# Mustang_Duino.net
KiCad netlist of a schematic drawn in EAGLE
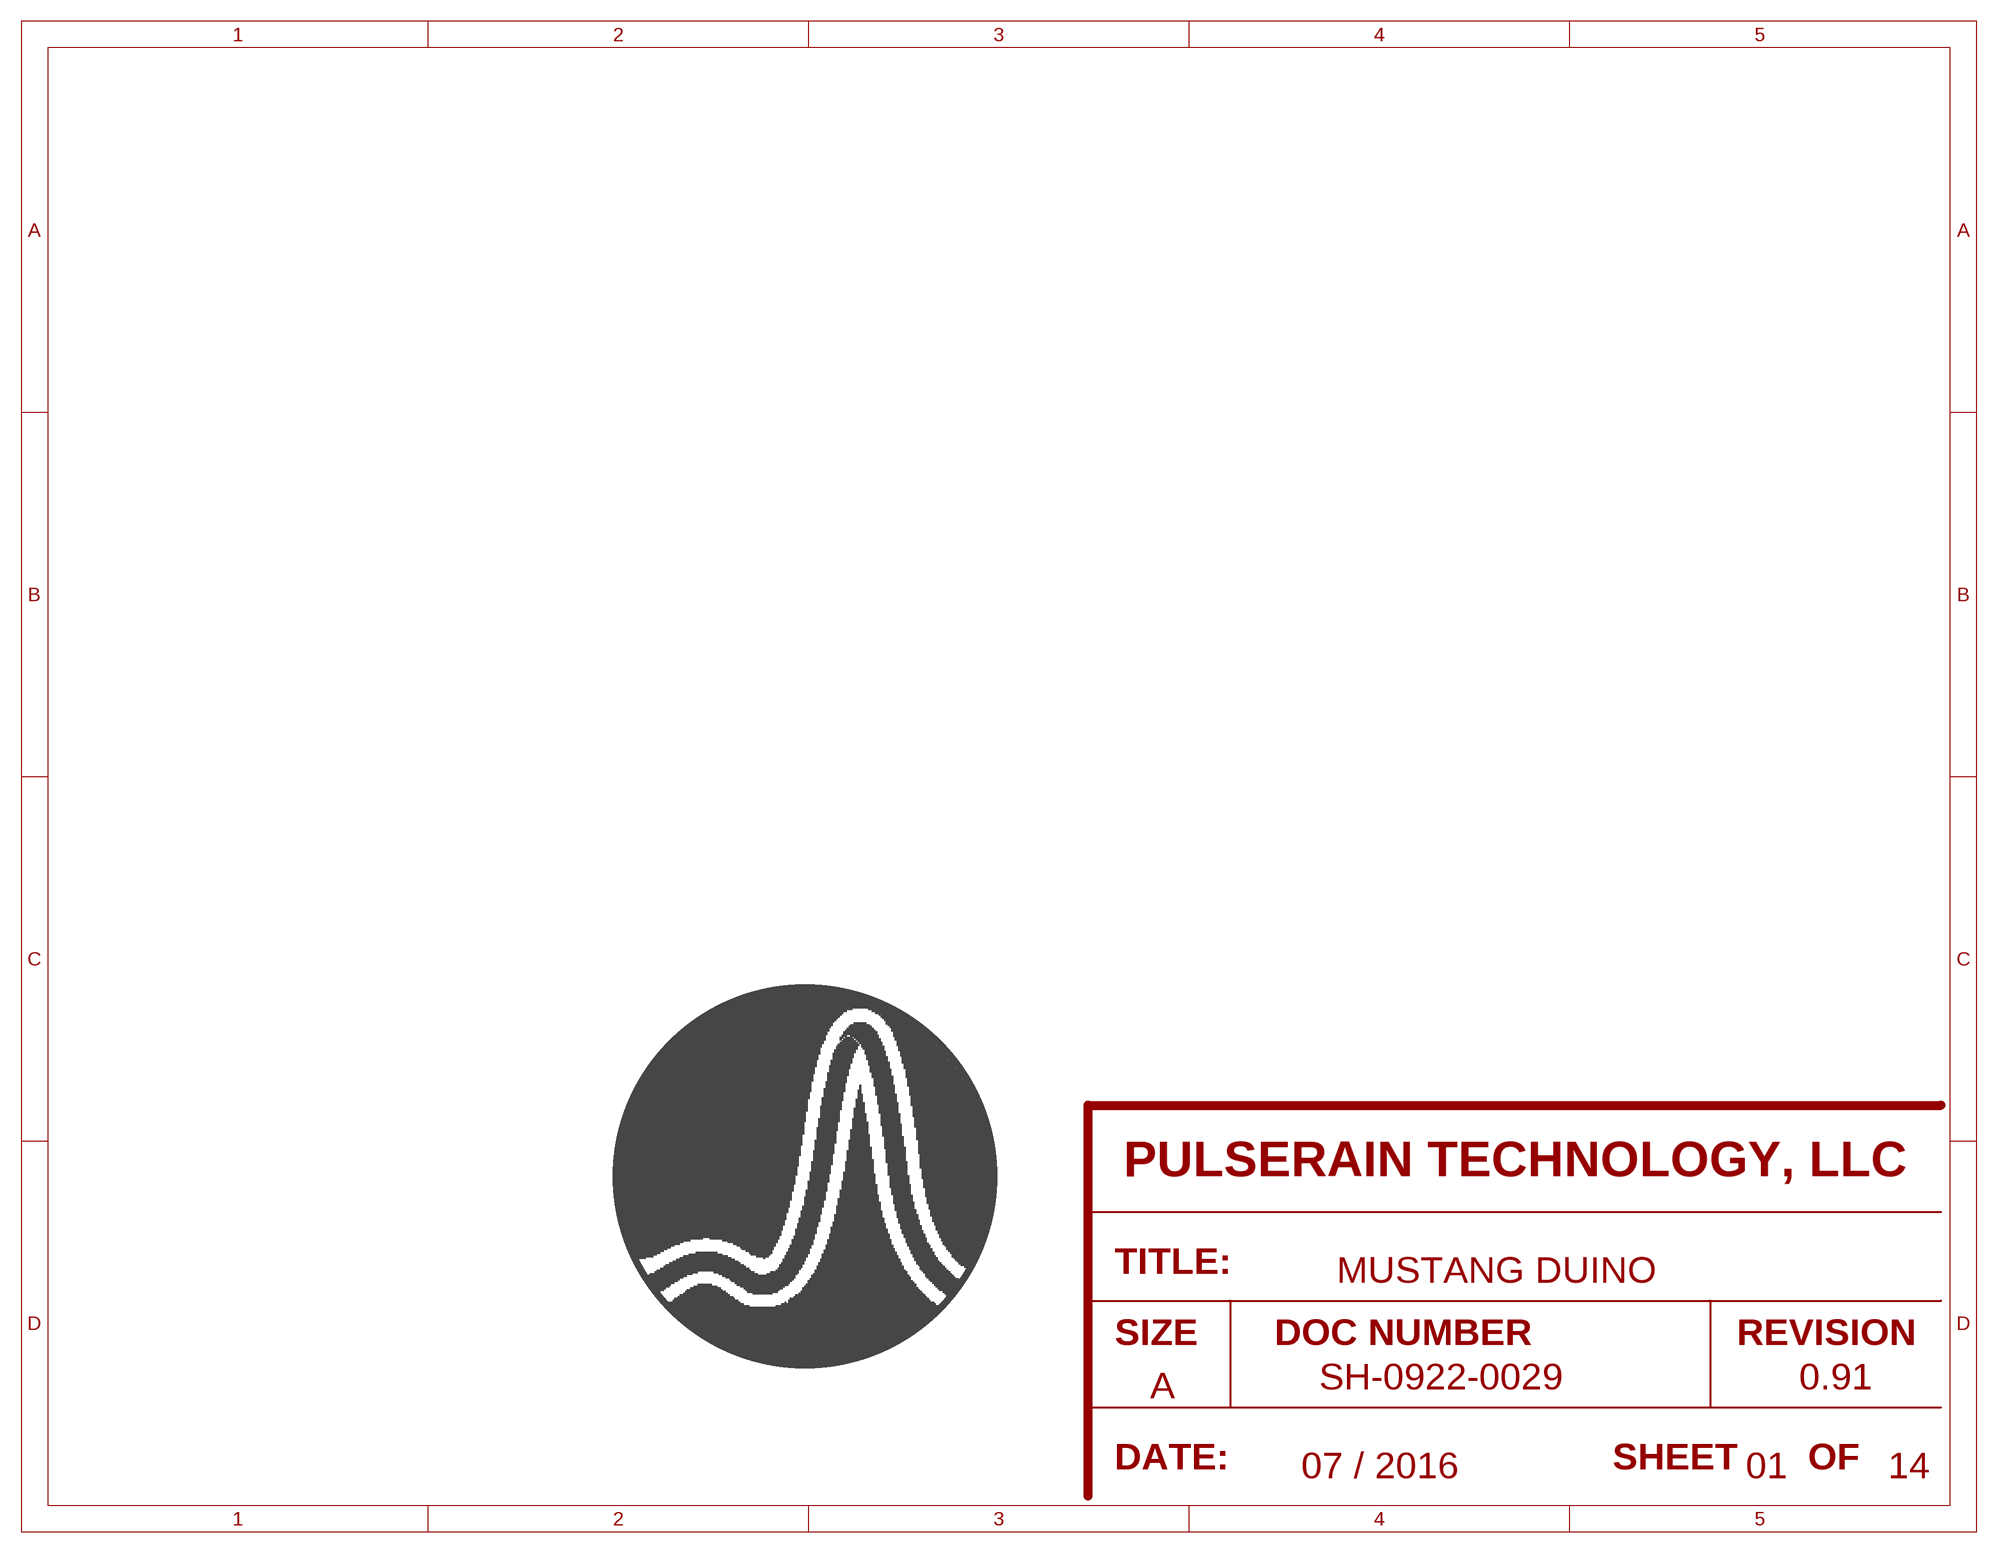
[diagram p0: schematic, sheet 1]
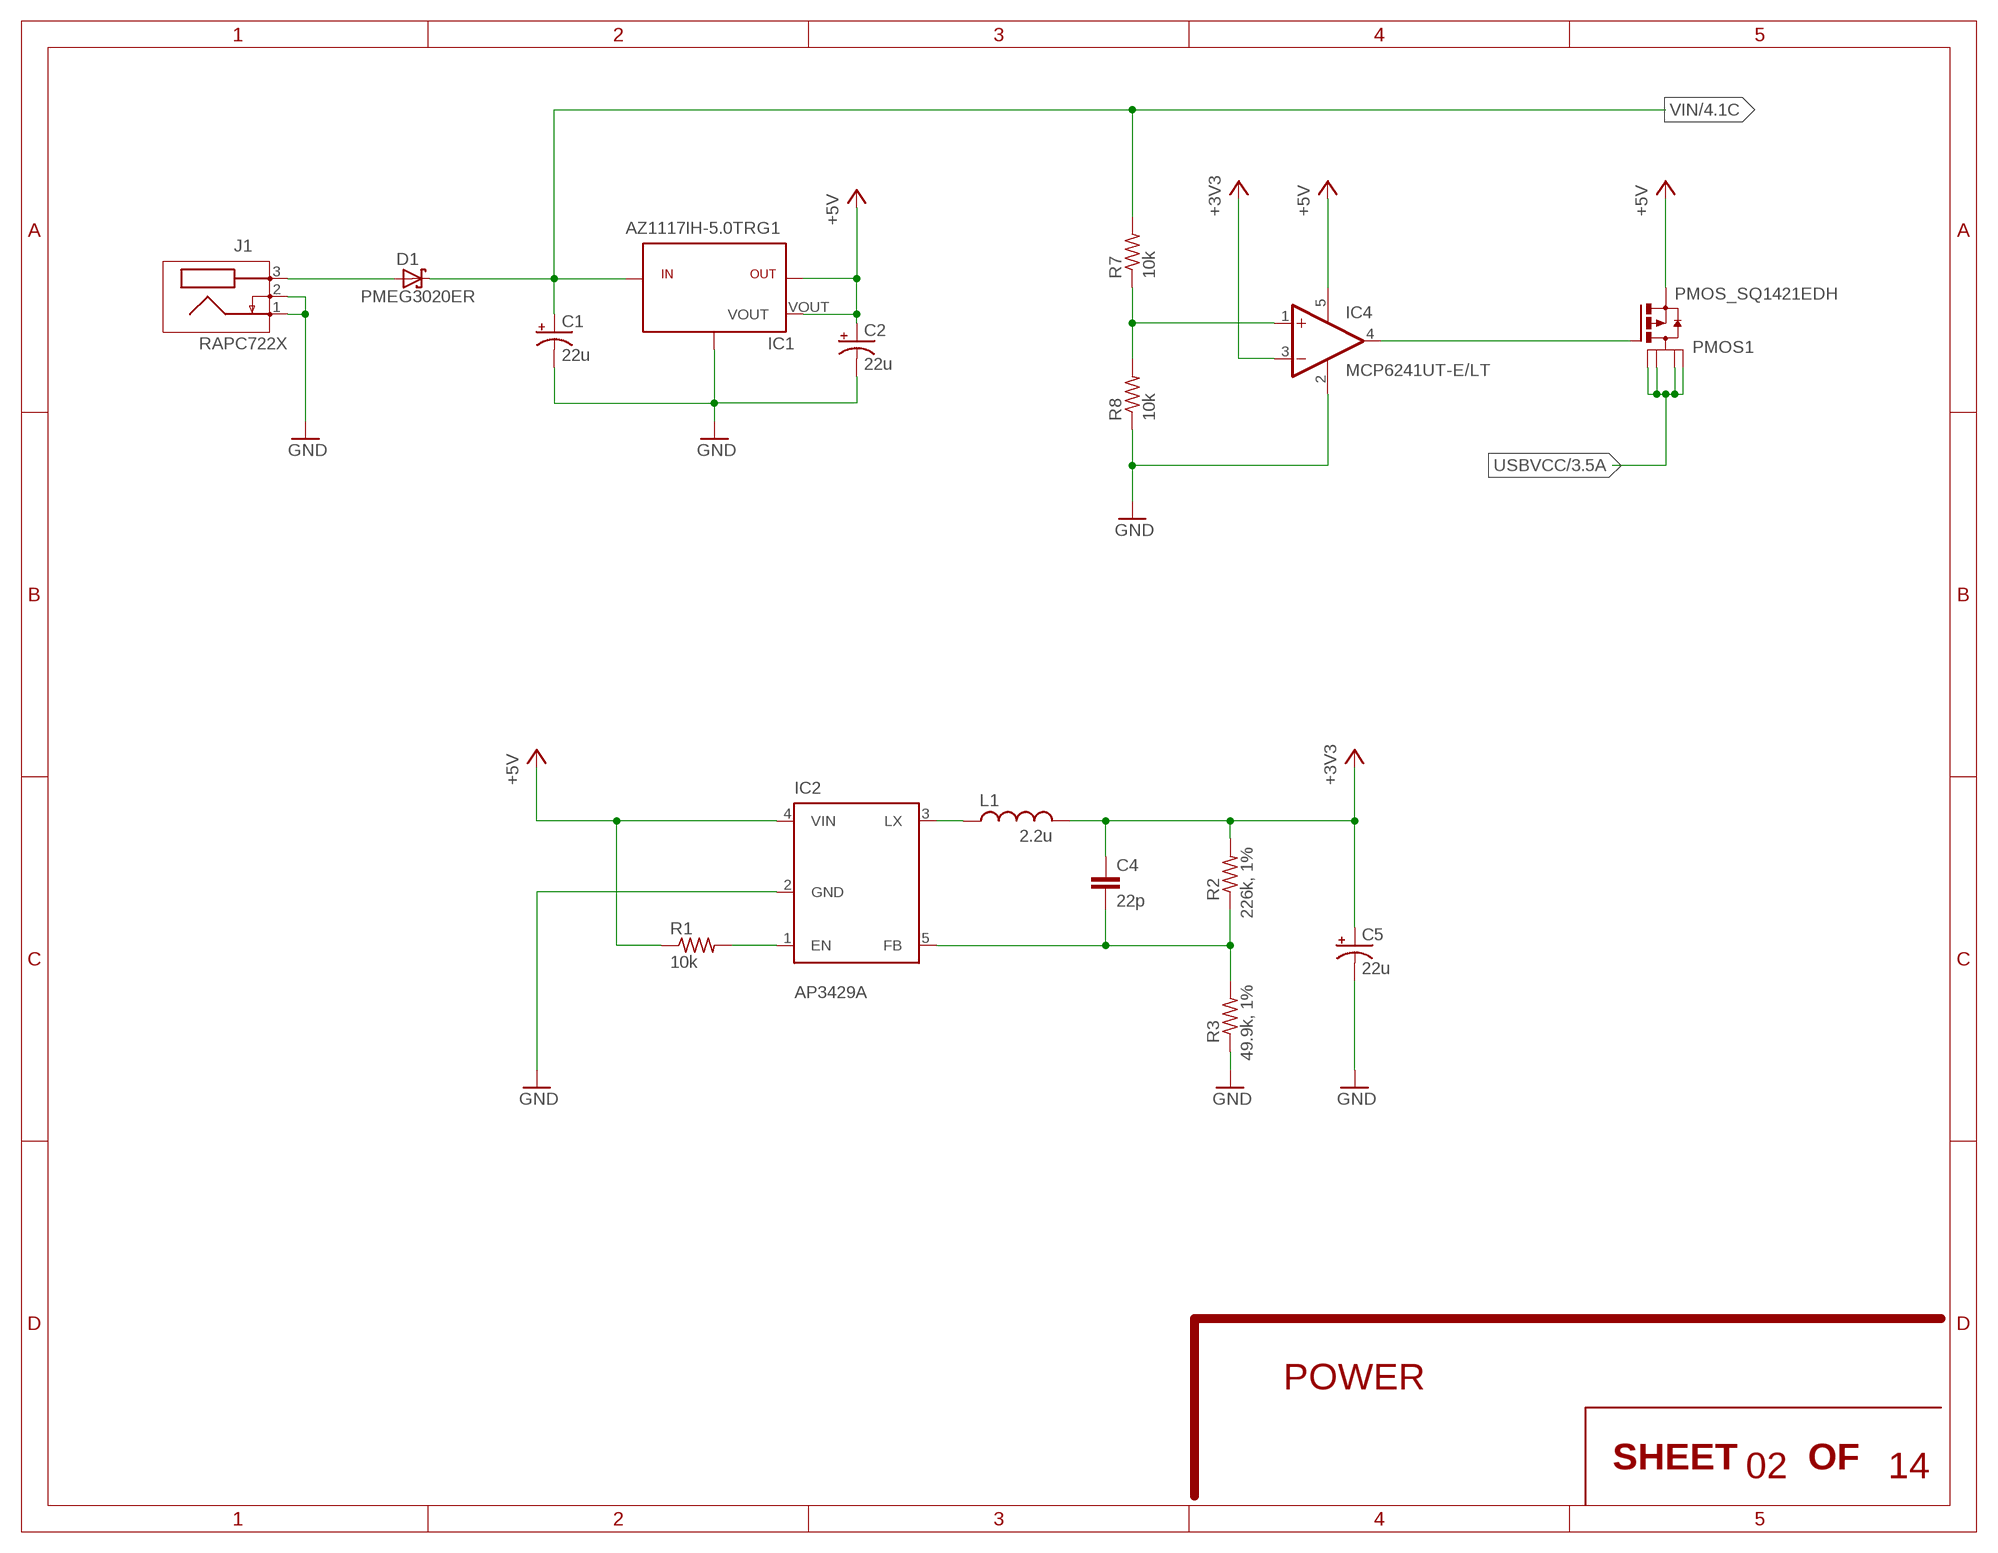
[diagram p1: schematic, sheet 2]
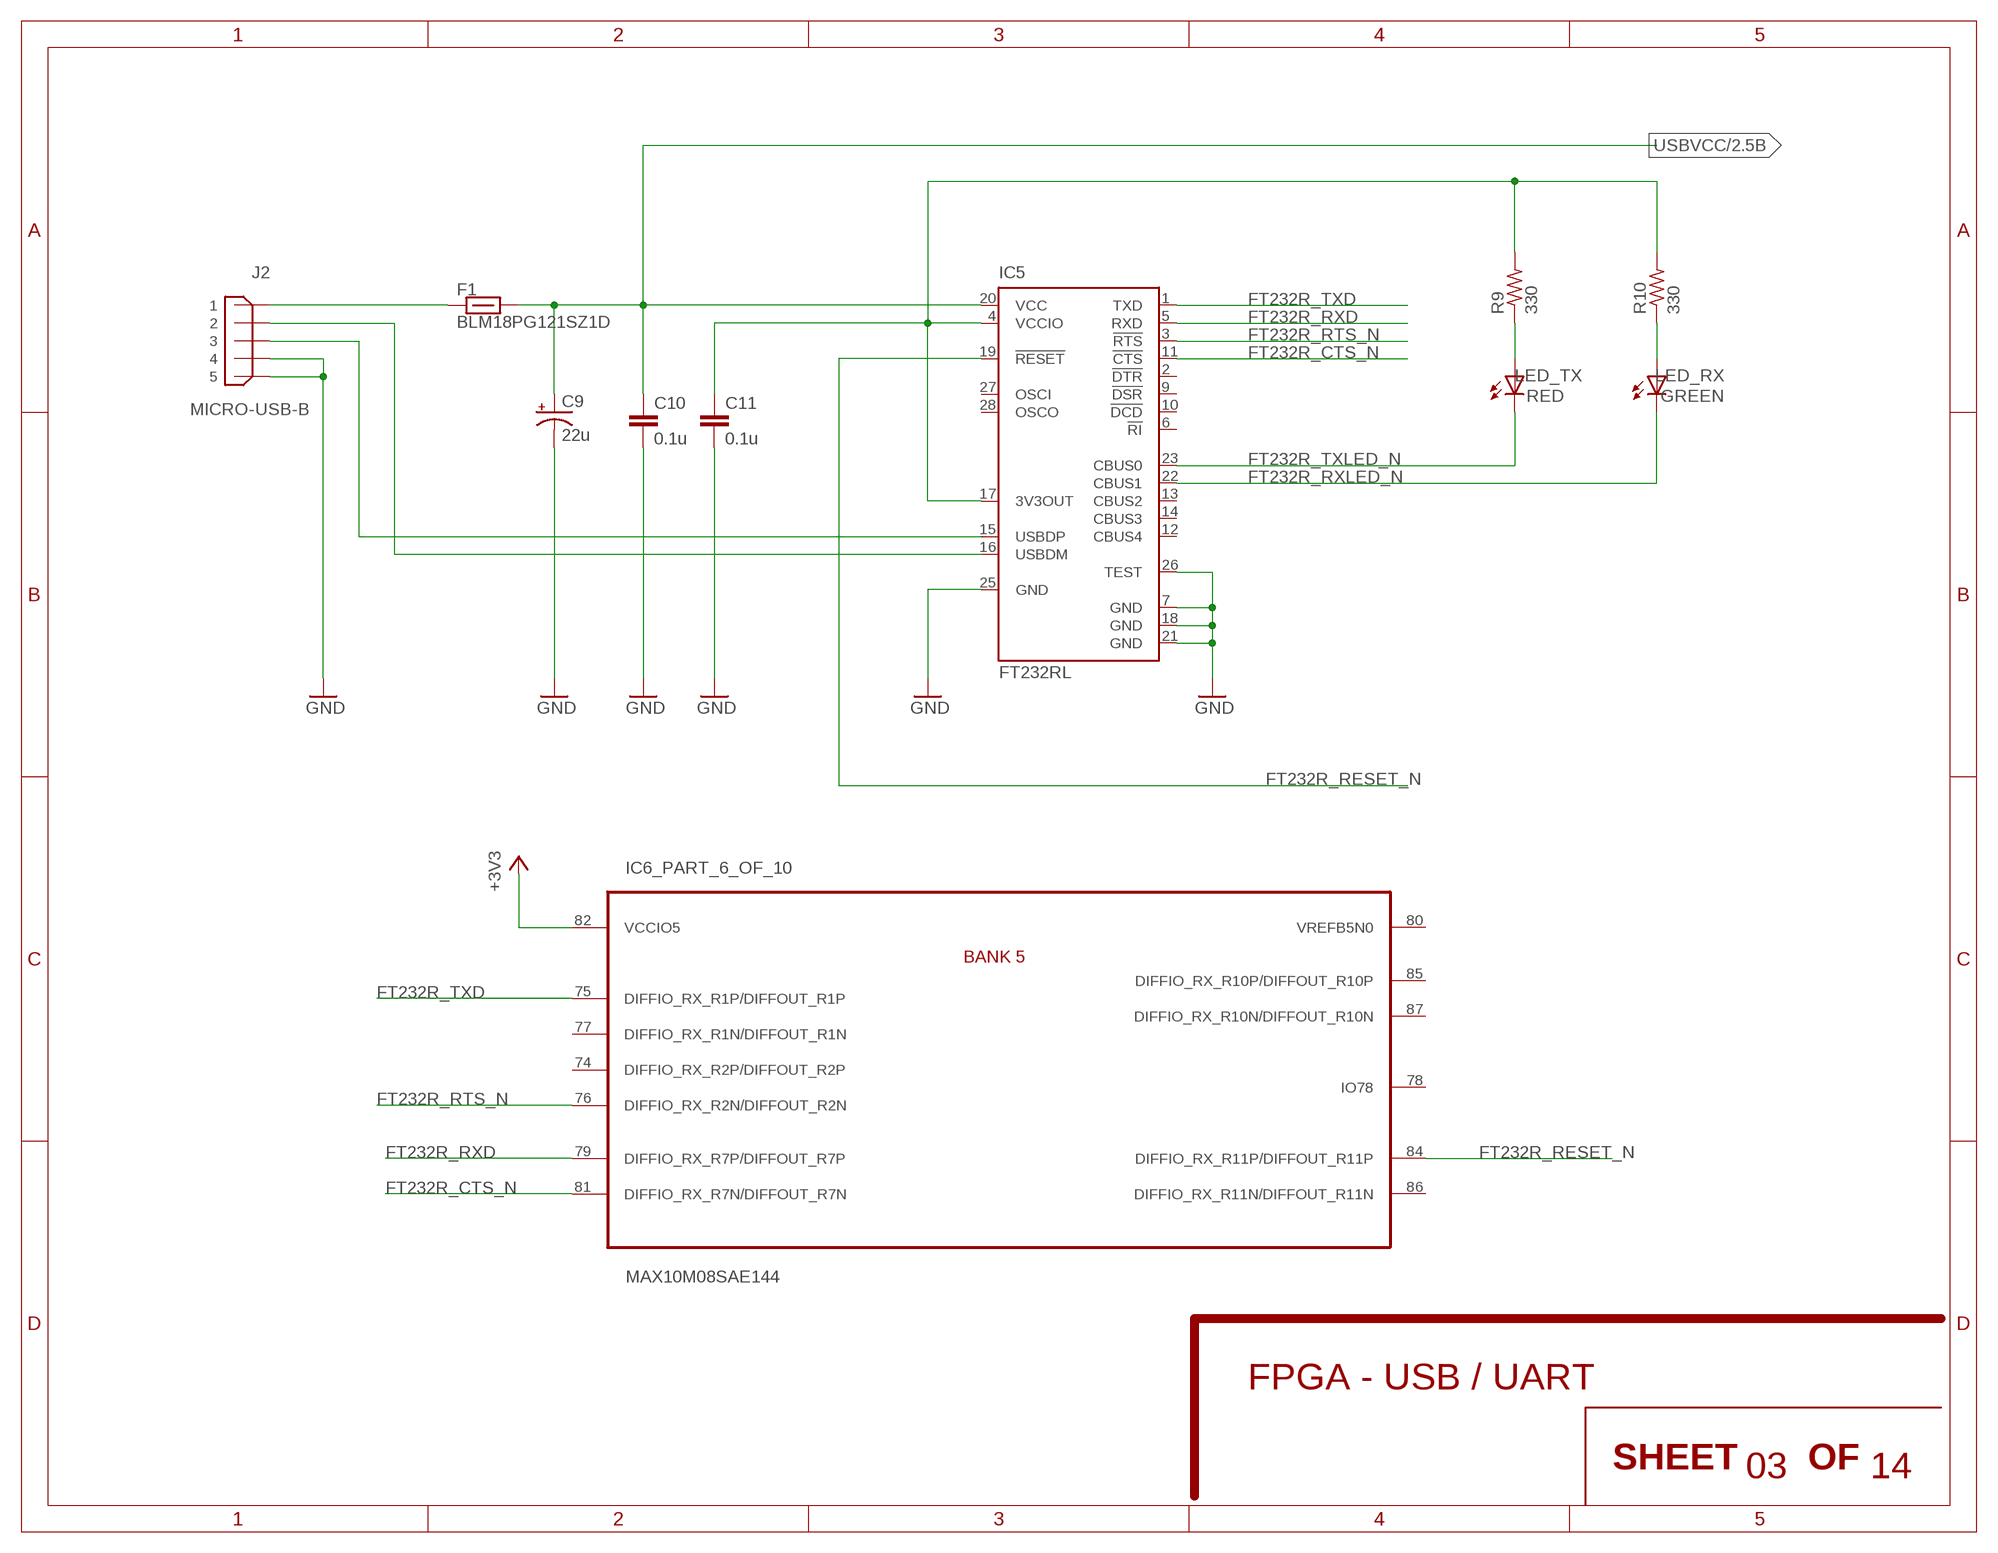
[diagram p2: schematic, sheet 3]
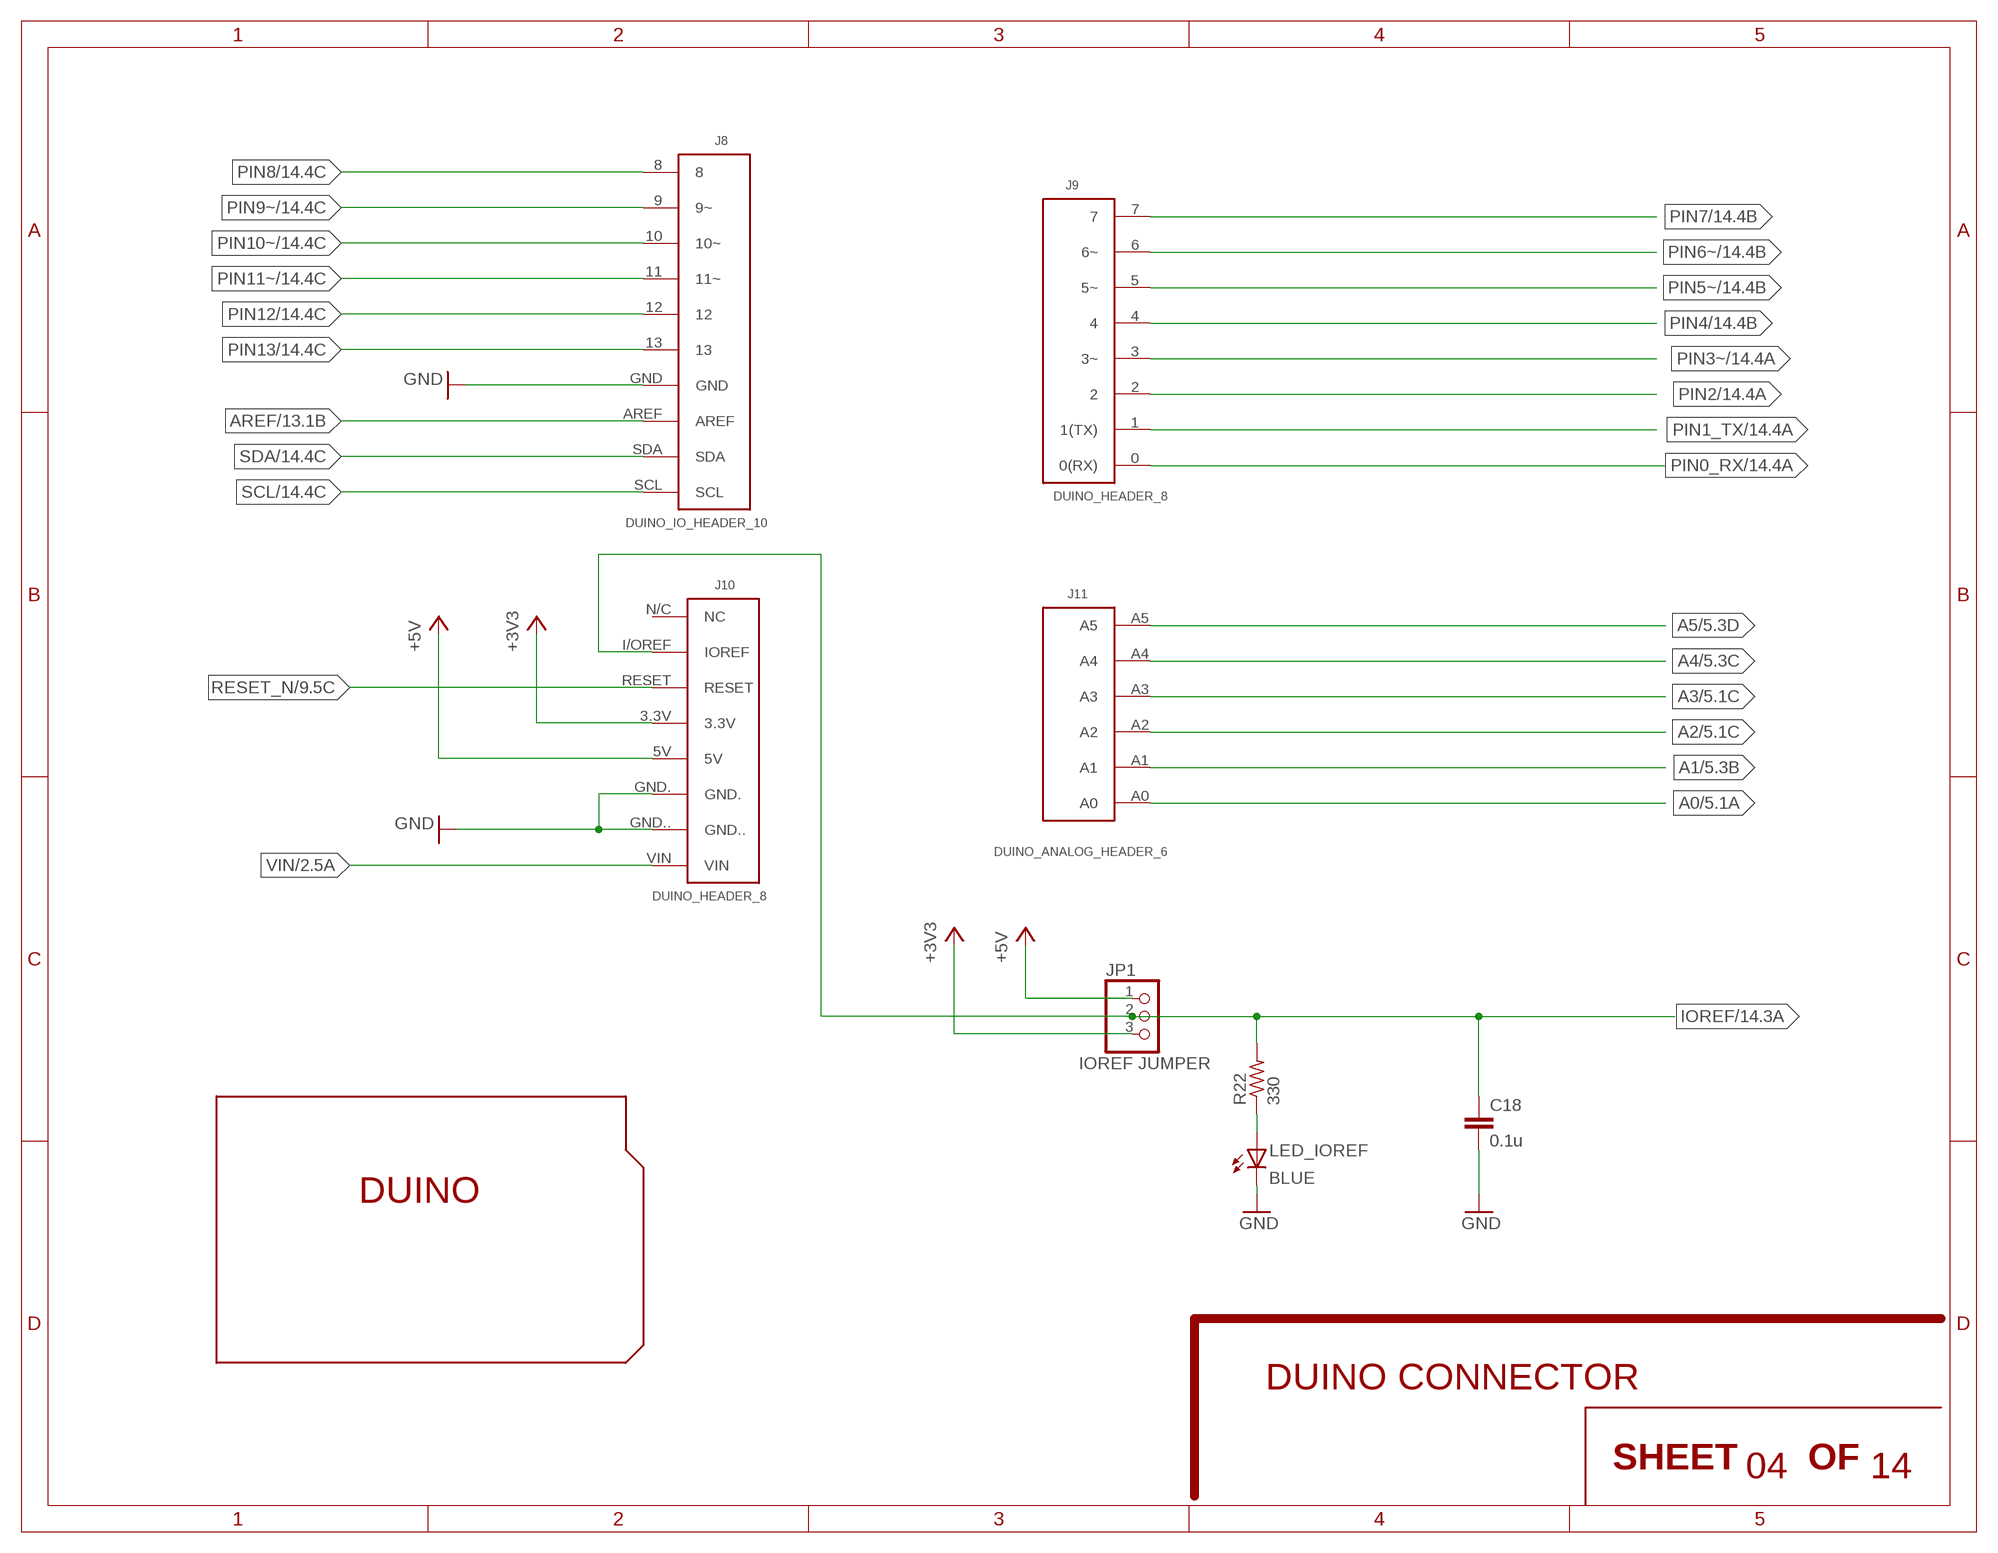
[diagram p3: schematic, sheet 4]
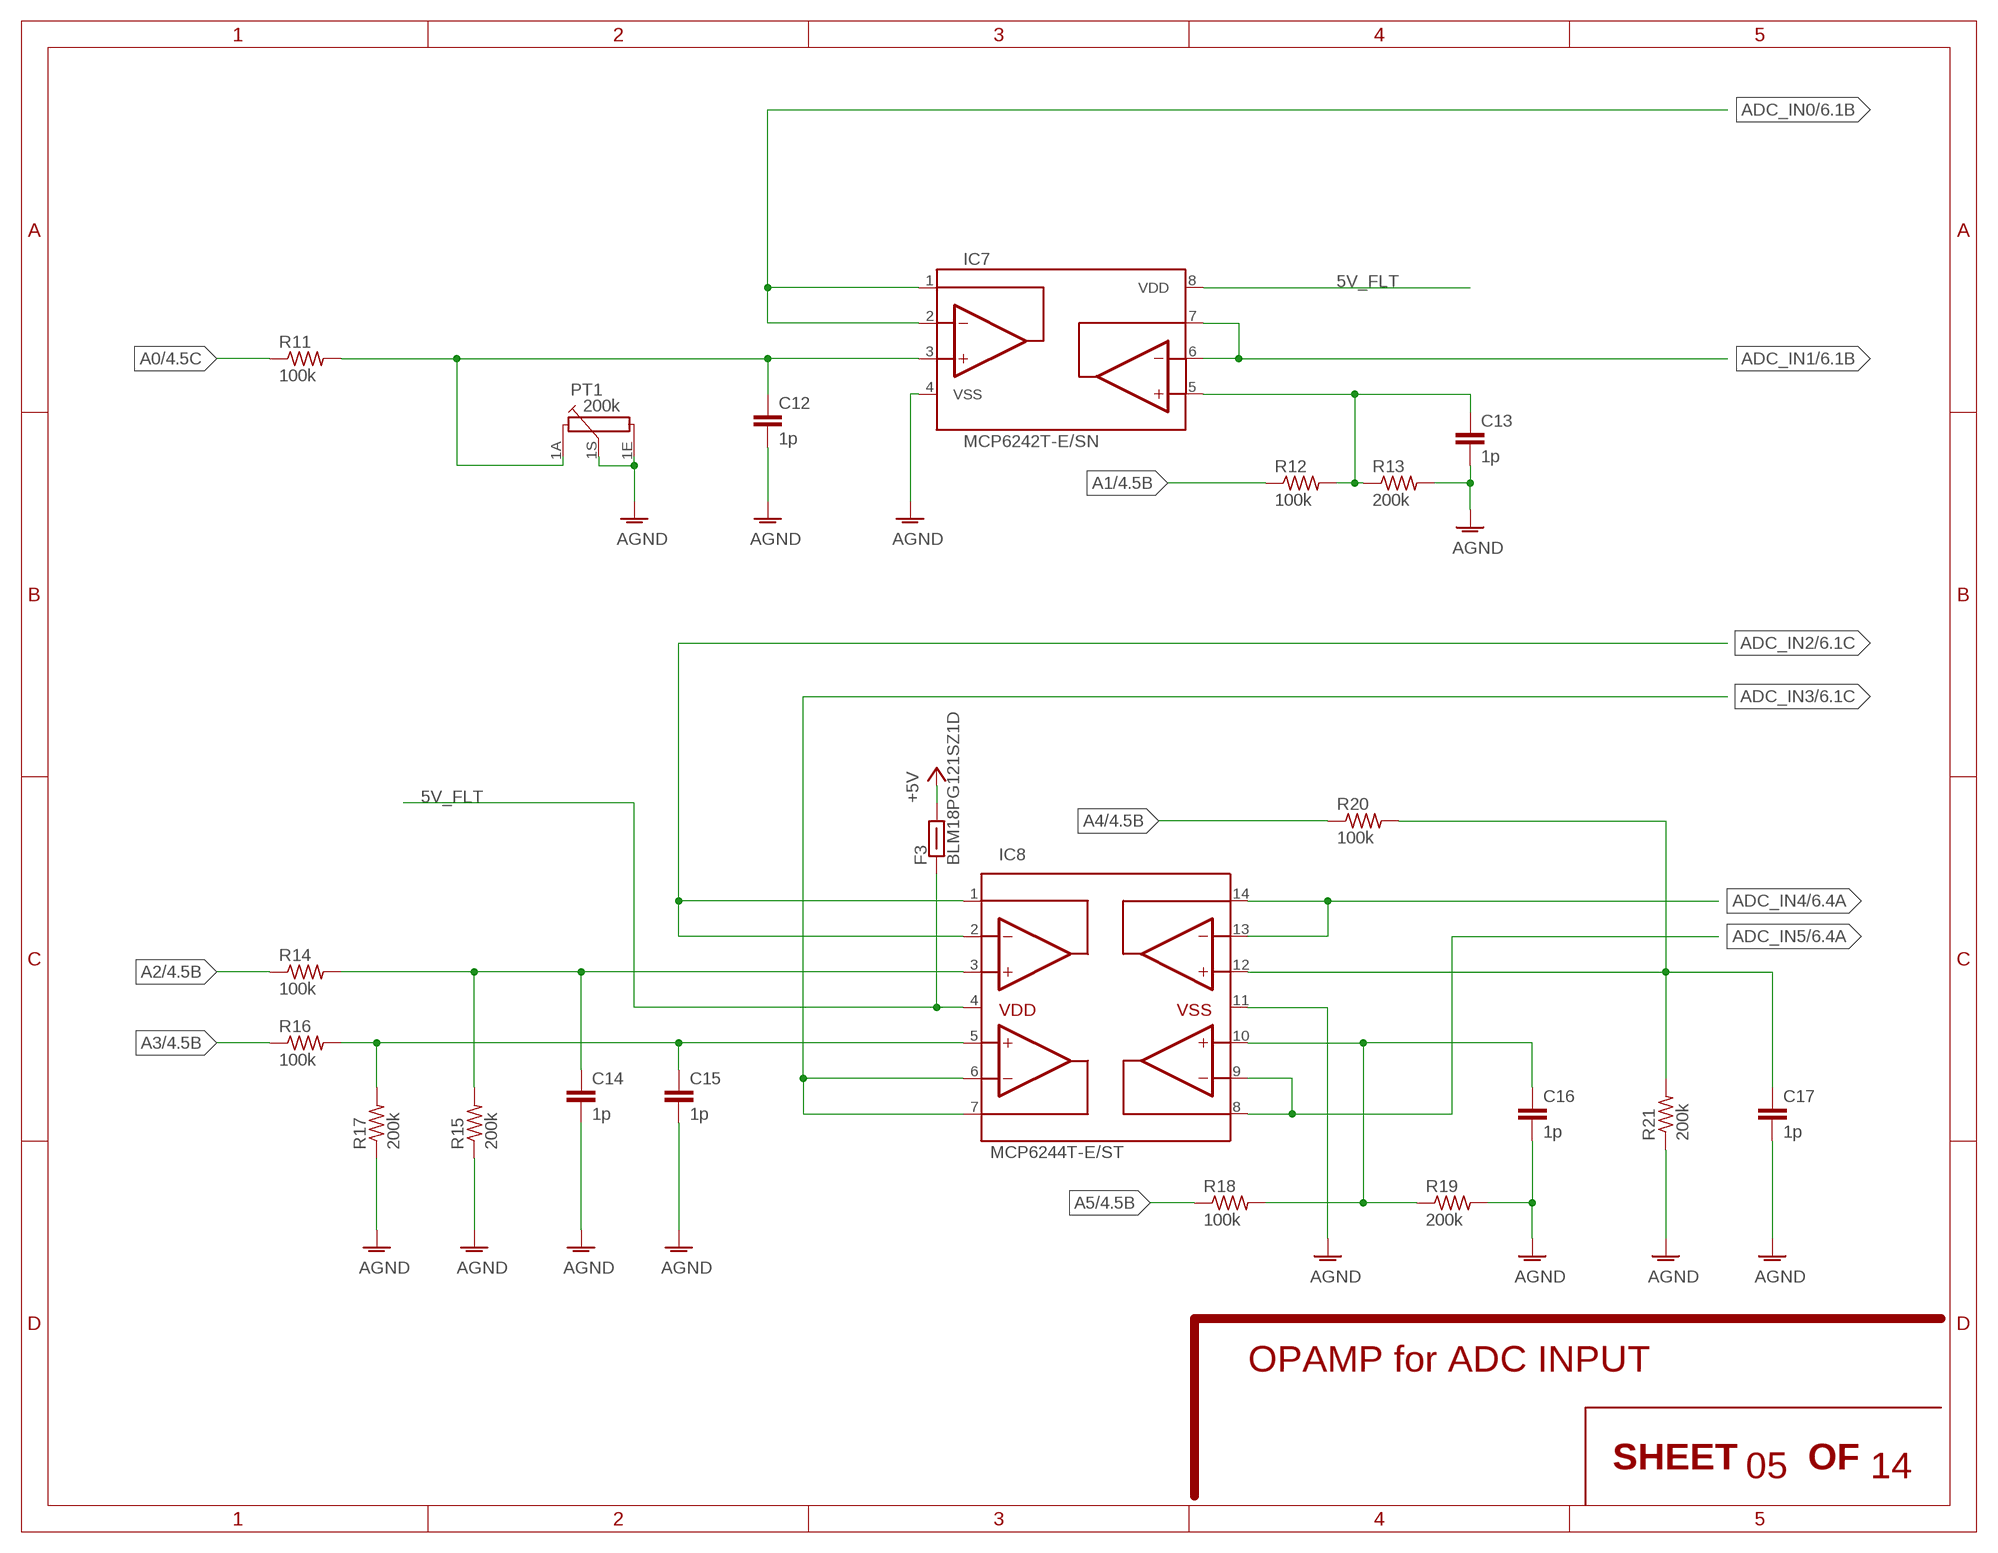
[diagram p4: schematic, sheet 5]
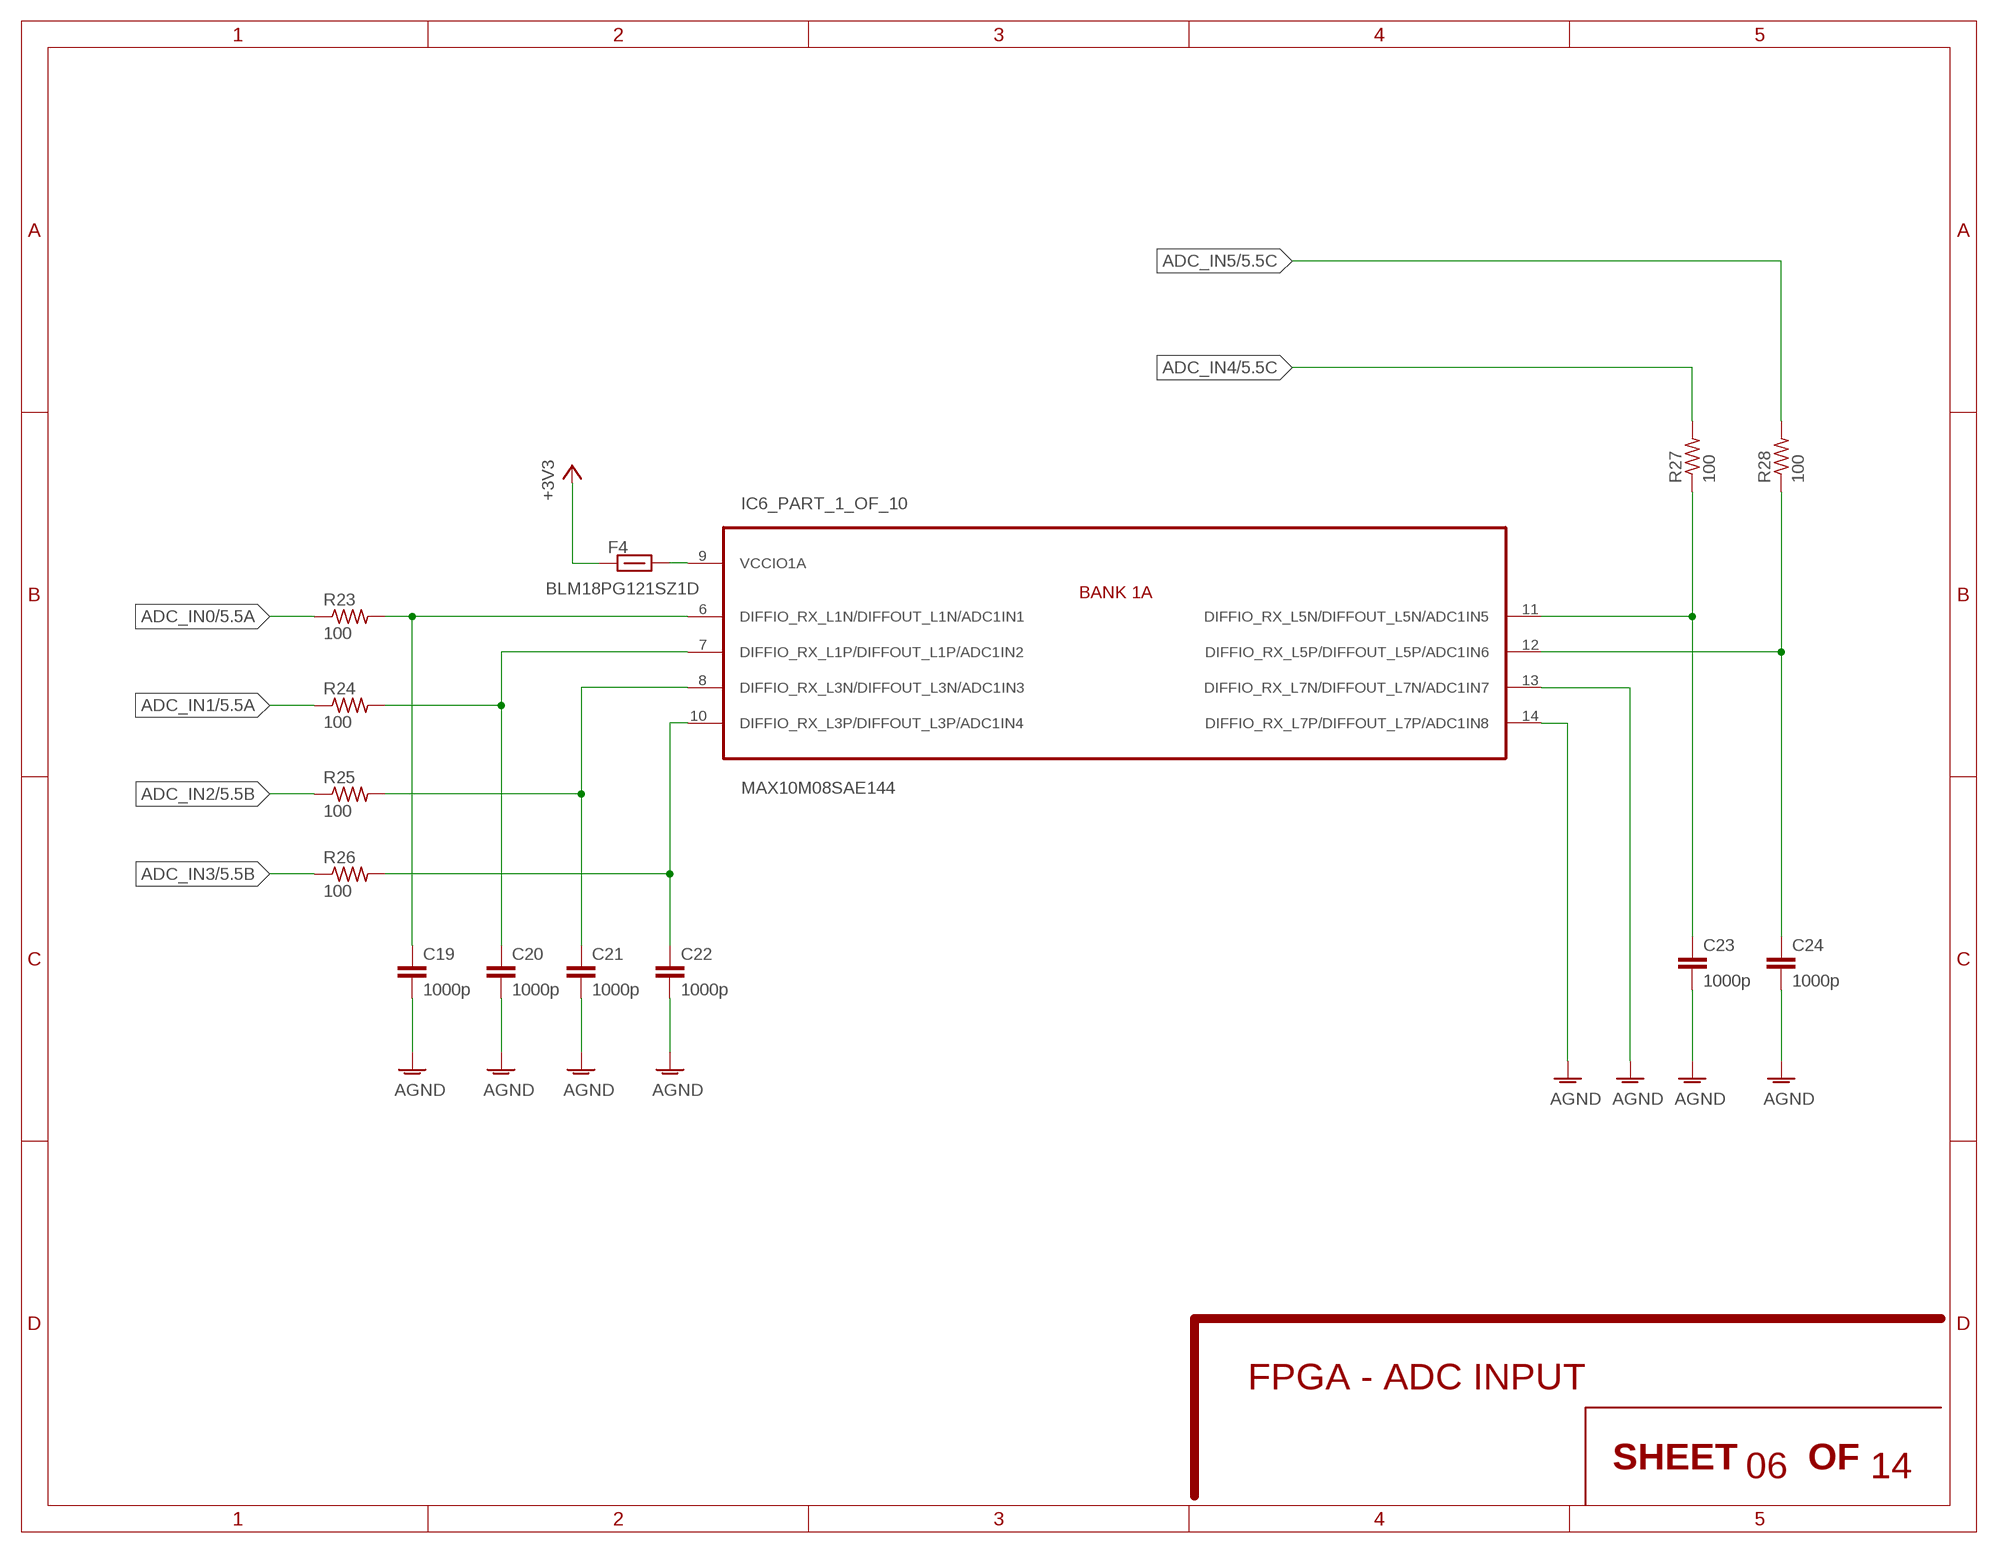
[diagram p5: schematic, sheet 6]
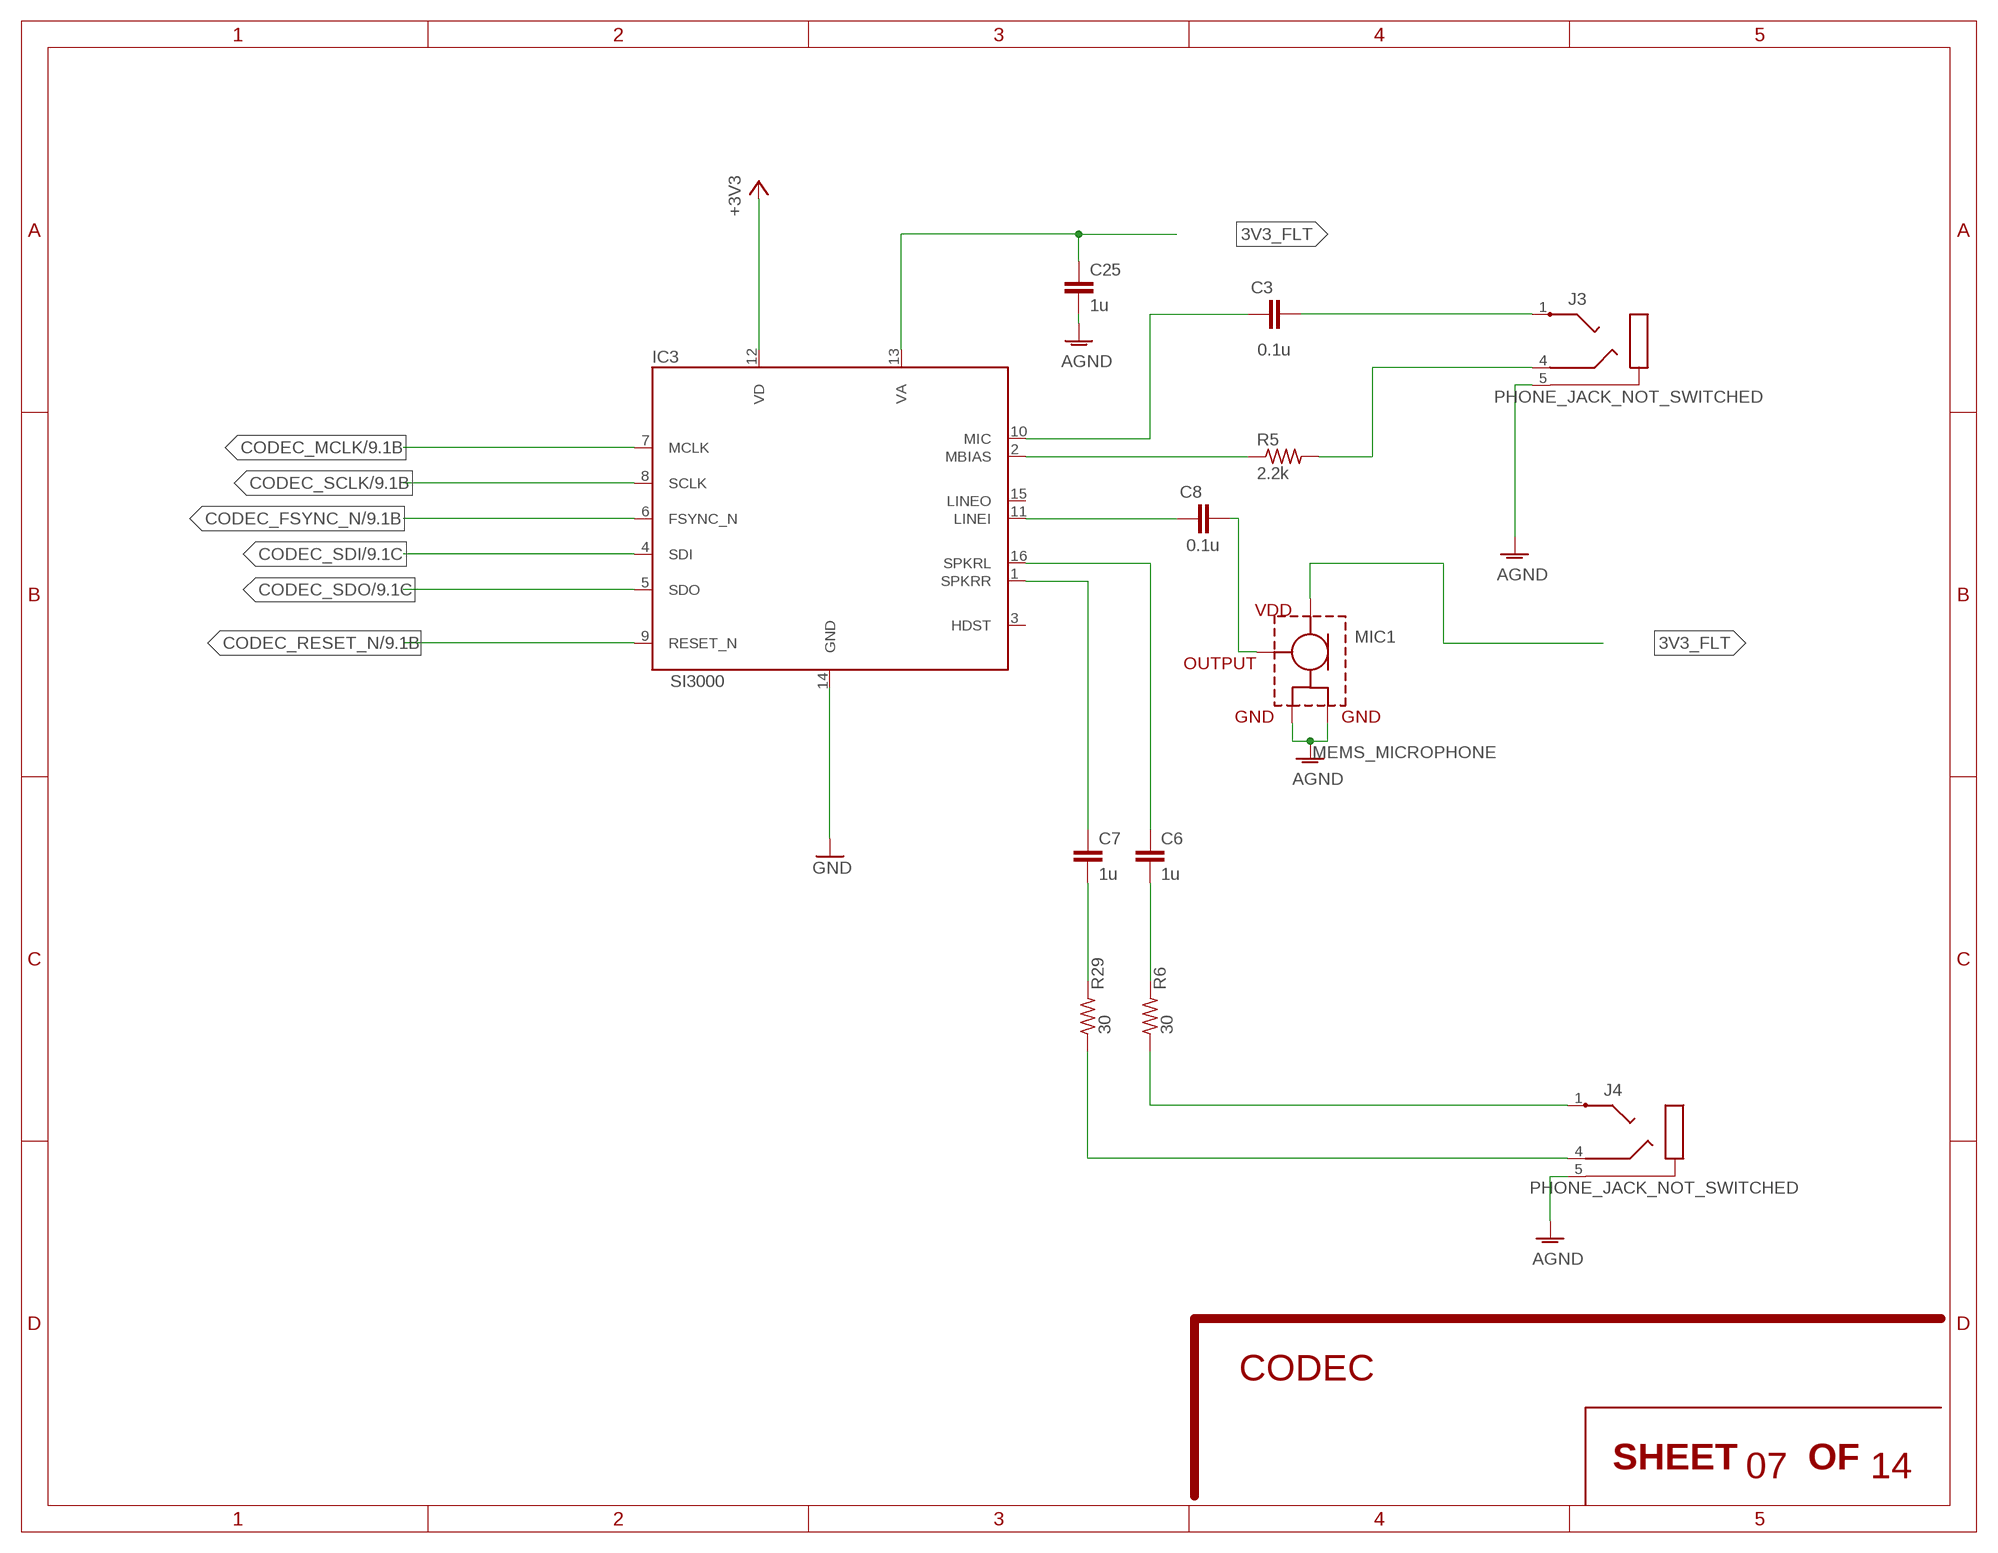
[diagram p6: schematic, sheet 7]
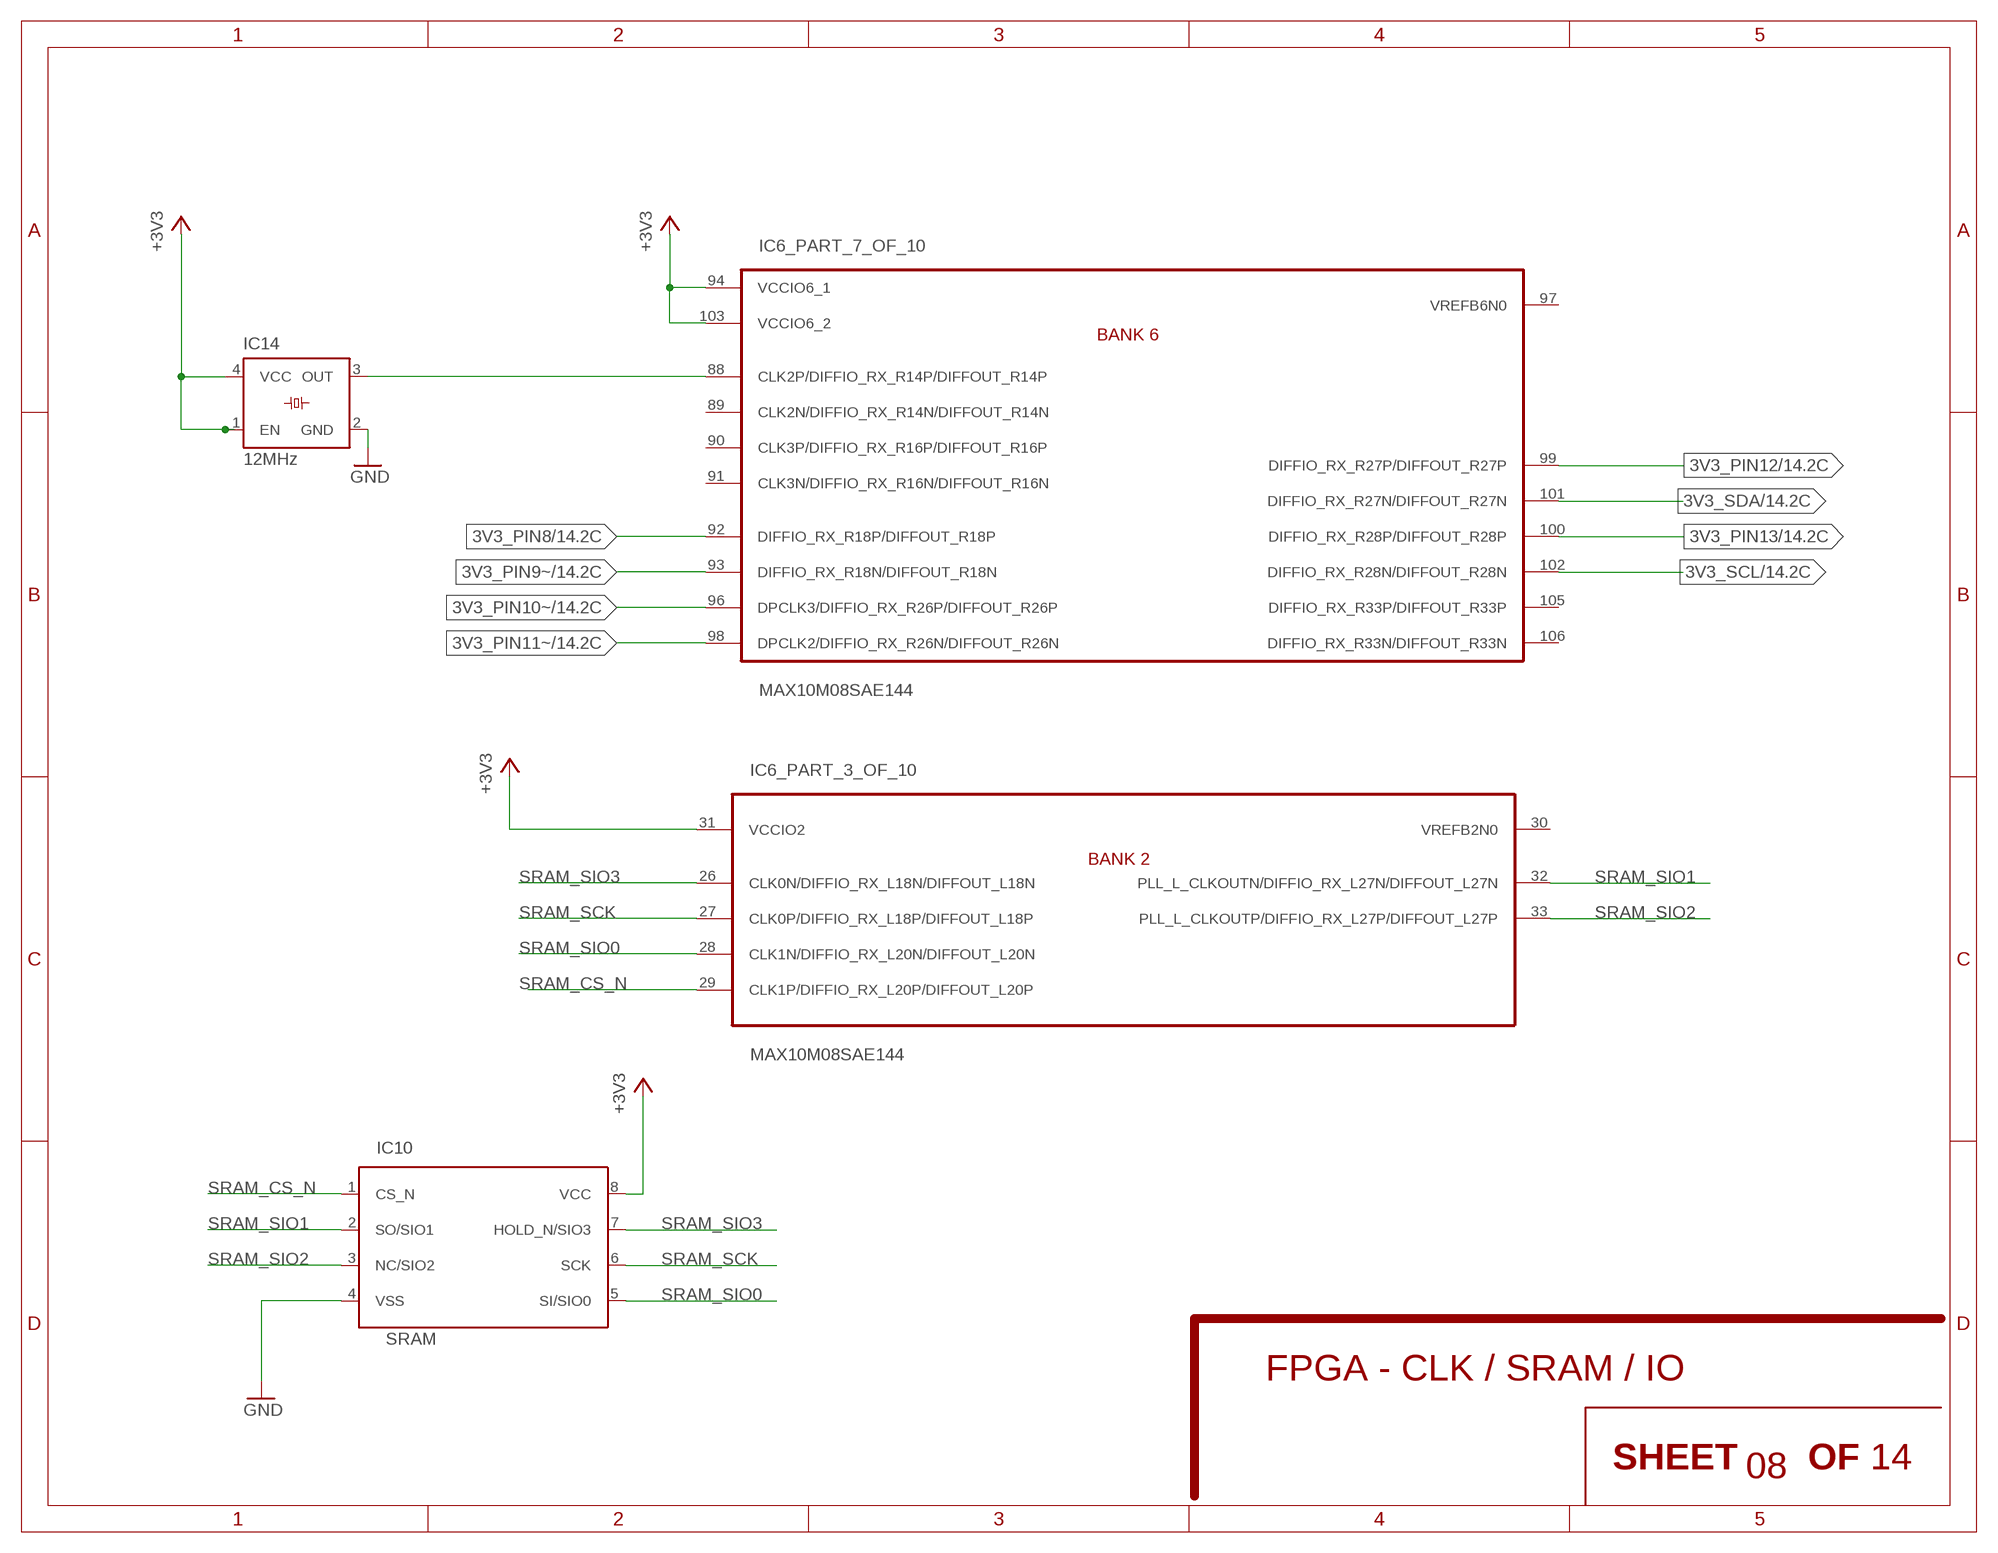
[diagram p7: schematic, sheet 8]
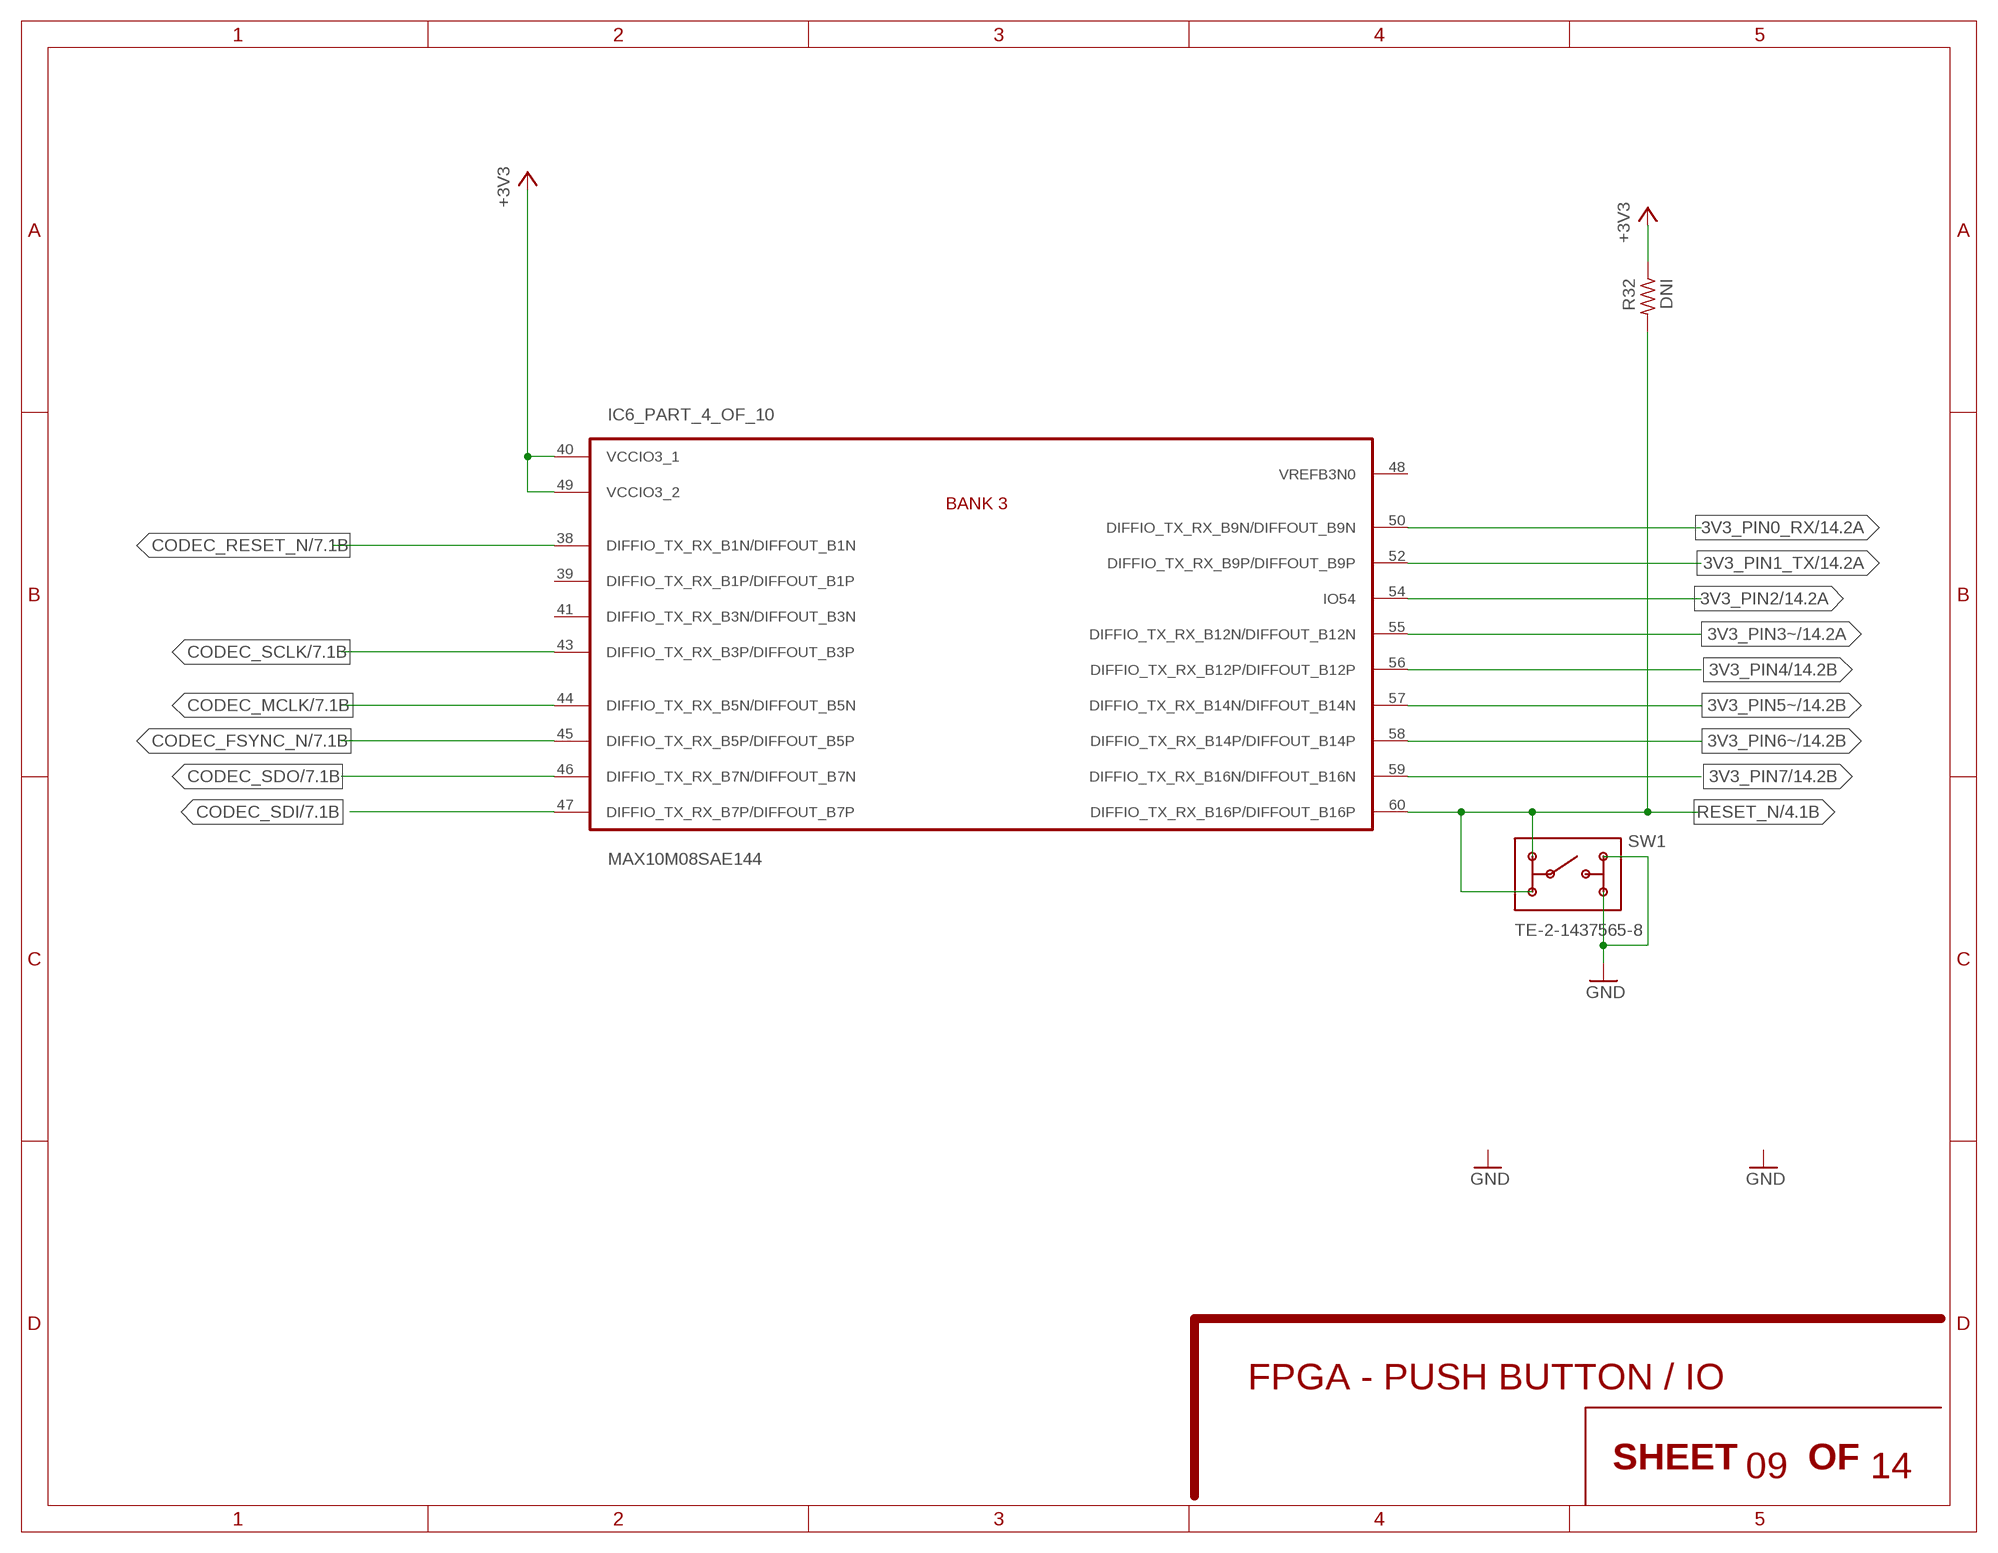
[diagram p8: schematic, sheet 9]
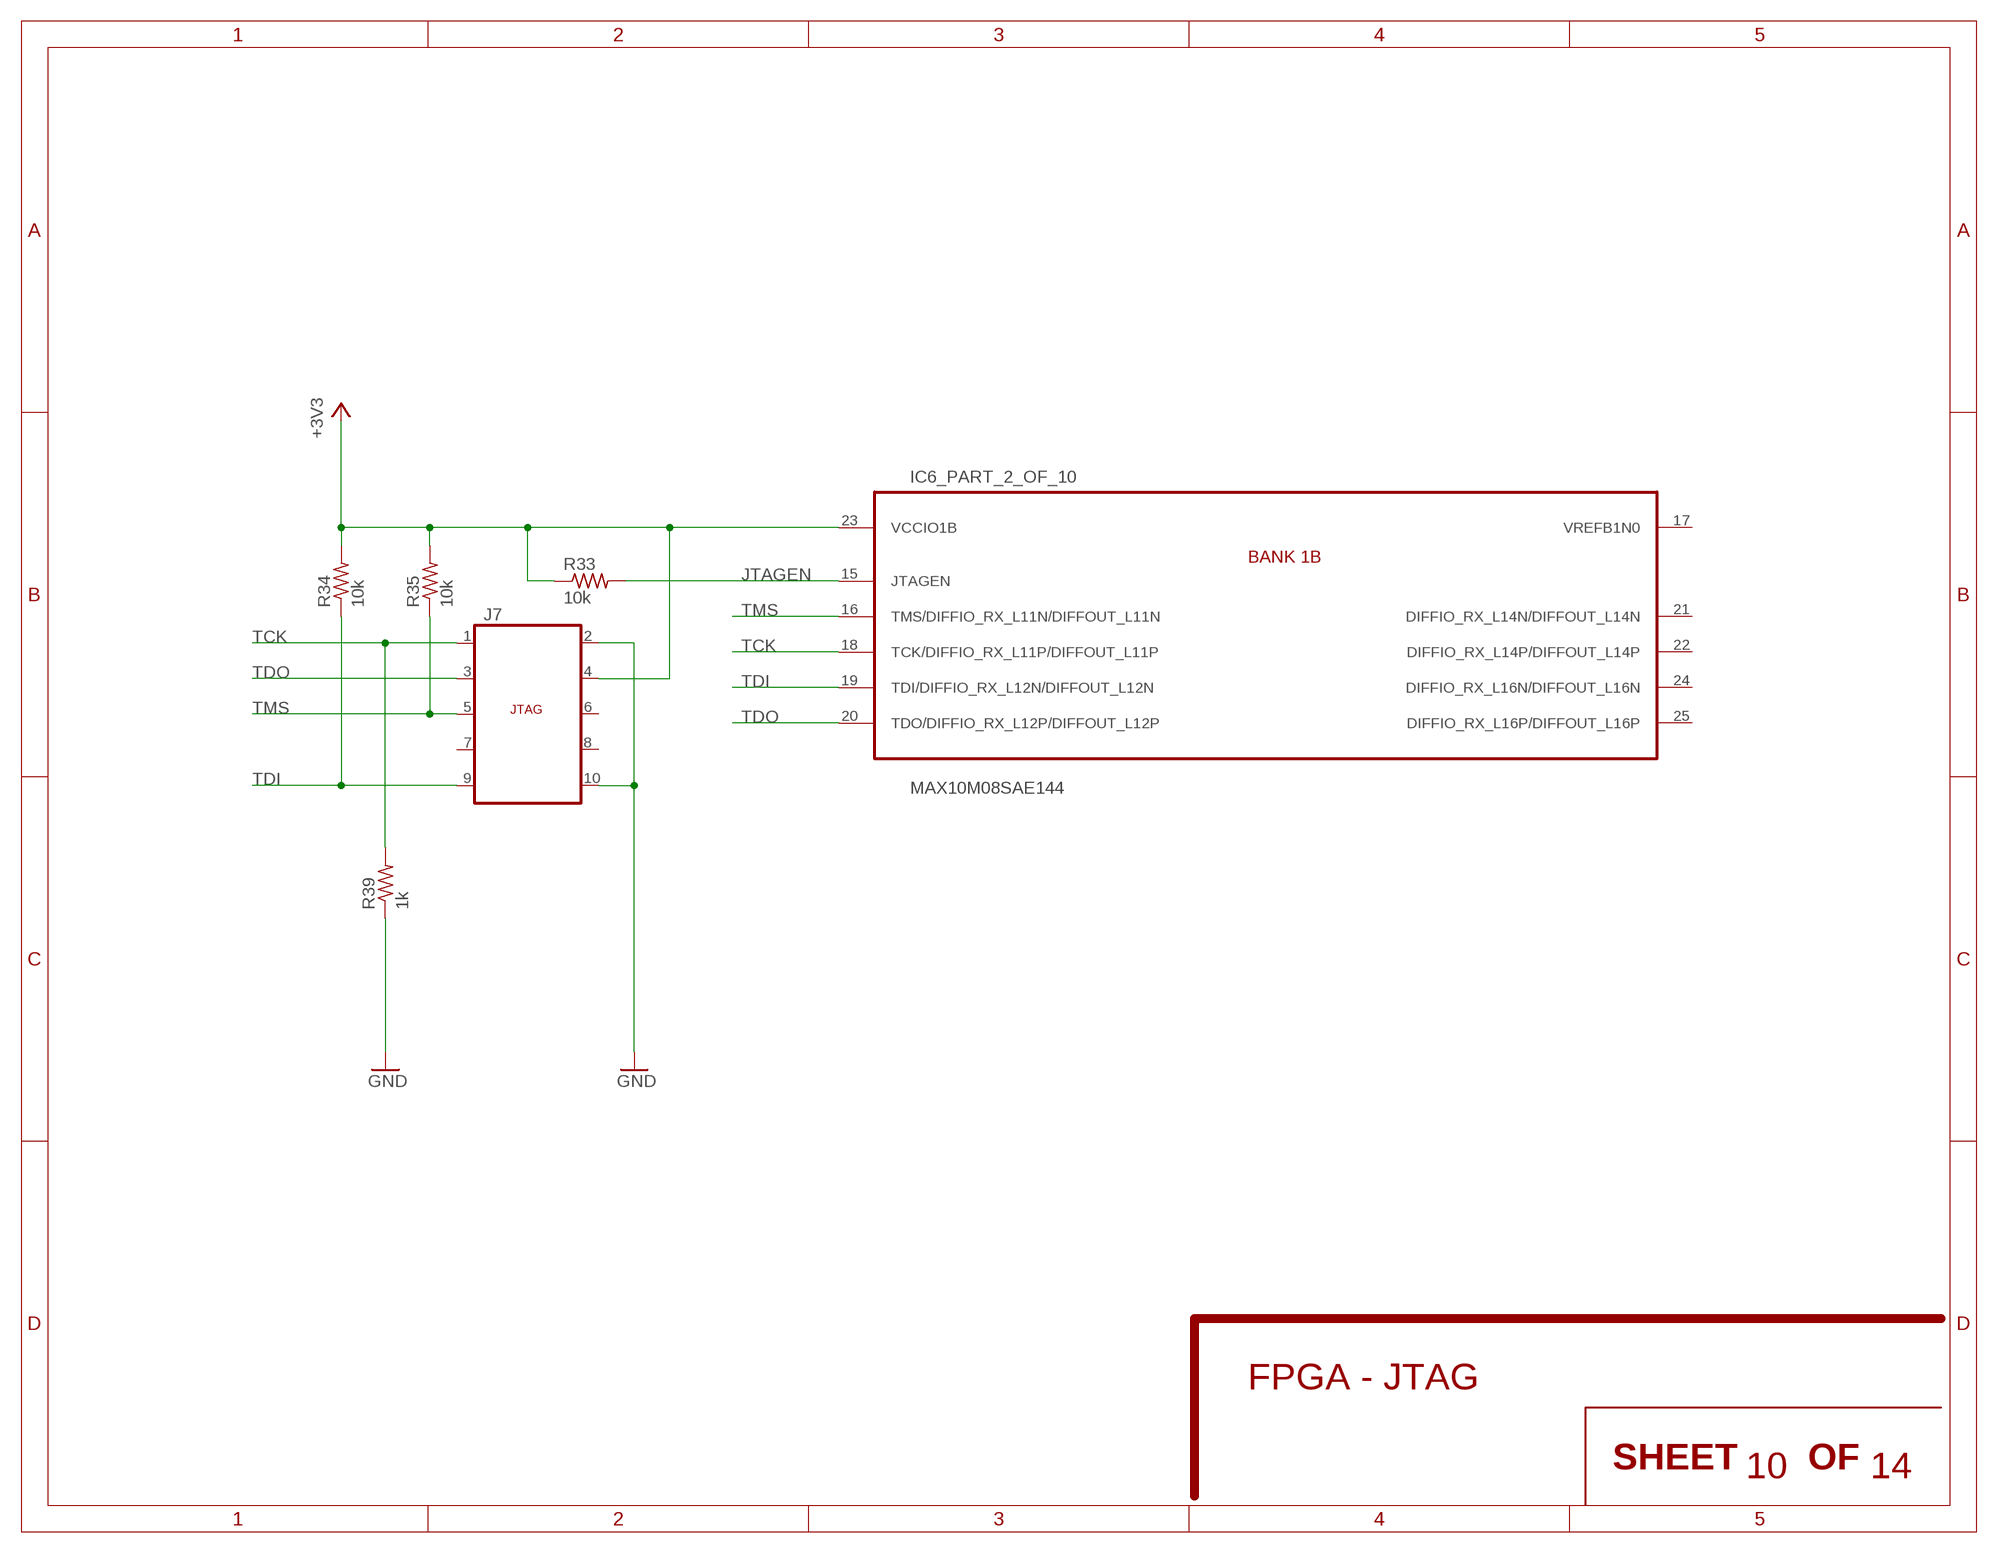
[diagram p9: schematic, sheet 10]
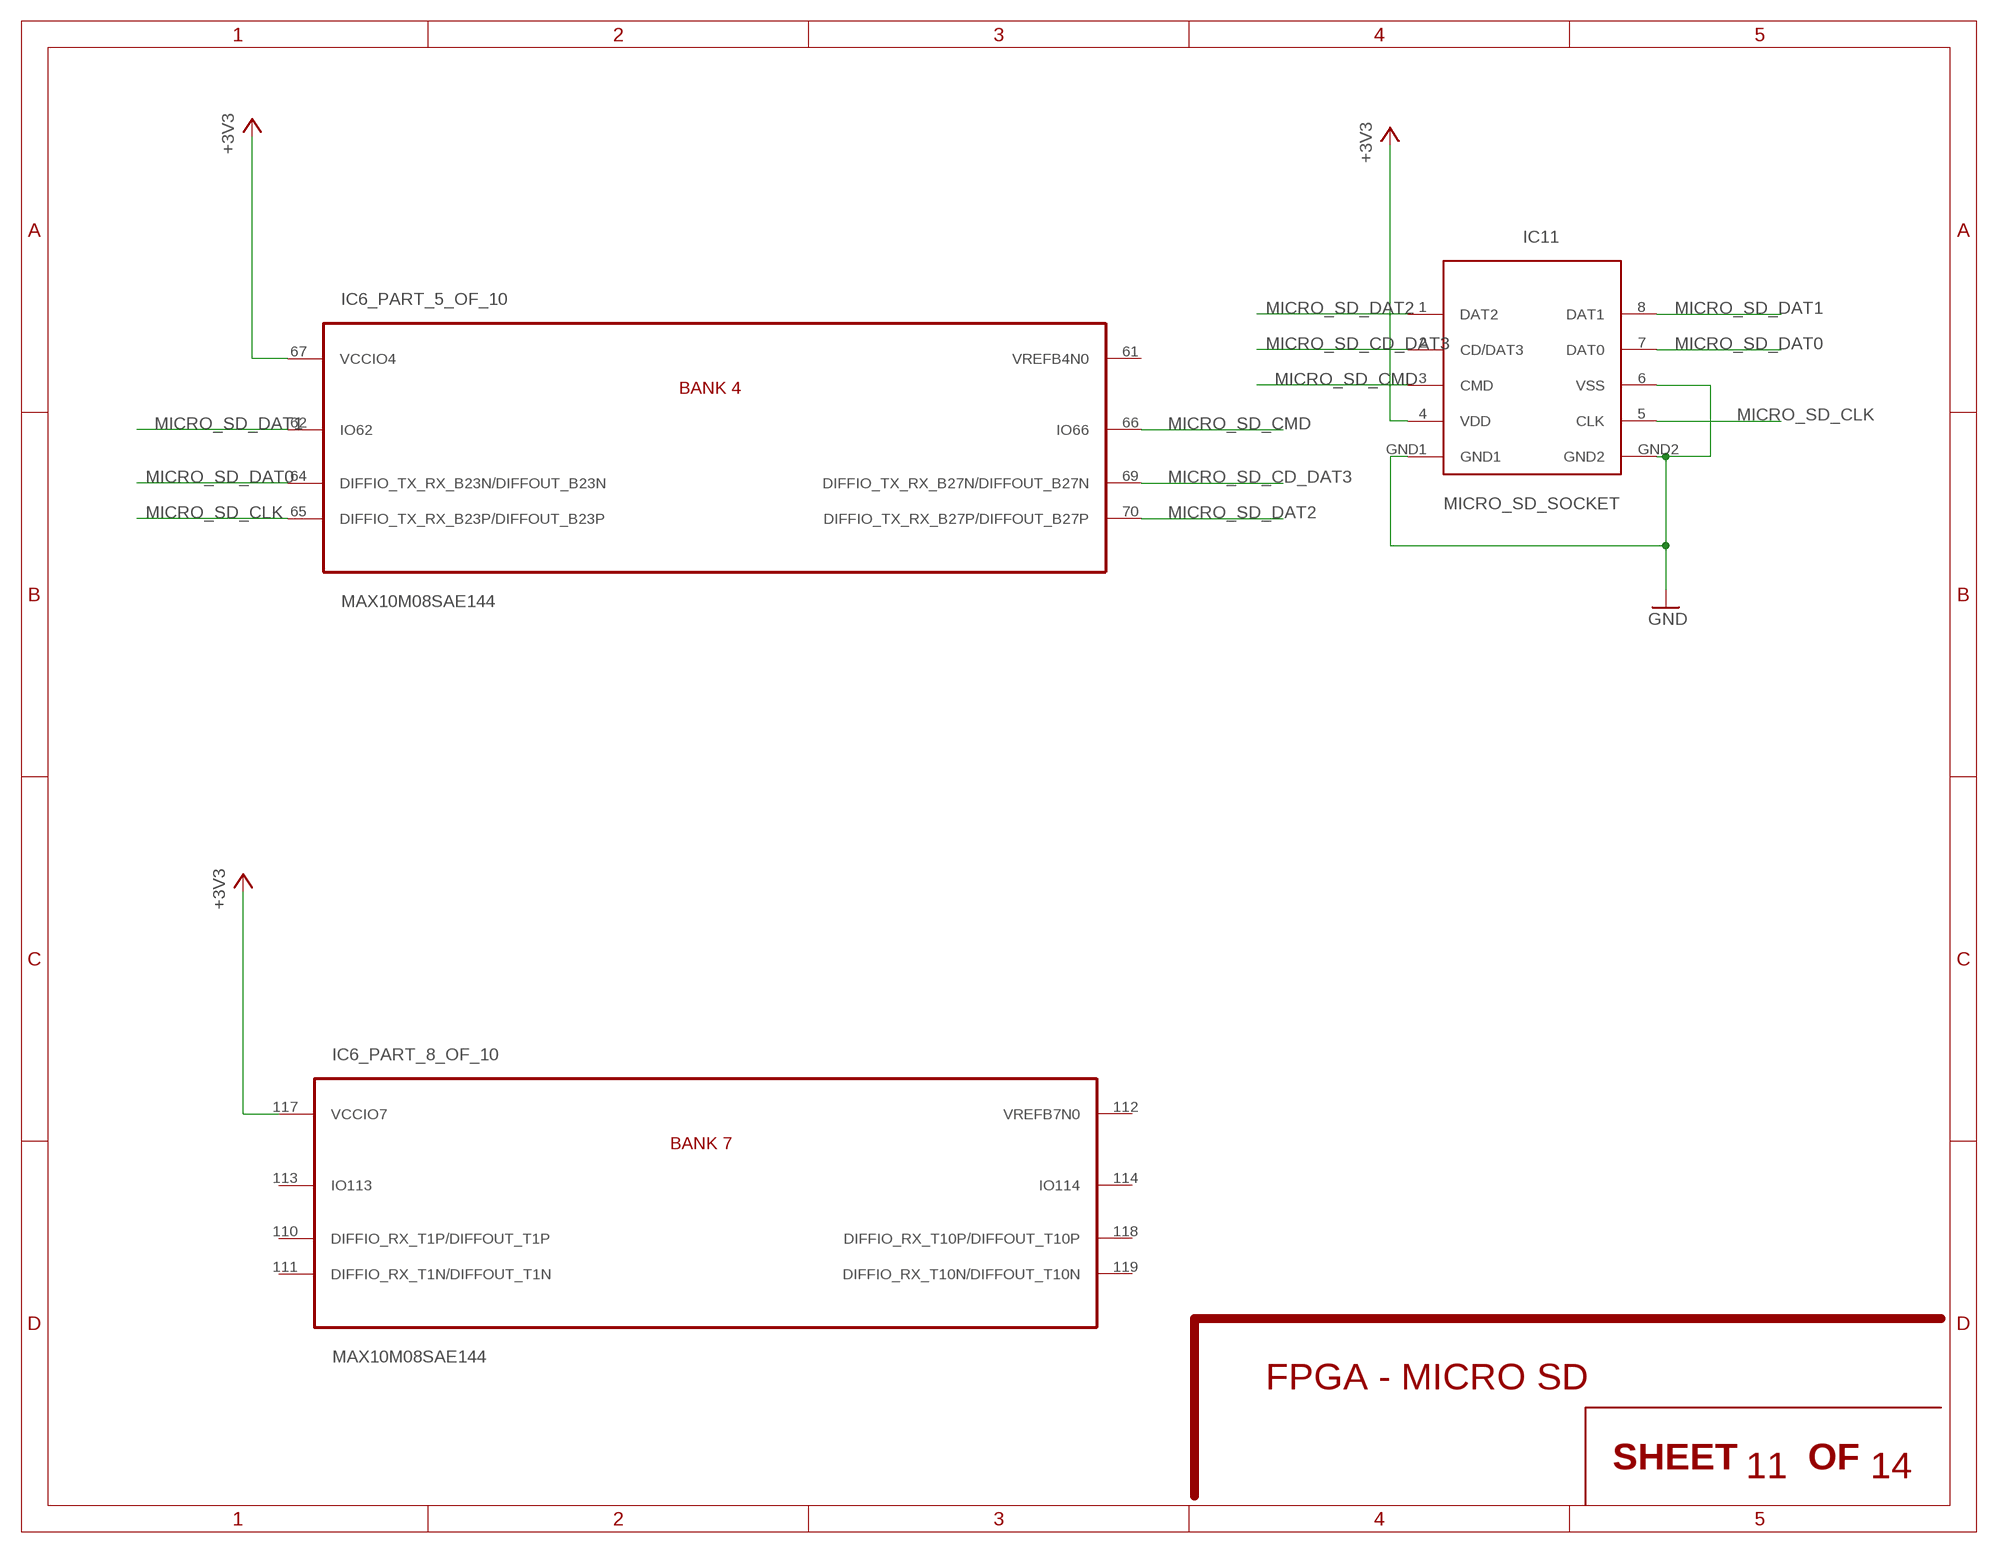
[diagram p10: schematic, sheet 11]
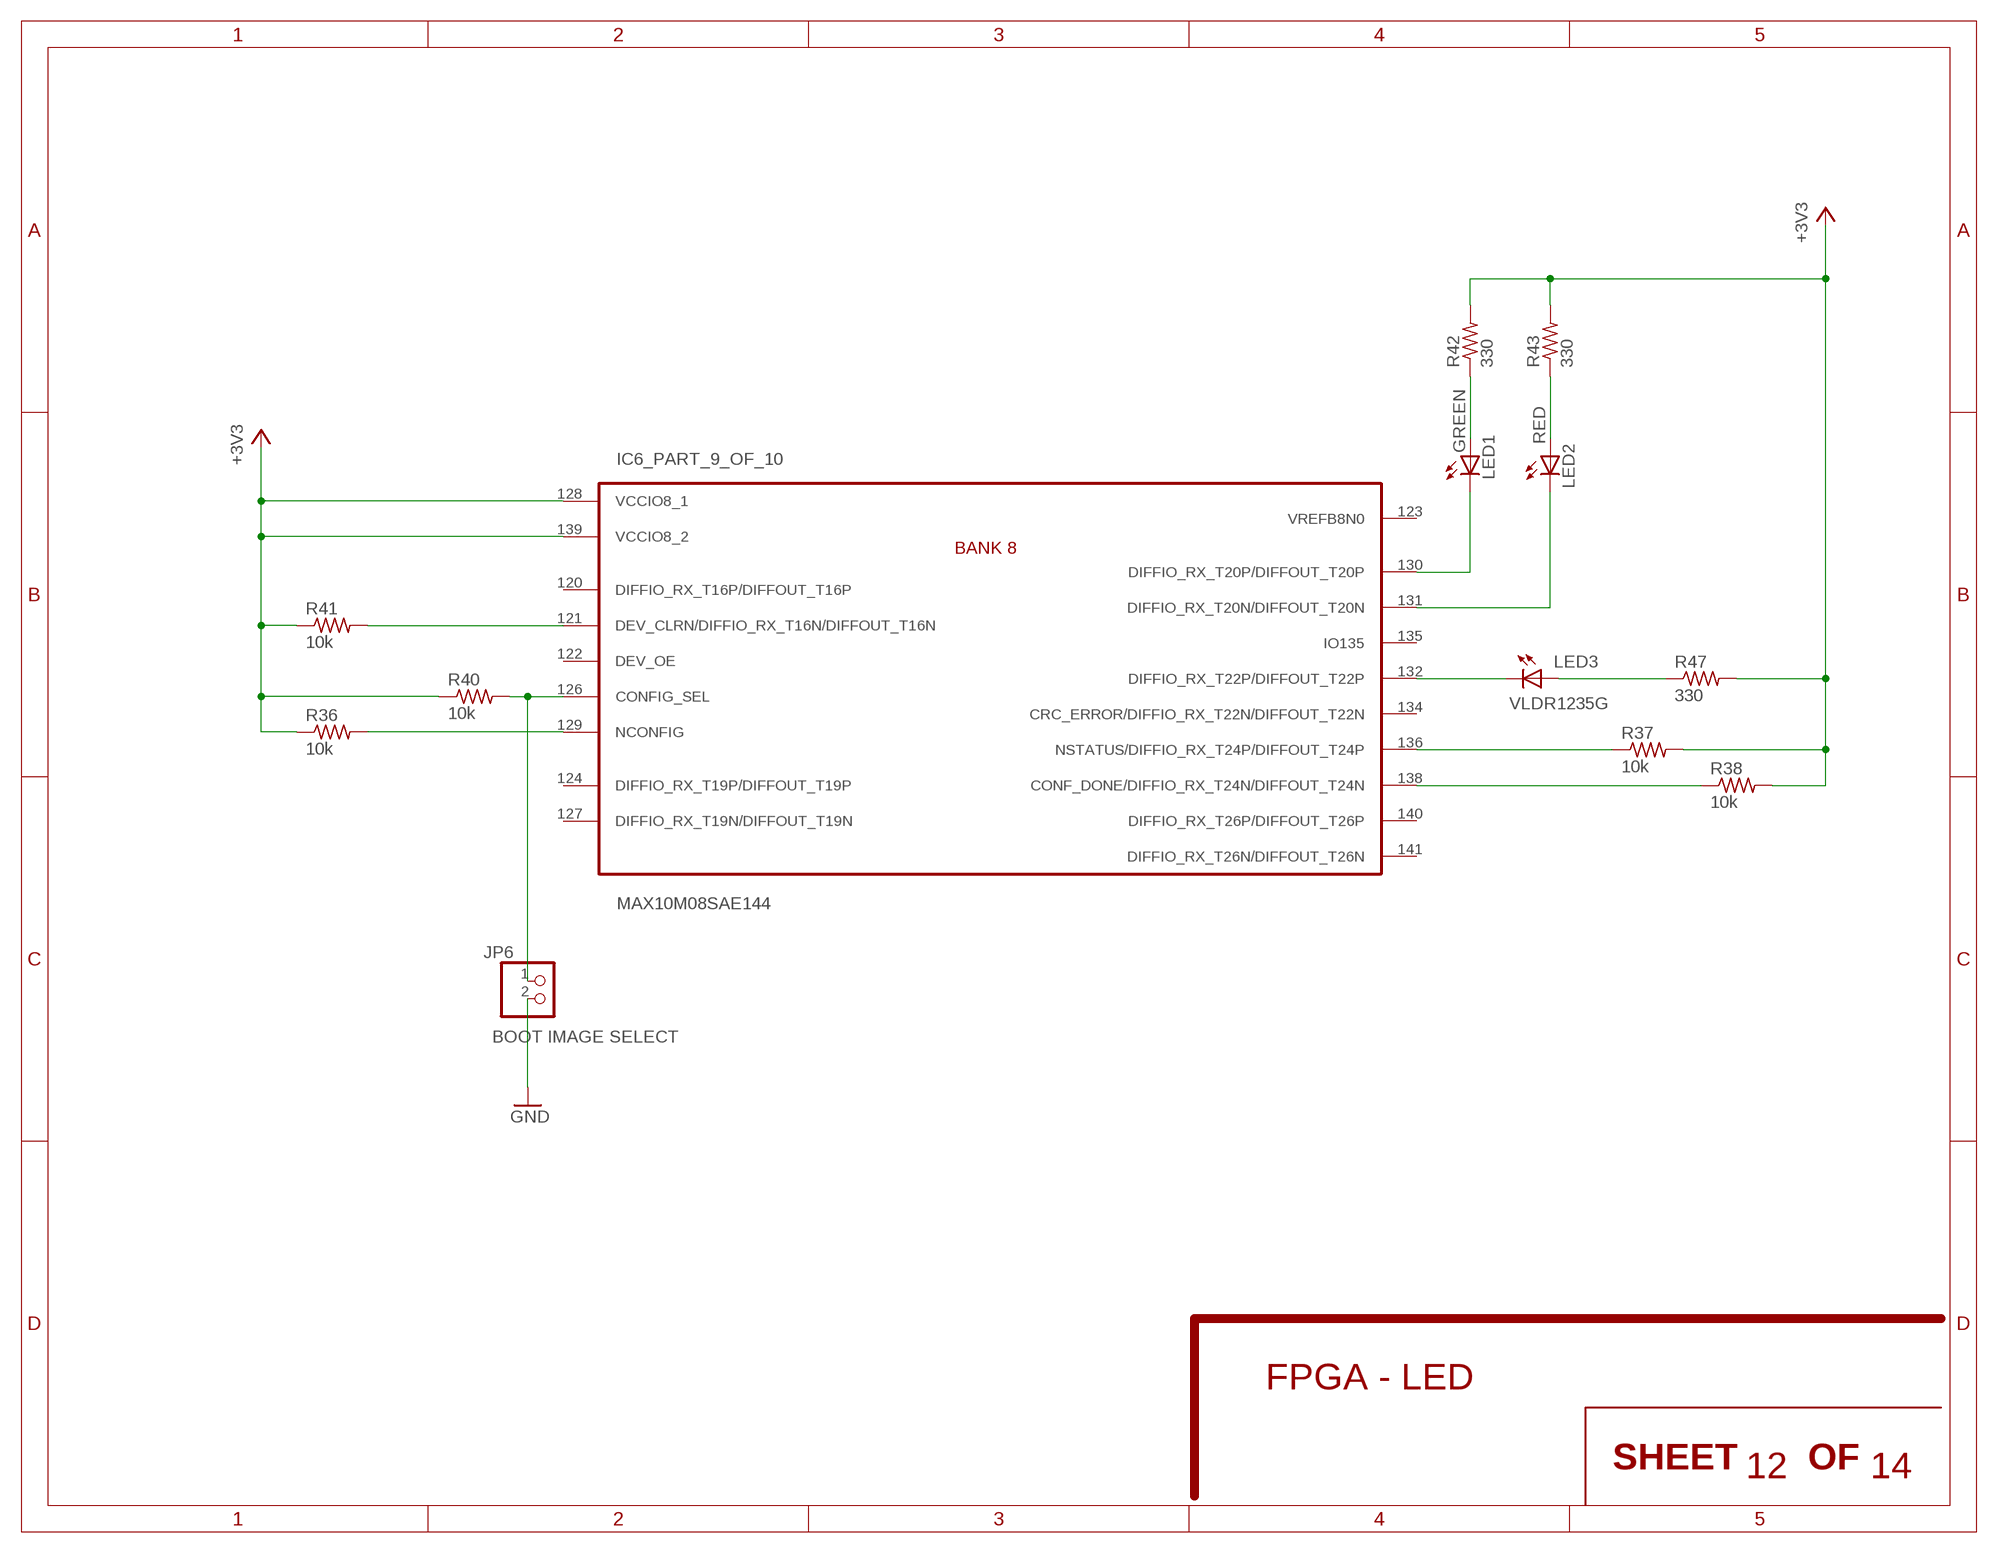
[diagram p11: schematic, sheet 12]
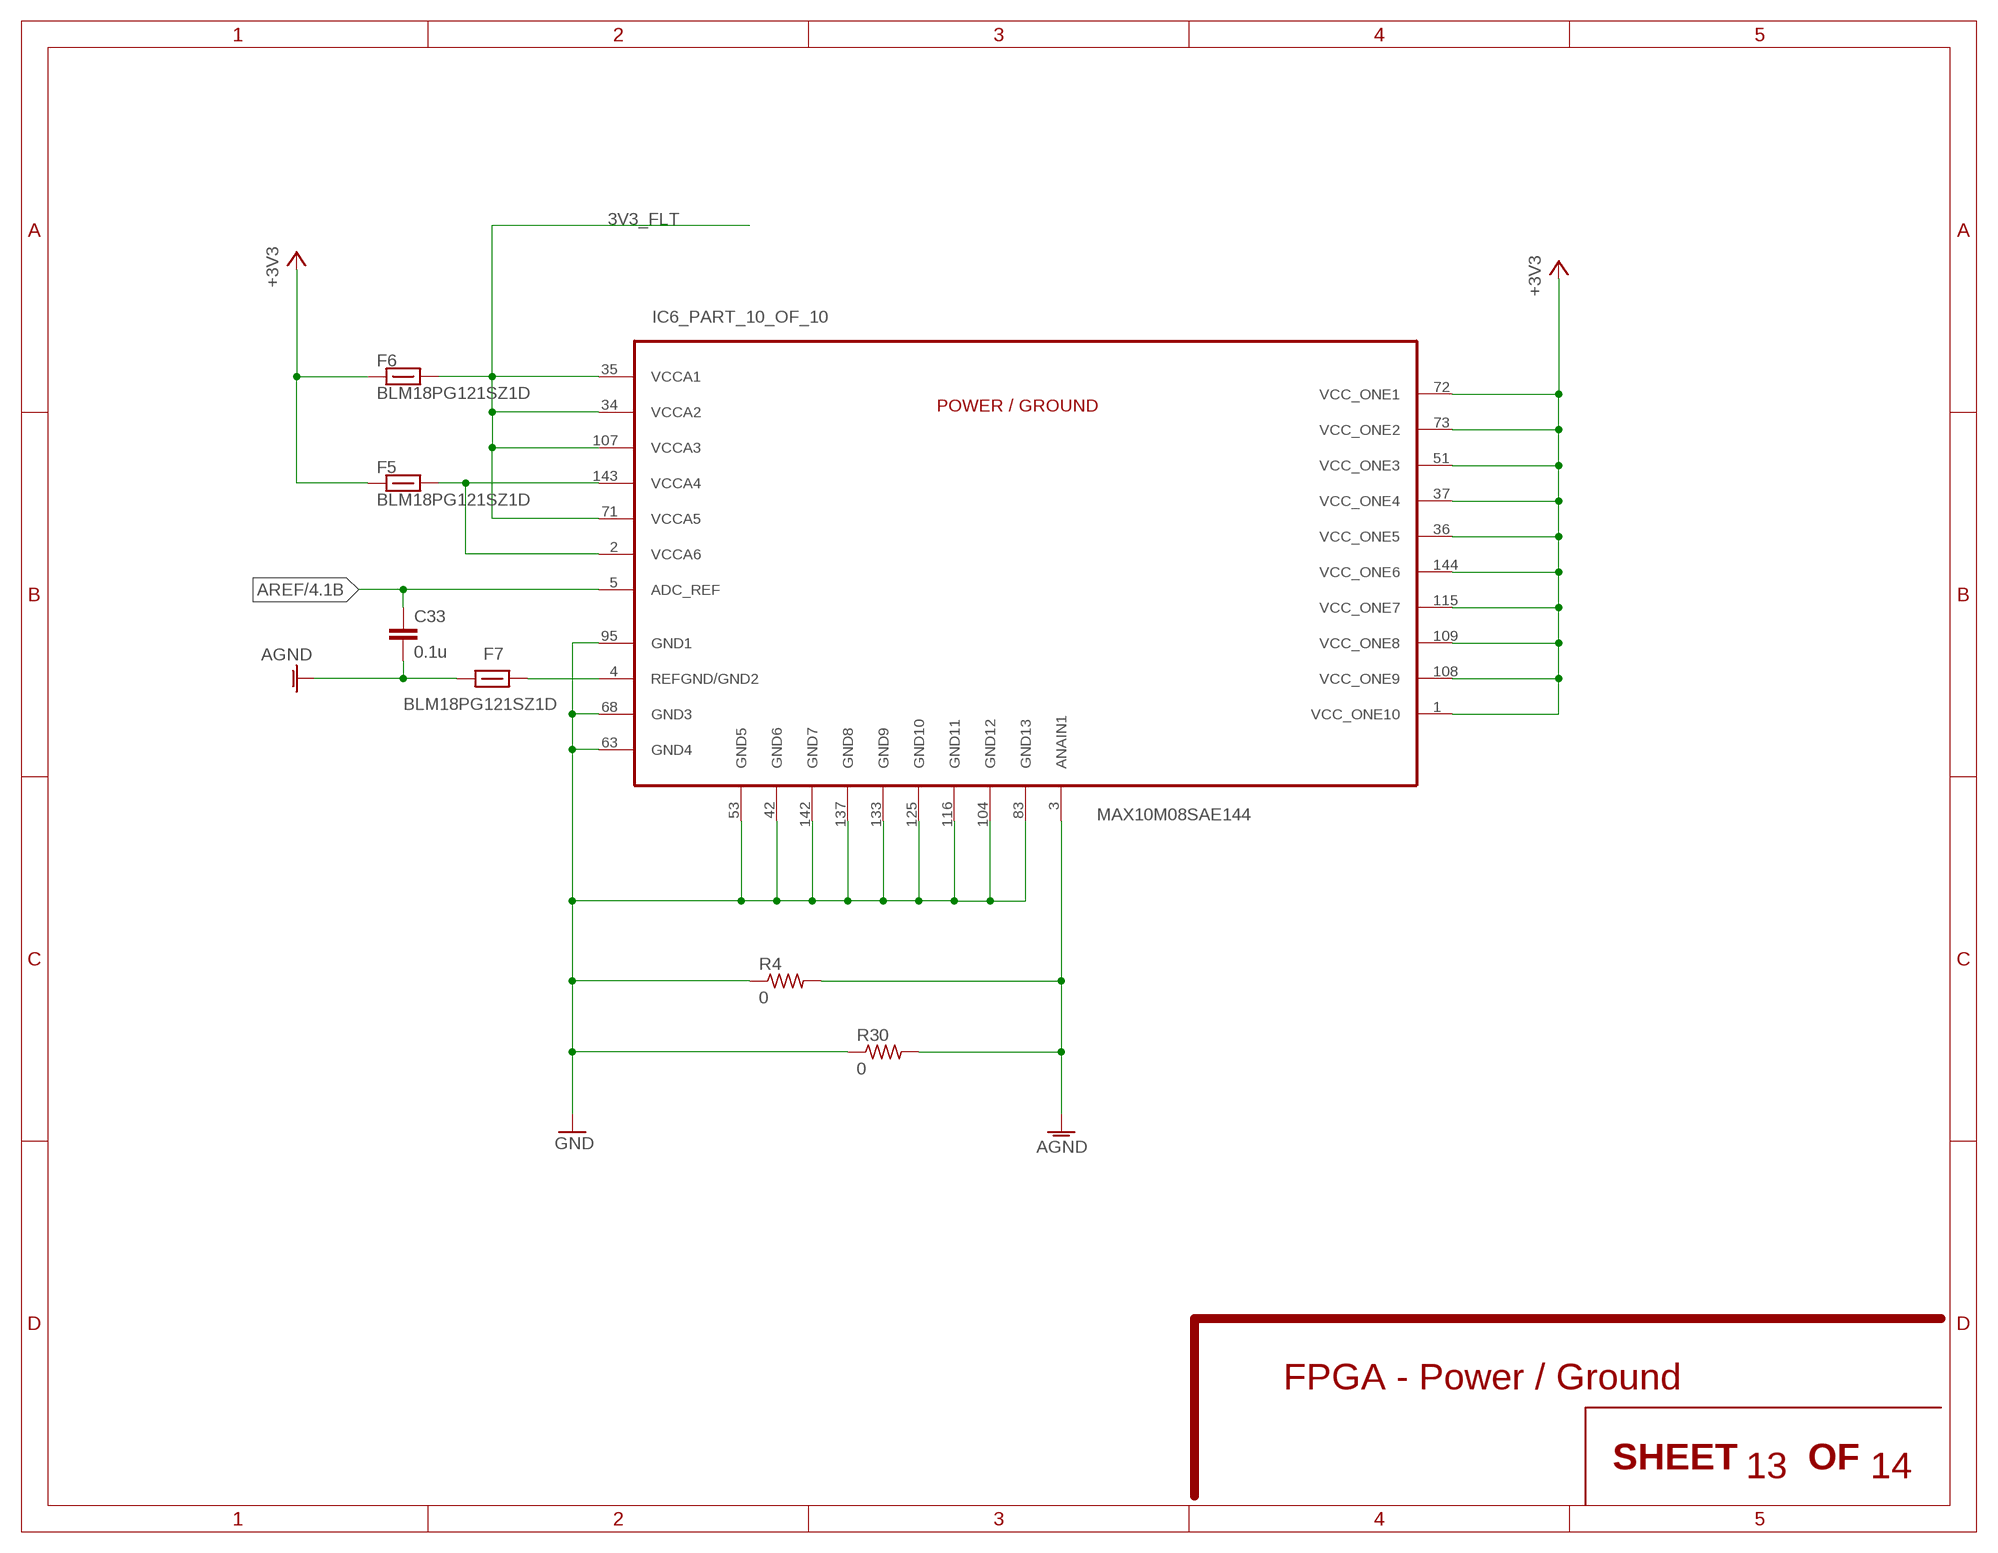
[diagram p12: schematic, sheet 13]
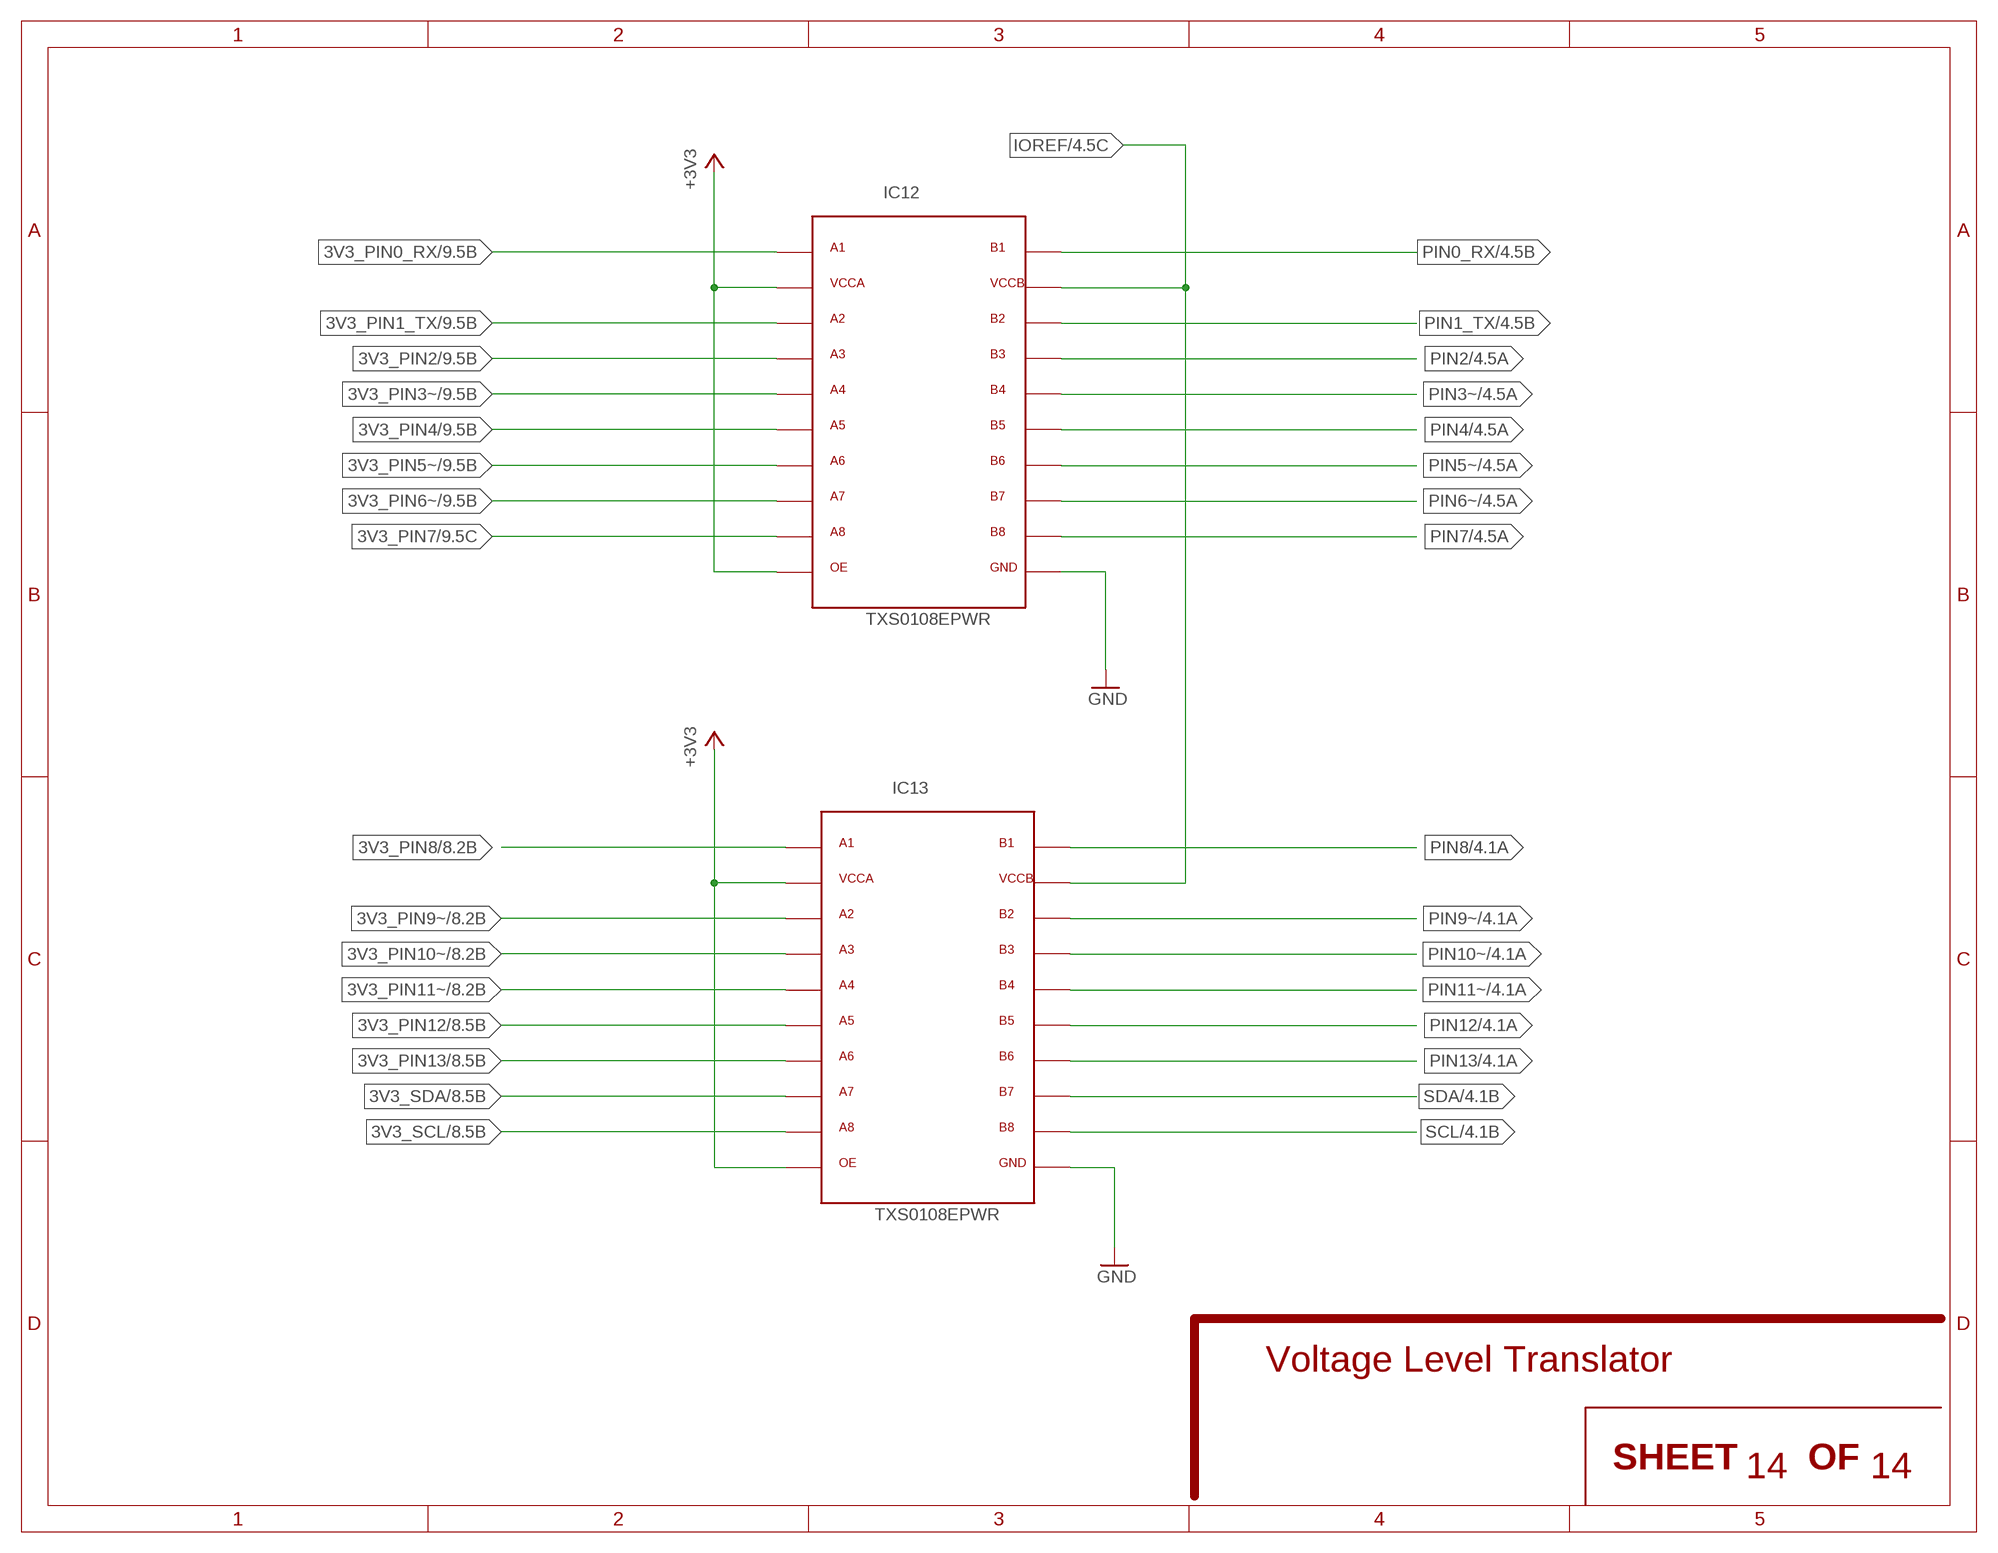
[diagram p13: schematic, sheet 14]

(export (version "E")
  (design (tool "Eeschema 10.0.6"))
  (components
    (comp (ref "IC12")
      (value "TXS0108EPWR")
      (footprint "eagle-import:TSSOP8")
      (fields (field (name "MF") "Texas Instruments"))
      (libsource (lib "eagle-import") (part "TXS0108E"))
    )
    (comp (ref "IC13")
      (value "TXS0108EPWR")
      (footprint "eagle-import:TSSOP8")
      (fields (field (name "MF") "Texas Instruments"))
      (libsource (lib "eagle-import") (part "TXS0108E"))
    )
    (comp (ref "C19")
      (value "1000p")
      (footprint "eagle-import:VISHAY-R-0603")
      (fields (field (name "MF") "Vishay") (field (name "MPN") "VJ0603Y102JXJPW1BC"))
      (libsource (lib "eagle-import") (part "C-US_1000P"))
    )
    (comp (ref "C20")
      (value "1000p")
      (footprint "eagle-import:VISHAY-R-0603")
      (fields (field (name "MF") "Vishay") (field (name "MPN") "VJ0603Y102JXJPW1BC"))
      (libsource (lib "eagle-import") (part "C-US_1000P"))
    )
    (comp (ref "C21")
      (value "1000p")
      (footprint "eagle-import:VISHAY-R-0603")
      (fields (field (name "MF") "Vishay") (field (name "MPN") "VJ0603Y102JXJPW1BC"))
      (libsource (lib "eagle-import") (part "C-US_1000P"))
    )
    (comp (ref "C22")
      (value "1000p")
      (footprint "eagle-import:VISHAY-R-0603")
      (fields (field (name "MF") "Vishay") (field (name "MPN") "VJ0603Y102JXJPW1BC"))
      (libsource (lib "eagle-import") (part "C-US_1000P"))
    )
    (comp (ref "C23")
      (value "1000p")
      (footprint "eagle-import:VISHAY-R-0603")
      (fields (field (name "MF") "Vishay") (field (name "MPN") "VJ0603Y102JXJPW1BC"))
      (libsource (lib "eagle-import") (part "C-US_1000P"))
    )
    (comp (ref "C24")
      (value "1000p")
      (footprint "eagle-import:VISHAY-R-0603")
      (fields (field (name "MF") "Vishay") (field (name "MPN") "VJ0603Y102JXJPW1BC"))
      (libsource (lib "eagle-import") (part "C-US_1000P"))
    )
    (comp (ref "F4")
      (value "BLM18PG121SZ1D")
      (footprint "eagle-import:0603-BEAD")
      (fields (field (name "MF") "muRata"))
      (libsource (lib "eagle-import") (part "BLM18PG"))
    )
    (comp (ref "IC6")
      (value "MAX10M08SAE144")
      (footprint "eagle-import:EQFP144")
      (fields (field (name "MF") "Altera") (field (name "MPN") "10M08SAE144C8G"))
      (libsource (lib "eagle-import") (part "MAX10M08SAE144"))
    )
    (comp (ref "R23")
      (value "100")
      (footprint "eagle-import:VISHAY-R-0603")
      (fields (field (name "MF") "Vishay") (field (name "MPN") "CRCW0603100RFKEA"))
      (libsource (lib "eagle-import") (part "R-US_100"))
    )
    (comp (ref "R24")
      (value "100")
      (footprint "eagle-import:VISHAY-R-0603")
      (fields (field (name "MF") "Vishay") (field (name "MPN") "CRCW0603100RFKEA"))
      (libsource (lib "eagle-import") (part "R-US_100"))
    )
    (comp (ref "R25")
      (value "100")
      (footprint "eagle-import:VISHAY-R-0603")
      (fields (field (name "MF") "Vishay") (field (name "MPN") "CRCW0603100RFKEA"))
      (libsource (lib "eagle-import") (part "R-US_100"))
    )
    (comp (ref "R26")
      (value "100")
      (footprint "eagle-import:VISHAY-R-0603")
      (fields (field (name "MF") "Vishay") (field (name "MPN") "CRCW0603100RFKEA"))
      (libsource (lib "eagle-import") (part "R-US_100"))
    )
    (comp (ref "R27")
      (value "100")
      (footprint "eagle-import:VISHAY-R-0603")
      (fields (field (name "MF") "Vishay") (field (name "MPN") "CRCW0603100RFKEA"))
      (libsource (lib "eagle-import") (part "R-US_100"))
    )
    (comp (ref "R28")
      (value "100")
      (footprint "eagle-import:VISHAY-R-0603")
      (fields (field (name "MF") "Vishay") (field (name "MPN") "CRCW0603100RFKEA"))
      (libsource (lib "eagle-import") (part "R-US_100"))
    )
    (comp (ref "IC10")
      (value "SRAM")
      (footprint "eagle-import:TSSOP-ST-8")
      (fields (field (name "MF") "Microchip Technology") (field (name "MPN") "23LC1024-I/ST"))
      (libsource (lib "eagle-import") (part "23LC1024"))
    )
    (comp (ref "IC14")
      (value "12MHz")
      (footprint "eagle-import:KC7050K")
      (fields (field (name "MF") "AVX") (field (name "MPN") "KC7050K12.0000C1GE00"))
      (libsource (lib "eagle-import") (part "KC7050K12.0000C1GE00"))
    )
    (comp (ref "C9")
      (value "22u")
      (footprint "eagle-import:PANASONIC_B")
      (fields (field (name "MF") "Panasonic") (field (name "MPN") "EEE-FK1A220AR"))
      (libsource (lib "eagle-import") (part "CPOL_USB22U"))
    )
    (comp (ref "C10")
      (value "0.1u")
      (footprint "eagle-import:0603-CAP")
      (fields (field (name "MF") "Vishay") (field (name "MPN") "VJ0603Y104JXJPW1BC"))
      (libsource (lib "eagle-import") (part "C-US_0.1U"))
    )
    (comp (ref "C11")
      (value "0.1u")
      (footprint "eagle-import:0603-CAP")
      (fields (field (name "MF") "Vishay") (field (name "MPN") "VJ0603Y104JXJPW1BC"))
      (libsource (lib "eagle-import") (part "C-US_0.1U"))
    )
    (comp (ref "F1")
      (value "BLM18PG121SZ1D")
      (footprint "eagle-import:0603-BEAD")
      (fields (field (name "MF") "muRata"))
      (libsource (lib "eagle-import") (part "BLM18PG"))
    )
    (comp (ref "IC5")
      (value "FT232RL")
      (footprint "eagle-import:SSOP28")
      (fields (field (name "MF") "FTDI"))
      (libsource (lib "eagle-import") (part "FT232RL"))
    )
    (comp (ref "J2")
      (value "MICRO-USB-B")
      (footprint "eagle-import:SD-47346-001")
      (fields (field (name "MF") "Molex") (field (name "MPN") "47346-1001"))
      (libsource (lib "eagle-import") (part "MICRO-USB-B-REC-47346-001"))
    )
    (comp (ref "LED_RX")
      (value "GREEN")
      (footprint "eagle-import:HARVATEK_0603")
      (fields (field (name "MF") "Inolux / Harvatek") (field (name "MPN") "HT-193UYG-5592"))
      (libsource (lib "eagle-import") (part "HT--193UYG-5592-GREEN"))
    )
    (comp (ref "LED_TX")
      (value "RED")
      (footprint "eagle-import:HARVATEK_0603")
      (fields (field (name "MF") "Inolux / Harvatek") (field (name "MPN") "HT-191URO-5502"))
      (libsource (lib "eagle-import") (part "HT--191URO-5502-RED"))
    )
    (comp (ref "R9")
      (value "330")
      (footprint "eagle-import:VISHAY-R-0603")
      (fields (field (name "MF") "Vishay") (field (name "MPN") "CRCW0603330RFKEA"))
      (libsource (lib "eagle-import") (part "R-US_330"))
    )
    (comp (ref "R10")
      (value "330")
      (footprint "eagle-import:VISHAY-R-0603")
      (fields (field (name "MF") "Vishay") (field (name "MPN") "CRCW0603330RFKEA"))
      (libsource (lib "eagle-import") (part "R-US_330"))
    )
    (comp (ref "J7")
      (value "ALTERA_JTAG")
      (footprint "eagle-import:2X05")
      (fields (field (name "MF") "Harwin") (field (name "MPN") "M20-9760546 "))
      (libsource (lib "eagle-import") (part "ALTERA_JTAG"))
    )
    (comp (ref "R33")
      (value "10k")
      (footprint "eagle-import:VISHAY-R-0603")
      (fields (field (name "MF") "Vishay") (field (name "MPN") "CRCW060310K0FKEA"))
      (libsource (lib "eagle-import") (part "R-US_10K"))
    )
    (comp (ref "R34")
      (value "10k")
      (footprint "eagle-import:VISHAY-R-0603")
      (fields (field (name "MF") "Vishay") (field (name "MPN") "CRCW060310K0FKEA"))
      (libsource (lib "eagle-import") (part "R-US_10K"))
    )
    (comp (ref "R35")
      (value "10k")
      (footprint "eagle-import:VISHAY-R-0603")
      (fields (field (name "MF") "Vishay") (field (name "MPN") "CRCW060310K0FKEA"))
      (libsource (lib "eagle-import") (part "R-US_10K"))
    )
    (comp (ref "R39")
      (value "1k")
      (footprint "eagle-import:VISHAY-R-0603")
      (fields (field (name "MF") "Vishay") (field (name "MPN") "CRCW06031K00FKEA"))
      (libsource (lib "eagle-import") (part "R-US_1K"))
    )
    (comp (ref "JP6")
      (value "BOOT IMAGE SELECT")
      (footprint "eagle-import:1X02")
      (fields (field (name "MF") "Harwin") (field (name "MPN") "M20-9990246"))
      (libsource (lib "eagle-import") (part "PINHD-1X2"))
    )
    (comp (ref "LED1")
      (value "GREEN")
      (footprint "eagle-import:HARVATEK_0603")
      (fields (field (name "MF") "Inolux / Harvatek") (field (name "MPN") "HT-193UYG-5592"))
      (libsource (lib "eagle-import") (part "HT--193UYG-5592-GREEN"))
    )
    (comp (ref "LED2")
      (value "RED")
      (footprint "eagle-import:HARVATEK_0603")
      (fields (field (name "MF") "Inolux / Harvatek") (field (name "MPN") "HT-191URO-5502"))
      (libsource (lib "eagle-import") (part "HT--191URO-5502-RED"))
    )
    (comp (ref "LED3")
      (value "VLDR1235G")
      (footprint "eagle-import:VISHAY_VLD_1235G")
      (fields (field (name "MF") "Vishay"))
      (libsource (lib "eagle-import") (part "VLD1235G"))
    )
    (comp (ref "R36")
      (value "10k")
      (footprint "eagle-import:VISHAY-R-0603")
      (fields (field (name "MF") "Vishay") (field (name "MPN") "CRCW060310K0FKEA"))
      (libsource (lib "eagle-import") (part "R-US_10K"))
    )
    (comp (ref "R37")
      (value "10k")
      (footprint "eagle-import:VISHAY-R-0603")
      (fields (field (name "MF") "Vishay") (field (name "MPN") "CRCW060310K0FKEA"))
      (libsource (lib "eagle-import") (part "R-US_10K"))
    )
    (comp (ref "R38")
      (value "10k")
      (footprint "eagle-import:VISHAY-R-0603")
      (fields (field (name "MF") "Vishay") (field (name "MPN") "CRCW060310K0FKEA"))
      (libsource (lib "eagle-import") (part "R-US_10K"))
    )
    (comp (ref "R40")
      (value "10k")
      (footprint "eagle-import:VISHAY-R-0603")
      (fields (field (name "MF") "Vishay") (field (name "MPN") "CRCW060310K0FKEA"))
      (libsource (lib "eagle-import") (part "R-US_10K"))
    )
    (comp (ref "R41")
      (value "10k")
      (footprint "eagle-import:VISHAY-R-0603")
      (fields (field (name "MF") "Vishay") (field (name "MPN") "CRCW060310K0FKEA"))
      (libsource (lib "eagle-import") (part "R-US_10K"))
    )
    (comp (ref "R42")
      (value "330")
      (footprint "eagle-import:VISHAY-R-0603")
      (fields (field (name "MF") "Vishay") (field (name "MPN") "CRCW0603330RFKEA"))
      (libsource (lib "eagle-import") (part "R-US_330"))
    )
    (comp (ref "R43")
      (value "330")
      (footprint "eagle-import:VISHAY-R-0603")
      (fields (field (name "MF") "Vishay") (field (name "MPN") "CRCW0603330RFKEA"))
      (libsource (lib "eagle-import") (part "R-US_330"))
    )
    (comp (ref "R47")
      (value "330")
      (footprint "eagle-import:VISHAY-R-0603")
      (fields (field (name "MF") "Vishay") (field (name "MPN") "CRCW0603330RFKEA"))
      (libsource (lib "eagle-import") (part "R-US_330"))
    )
    (comp (ref "C12")
      (value "1p")
      (footprint "eagle-import:0603-CAP")
      (fields (field (name "MF") "Vishay") (field (name "MPN") "VJ0603A1R0BXACW1BC"))
      (libsource (lib "eagle-import") (part "C-US_1P"))
    )
    (comp (ref "C13")
      (value "1p")
      (footprint "eagle-import:0603-CAP")
      (fields (field (name "MF") "Vishay") (field (name "MPN") "VJ0603A1R0BXACW1BC"))
      (libsource (lib "eagle-import") (part "C-US_1P"))
    )
    (comp (ref "C14")
      (value "1p")
      (footprint "eagle-import:0603-CAP")
      (fields (field (name "MF") "Vishay") (field (name "MPN") "VJ0603A1R0BXACW1BC"))
      (libsource (lib "eagle-import") (part "C-US_1P"))
    )
    (comp (ref "C15")
      (value "1p")
      (footprint "eagle-import:0603-CAP")
      (fields (field (name "MF") "Vishay") (field (name "MPN") "VJ0603A1R0BXACW1BC"))
      (libsource (lib "eagle-import") (part "C-US_1P"))
    )
    (comp (ref "C16")
      (value "1p")
      (footprint "eagle-import:0603-CAP")
      (fields (field (name "MF") "Vishay") (field (name "MPN") "VJ0603A1R0BXACW1BC"))
      (libsource (lib "eagle-import") (part "C-US_1P"))
    )
    (comp (ref "C17")
      (value "1p")
      (footprint "eagle-import:0603-CAP")
      (fields (field (name "MF") "Vishay") (field (name "MPN") "VJ0603A1R0BXACW1BC"))
      (libsource (lib "eagle-import") (part "C-US_1P"))
    )
    (comp (ref "F3")
      (value "BLM18PG121SZ1D")
      (footprint "eagle-import:0603-BEAD")
      (fields (field (name "MF") "muRata"))
      (libsource (lib "eagle-import") (part "BLM18PG"))
    )
    (comp (ref "IC7")
      (value "MCP6242T-E/SN")
      (footprint "eagle-import:SOIC-SN-8")
      (fields (field (name "MF") "Microchip Technology"))
      (libsource (lib "eagle-import") (part "MCP6242T-E/SN"))
    )
    (comp (ref "IC8")
      (value "MCP6244T-E/ST")
      (footprint "eagle-import:TSSOP-ST-14")
      (fields (field (name "MF") "Microchip Technology"))
      (libsource (lib "eagle-import") (part "MCP6244T-E/ST"))
    )
    (comp (ref "PT1")
      (value "200k")
      (footprint "eagle-import:PT10LV10")
      (fields (field (name "MF") "Piher") (field (name "MPN") "PT10LV10-204A2020"))
      (libsource (lib "eagle-import") (part "PT10LV10"))
    )
    (comp (ref "R11")
      (value "100k")
      (footprint "eagle-import:VISHAY-R-0603")
      (fields (field (name "MF") "Vishay") (field (name "MPN") "CRCW0603100KFKEA"))
      (libsource (lib "eagle-import") (part "R-US_100K"))
    )
    (comp (ref "R12")
      (value "100k")
      (footprint "eagle-import:VISHAY-R-0603")
      (fields (field (name "MF") "Vishay") (field (name "MPN") "CRCW0603100KFKEA"))
      (libsource (lib "eagle-import") (part "R-US_100K"))
    )
    (comp (ref "R13")
      (value "200k")
      (footprint "eagle-import:VISHAY-R-0603")
      (fields (field (name "MF") "Vishay") (field (name "MPN") "CRCW0603200KFKEA"))
      (libsource (lib "eagle-import") (part "R-US_200K"))
    )
    (comp (ref "R14")
      (value "100k")
      (footprint "eagle-import:VISHAY-R-0603")
      (fields (field (name "MF") "Vishay") (field (name "MPN") "CRCW0603100KFKEA"))
      (libsource (lib "eagle-import") (part "R-US_100K"))
    )
    (comp (ref "R15")
      (value "200k")
      (footprint "eagle-import:VISHAY-R-0603")
      (fields (field (name "MF") "Vishay") (field (name "MPN") "CRCW0603200KFKEA"))
      (libsource (lib "eagle-import") (part "R-US_200K"))
    )
    (comp (ref "R16")
      (value "100k")
      (footprint "eagle-import:VISHAY-R-0603")
      (fields (field (name "MF") "Vishay") (field (name "MPN") "CRCW0603100KFKEA"))
      (libsource (lib "eagle-import") (part "R-US_100K"))
    )
    (comp (ref "R17")
      (value "200k")
      (footprint "eagle-import:VISHAY-R-0603")
      (fields (field (name "MF") "Vishay") (field (name "MPN") "CRCW0603200KFKEA"))
      (libsource (lib "eagle-import") (part "R-US_200K"))
    )
    (comp (ref "R18")
      (value "100k")
      (footprint "eagle-import:VISHAY-R-0603")
      (fields (field (name "MF") "Vishay") (field (name "MPN") "CRCW0603100KFKEA"))
      (libsource (lib "eagle-import") (part "R-US_100K"))
    )
    (comp (ref "R19")
      (value "200k")
      (footprint "eagle-import:VISHAY-R-0603")
      (fields (field (name "MF") "Vishay") (field (name "MPN") "CRCW0603200KFKEA"))
      (libsource (lib "eagle-import") (part "R-US_200K"))
    )
    (comp (ref "R20")
      (value "100k")
      (footprint "eagle-import:VISHAY-R-0603")
      (fields (field (name "MF") "Vishay") (field (name "MPN") "CRCW0603100KFKEA"))
      (libsource (lib "eagle-import") (part "R-US_100K"))
    )
    (comp (ref "R21")
      (value "200k")
      (footprint "eagle-import:VISHAY-R-0603")
      (fields (field (name "MF") "Vishay") (field (name "MPN") "CRCW0603200KFKEA"))
      (libsource (lib "eagle-import") (part "R-US_200K"))
    )
    (comp (ref "R32")
      (value "DNI")
      (footprint "eagle-import:VISHAY-R-0603")
      (fields (field (name "MF") "Vishay") (field (name "MPN") "CRCW060310K0FKEA"))
      (libsource (lib "eagle-import") (part "R-US_10K"))
    )
    (comp (ref "SW1")
      (value "TE-2-1437565-8")
      (footprint "eagle-import:TE-2-1437565-8")
      (fields (field (name "MF") "TE Connectivity") (field (name "MPN") "2-1437565-8"))
      (libsource (lib "eagle-import") (part "PUSH_BUTTON"))
    )
    (comp (ref "C33")
      (value "0.1u")
      (footprint "eagle-import:0603-CAP")
      (fields (field (name "MF") "Vishay") (field (name "MPN") "VJ0603Y104JXJPW1BC"))
      (libsource (lib "eagle-import") (part "C-US_0.1U"))
    )
    (comp (ref "F5")
      (value "BLM18PG121SZ1D")
      (footprint "eagle-import:0603-BEAD")
      (fields (field (name "MF") "muRata"))
      (libsource (lib "eagle-import") (part "BLM18PG"))
    )
    (comp (ref "F6")
      (value "BLM18PG121SZ1D")
      (footprint "eagle-import:0603-BEAD")
      (fields (field (name "MF") "muRata"))
      (libsource (lib "eagle-import") (part "BLM18PG"))
    )
    (comp (ref "F7")
      (value "BLM18PG121SZ1D")
      (footprint "eagle-import:0603-BEAD")
      (fields (field (name "MF") "muRata"))
      (libsource (lib "eagle-import") (part "BLM18PG"))
    )
    (comp (ref "R4")
      (value "0")
      (footprint "eagle-import:VISHAY-R-0603")
      (fields (field (name "MF") "Vishay") (field (name "MPN") "CRCW06030000Z0EAHP"))
      (libsource (lib "eagle-import") (part "R-US_0"))
    )
    (comp (ref "R30")
      (value "0")
      (footprint "eagle-import:VISHAY-R-0603")
      (fields (field (name "MF") "Vishay") (field (name "MPN") "CRCW06030000Z0EAHP"))
      (libsource (lib "eagle-import") (part "R-US_0"))
    )
    (comp (ref "U$2")
      (value "PULSERAIN_LOGO_BIGGER")
      (footprint "eagle-import:PULSERAIN_LOGO_BIGGER")
      (libsource (lib "eagle-import") (part "PULSERAIN_LOGO_BIGGER"))
    )
    (comp (ref "C18")
      (value "0.1u")
      (footprint "eagle-import:0603-CAP")
      (fields (field (name "MF") "Vishay") (field (name "MPN") "VJ0603Y104JXJPW1BC"))
      (libsource (lib "eagle-import") (part "C-US_0.1U"))
    )
    (comp (ref "J8")
      (value "DUINO_IO_HEADER_10")
      (footprint "eagle-import:DUINO_IO_HEADER_10")
      (fields (field (name "MF") "Sullins Connector Solutions") (field (name "MPN") "PPTC101LFBN-RC"))
      (libsource (lib "eagle-import") (part "DUINO_IO_HEADER_10"))
    )
    (comp (ref "J9")
      (value "DUINO_HEADER_8")
      (footprint "eagle-import:DUINO_IO_HEADER_8")
      (fields (field (name "MF") "Sullins Connector Solutions") (field (name "MPN") "PPPC081LFBN-RC"))
      (libsource (lib "eagle-import") (part "DUINO_IO_HEADER_8"))
    )
    (comp (ref "J10")
      (value "DUINO_HEADER_8")
      (footprint "eagle-import:DUINO_PWR_HEADER_8")
      (fields (field (name "MF") "Sullins Connector Solutions") (field (name "MPN") "PPPC081LFBN-RC"))
      (libsource (lib "eagle-import") (part "DUINO_PWR_HEADER_8"))
    )
    (comp (ref "J11")
      (value "DUINO_ANALOG_HEADER_6")
      (footprint "eagle-import:DUINO_ANALOG_HEADER_6")
      (fields (field (name "MF") "Sullins Connector Solutions") (field (name "MPN") "PPTC061LFBN-RC"))
      (libsource (lib "eagle-import") (part "DUINO_ANALOG_HEADER_6"))
    )
    (comp (ref "JP1")
      (value "IOREF JUMPER")
      (footprint "eagle-import:1X03")
      (fields (field (name "MF") "Harwin") (field (name "MPN") "M20-9990346"))
      (libsource (lib "eagle-import") (part "PINHD-1X3"))
    )
    (comp (ref "LED_IOREF")
      (value "BLUE")
      (footprint "eagle-import:HARVATEK_0603")
      (fields (field (name "MF") "Inolux / Harvatek") (field (name "MPN") "HT-193NB-5589"))
      (libsource (lib "eagle-import") (part "HT--193NB-5589-BLUE"))
    )
    (comp (ref "R22")
      (value "330")
      (footprint "eagle-import:VISHAY-R-0603")
      (fields (field (name "MF") "Vishay") (field (name "MPN") "CRCW0603330RFKEA"))
      (libsource (lib "eagle-import") (part "R-US_330"))
    )
    (comp (ref "U$8")
      (value "DUINO")
      (footprint "eagle-import:DUINO")
      (libsource (lib "eagle-import") (part "DUINO"))
    )
    (comp (ref "C3")
      (value "0.1u")
      (footprint "eagle-import:0603-CAP")
      (fields (field (name "MF") "Vishay") (field (name "MPN") "VJ0603Y104JXJPW1BC"))
      (libsource (lib "eagle-import") (part "C-US_0.1U"))
    )
    (comp (ref "C6")
      (value "1u")
      (footprint "eagle-import:VISHAY-R-0603")
      (fields (field (name "MF") "Vishay") (field (name "MPN") "VJ0603V105MXQPW1BC"))
      (libsource (lib "eagle-import") (part "C-US_1U"))
    )
    (comp (ref "C7")
      (value "1u")
      (footprint "eagle-import:VISHAY-R-0603")
      (fields (field (name "MF") "Vishay") (field (name "MPN") "VJ0603V105MXQPW1BC"))
      (libsource (lib "eagle-import") (part "C-US_1U"))
    )
    (comp (ref "C8")
      (value "0.1u")
      (footprint "eagle-import:0603-CAP")
      (fields (field (name "MF") "Vishay") (field (name "MPN") "VJ0603Y104JXJPW1BC"))
      (libsource (lib "eagle-import") (part "C-US_0.1U"))
    )
    (comp (ref "C25")
      (value "1u")
      (footprint "eagle-import:VISHAY-R-0603")
      (fields (field (name "MF") "Vishay") (field (name "MPN") "VJ0603V105MXQPW1BC"))
      (libsource (lib "eagle-import") (part "C-US_1U"))
    )
    (comp (ref "IC3")
      (value "SI3000")
      (footprint "eagle-import:SOIC-16")
      (fields (field (name "MF") "Silicon Labs") (field (name "MPN") "Si3000-C-FS"))
      (libsource (lib "eagle-import") (part "SI3000-C-FS"))
    )
    (comp (ref "J3")
      (value "PHONE_JACK_NOT_SWITCHED")
      (footprint "eagle-import:PHONE_JACK_NOT_SWITCHED")
      (fields (field (name "MF") "Switchcraft") (field (name "MPN") "35RASMT2BHNTRX"))
      (libsource (lib "eagle-import") (part "PHONE_JACK_NOT_SWITCHED"))
    )
    (comp (ref "J4")
      (value "PHONE_JACK_NOT_SWITCHED")
      (footprint "eagle-import:PHONE_JACK_NOT_SWITCHED")
      (fields (field (name "MF") "Switchcraft") (field (name "MPN") "35RASMT2BHNTRX"))
      (libsource (lib "eagle-import") (part "PHONE_JACK_NOT_SWITCHED"))
    )
    (comp (ref "MIC1")
      (value "MEMS_MICROPHONE")
      (footprint "eagle-import:MEMS_MICROPHONE")
      (fields (field (name "MF") "Knowles") (field (name "MPN") "SPU0410HR5H-1"))
      (libsource (lib "eagle-import") (part "MEMS_MICROPHONE"))
    )
    (comp (ref "R5")
      (value "2.2k")
      (footprint "eagle-import:VISHAY-R-0603")
      (fields (field (name "MF") "Vishay") (field (name "MPN") "CRCW06032K20FKEA"))
      (libsource (lib "eagle-import") (part "R-US_2.2K"))
    )
    (comp (ref "R6")
      (value "30")
      (footprint "eagle-import:VISHAY-R-0603")
      (fields (field (name "MF") "Vishay") (field (name "MPN") "CRCW060330R0FKEA"))
      (libsource (lib "eagle-import") (part "R-US_30"))
    )
    (comp (ref "R29")
      (value "30")
      (footprint "eagle-import:VISHAY-R-0603")
      (fields (field (name "MF") "Vishay") (field (name "MPN") "CRCW060330R0FKEA"))
      (libsource (lib "eagle-import") (part "R-US_30"))
    )
    (comp (ref "IC11")
      (value "MICRO_SD_SOCKET")
      (footprint "eagle-import:ALPS-SCHD3A0100")
      (fields (field (name "MF") "ALPS") (field (name "MPN") "SCHD3A0100"))
      (libsource (lib "eagle-import") (part "ALPS-SCHD3A0100"))
    )
    (comp (ref "C1")
      (value "22u")
      (footprint "eagle-import:PANASONIC_B")
      (fields (field (name "MF") "Panasonic") (field (name "MPN") "EEE-FK1A220AR"))
      (libsource (lib "eagle-import") (part "CPOL_USB22U"))
    )
    (comp (ref "C2")
      (value "22u")
      (footprint "eagle-import:PANASONIC_B")
      (fields (field (name "MF") "Panasonic") (field (name "MPN") "EEE-FK1A220AR"))
      (libsource (lib "eagle-import") (part "CPOL_USB22U"))
    )
    (comp (ref "C4")
      (value "22p")
      (footprint "eagle-import:0603-CAP")
      (fields (field (name "MF") "Vishay") (field (name "MPN") "VJ0603A220JXACW1BC"))
      (libsource (lib "eagle-import") (part "C-US_22P"))
    )
    (comp (ref "C5")
      (value "22u")
      (footprint "eagle-import:PANASONIC_B")
      (fields (field (name "MF") "Panasonic") (field (name "MPN") "EEE-FK1A220AR"))
      (libsource (lib "eagle-import") (part "CPOL_USB22U"))
    )
    (comp (ref "D1")
      (value "PMEG3020ER")
      (footprint "eagle-import:SOD123W")
      (fields (field (name "MF") "NXP"))
      (libsource (lib "eagle-import") (part "PMEG3020ER"))
    )
    (comp (ref "IC1")
      (value "AZ1117IH-5.0TRG1")
      (footprint "eagle-import:SOT223")
      (fields (field (name "MF") "Diodes Incorporated"))
      (libsource (lib "eagle-import") (part "AZ1117IH-5.0TRG1"))
    )
    (comp (ref "IC2")
      (value "AP3429A")
      (footprint "eagle-import:TSOT25")
      (fields (field (name "MF") "Diodes Incorporated") (field (name "MPN") "AP3429AKTTR-G1"))
      (libsource (lib "eagle-import") (part "AP3429A"))
    )
    (comp (ref "IC4")
      (value "MCP6241UT-E/LT")
      (footprint "eagle-import:SC-70-5")
      (fields (field (name "MF") "Microchip Technology"))
      (libsource (lib "eagle-import") (part "MCP6241UT-E/LT"))
    )
    (comp (ref "J1")
      (value "RAPC722X")
      (footprint "eagle-import:RAPC722X")
      (fields (field (name "MF") "Switchcraft"))
      (libsource (lib "eagle-import") (part "RAPC722X"))
    )
    (comp (ref "L1")
      (value "2.2u")
      (footprint "eagle-import:DFE252012C")
      (fields (field (name "MF") "muRata") (field (name "MPN") "1239AS-H-2R2M=P2"))
      (libsource (lib "eagle-import") (part "L-US_2.2U"))
    )
    (comp (ref "PMOS1")
      (value "PMOS_SQ1421EDH")
      (footprint "eagle-import:SC70-6L")
      (fields (field (name "MF") "Vishay") (field (name "MPN") " SQ1421EDH-T1_GE3 "))
      (libsource (lib "eagle-import") (part "PMOS_SQ1421EDH"))
    )
    (comp (ref "R1")
      (value "10k")
      (footprint "eagle-import:VISHAY-R-0603")
      (fields (field (name "MF") "Vishay") (field (name "MPN") "CRCW060310K0FKEA"))
      (libsource (lib "eagle-import") (part "R-US_10K"))
    )
    (comp (ref "R2")
      (value "226k, 1%")
      (footprint "eagle-import:VISHAY-R-0603")
      (fields (field (name "MF") "Vishay") (field (name "MPN") "CRCW0603226KFKEA"))
      (libsource (lib "eagle-import") (part "R-US_226K"))
    )
    (comp (ref "R3")
      (value "49.9k, 1%")
      (footprint "eagle-import:VISHAY-R-0603")
      (fields (field (name "MF") "Vishay") (field (name "MPN") "CRCW060349K9FKEA"))
      (libsource (lib "eagle-import") (part "R-US_49K9"))
    )
    (comp (ref "R7")
      (value "10k")
      (footprint "eagle-import:VISHAY-R-0603")
      (fields (field (name "MF") "Vishay") (field (name "MPN") "CRCW060310K0FKEA"))
      (libsource (lib "eagle-import") (part "R-US_10K"))
    )
    (comp (ref "R8")
      (value "10k")
      (footprint "eagle-import:VISHAY-R-0603")
      (fields (field (name "MF") "Vishay") (field (name "MPN") "CRCW060310K0FKEA"))
      (libsource (lib "eagle-import") (part "R-US_10K"))
    )
  )
  (nets
    (net (code "1") (name "+3V3") (class "Default")
      (node (ref "C4") (pin "1") (pinfunction "1_1") (pintype "passive"))
      (node (ref "C5") (pin "+") (pinfunction "+_+") (pintype "passive"))
      (node (ref "F4") (pin "1") (pinfunction "1_1") (pintype "passive"))
      (node (ref "F5") (pin "1") (pinfunction "1_1") (pintype "passive"))
      (node (ref "F6") (pin "1") (pinfunction "1_1") (pintype "passive"))
      (node (ref "IC10") (pin "8") (pinfunction "VCC_8") (pintype "input"))
      (node (ref "IC11") (pin "4") (pinfunction "VDD_4") (pintype "input"))
      (node (ref "IC12") (pin "10") (pinfunction "10_10") (pintype "bidirectional"))
      (node (ref "IC12") (pin "2") (pinfunction "2_2") (pintype "input"))
      (node (ref "IC13") (pin "10") (pinfunction "10_10") (pintype "bidirectional"))
      (node (ref "IC13") (pin "2") (pinfunction "2_2") (pintype "input"))
      (node (ref "IC14") (pin "1") (pinfunction "EN_1") (pintype "input"))
      (node (ref "IC14") (pin "4") (pinfunction "VCC_4") (pintype "input"))
      (node (ref "IC3") (pin "12") (pinfunction "VD_12") (pintype "input"))
      (node (ref "IC4") (pin "3") (pinfunction "-IN_3") (pintype "input"))
      (node (ref "IC6") (pin "1") (pinfunction "VCC_ONE10_1") (pintype "input"))
      (node (ref "IC6") (pin "103") (pinfunction "VCCIO6_2_103") (pintype "input"))
      (node (ref "IC6") (pin "108") (pinfunction "VCC_ONE9_108") (pintype "input"))
      (node (ref "IC6") (pin "109") (pinfunction "VCC_ONE8_109") (pintype "input"))
      (node (ref "IC6") (pin "115") (pinfunction "VCC_ONE7_115") (pintype "input"))
      (node (ref "IC6") (pin "117") (pinfunction "VCCIO7_117") (pintype "input"))
      (node (ref "IC6") (pin "128") (pinfunction "VCCIO8_1_128") (pintype "input"))
      (node (ref "IC6") (pin "139") (pinfunction "VCCIO8_2_139") (pintype "input"))
      (node (ref "IC6") (pin "144") (pinfunction "VCC_ONE6_144") (pintype "input"))
      (node (ref "IC6") (pin "23") (pinfunction "VCCIO1B_23") (pintype "input"))
      (node (ref "IC6") (pin "31") (pinfunction "VCCIO2_31") (pintype "input"))
      (node (ref "IC6") (pin "36") (pinfunction "VCC_ONE5_36") (pintype "input"))
      (node (ref "IC6") (pin "37") (pinfunction "VCC_ONE4_37") (pintype "input"))
      (node (ref "IC6") (pin "40") (pinfunction "VCCIO3_1_40") (pintype "input"))
      (node (ref "IC6") (pin "49") (pinfunction "VCCIO3_2_49") (pintype "input"))
      (node (ref "IC6") (pin "51") (pinfunction "VCC_ONE3_51") (pintype "input"))
      (node (ref "IC6") (pin "67") (pinfunction "VCCIO4_67") (pintype "input"))
      (node (ref "IC6") (pin "72") (pinfunction "VCC_ONE1_72") (pintype "input"))
      (node (ref "IC6") (pin "73") (pinfunction "VCC_ONE2_73") (pintype "input"))
      (node (ref "IC6") (pin "82") (pinfunction "VCCIO5_82") (pintype "input"))
      (node (ref "IC6") (pin "94") (pinfunction "VCCIO6_1_94") (pintype "input"))
      (node (ref "J10") (pin "3.3V") (pinfunction "3.3V_3.3V") (pintype "bidirectional"))
      (node (ref "J7") (pin "4") (pinfunction "4_4") (pintype "passive"))
      (node (ref "JP1") (pin "3") (pinfunction "3_3") (pintype "passive"))
      (node (ref "L1") (pin "2") (pinfunction "2_2") (pintype "passive"))
      (node (ref "R2") (pin "P$2") (pinfunction "2_P$2") (pintype "passive"))
      (node (ref "R32") (pin "P$1") (pinfunction "1_P$1") (pintype "passive"))
      (node (ref "R33") (pin "P$1") (pinfunction "1_P$1") (pintype "passive"))
      (node (ref "R34") (pin "P$2") (pinfunction "2_P$2") (pintype "passive"))
      (node (ref "R35") (pin "P$2") (pinfunction "2_P$2") (pintype "passive"))
      (node (ref "R36") (pin "P$1") (pinfunction "1_P$1") (pintype "passive"))
      (node (ref "R37") (pin "P$2") (pinfunction "2_P$2") (pintype "passive"))
      (node (ref "R38") (pin "P$2") (pinfunction "2_P$2") (pintype "passive"))
      (node (ref "R40") (pin "P$1") (pinfunction "1_P$1") (pintype "passive"))
      (node (ref "R41") (pin "P$1") (pinfunction "1_P$1") (pintype "passive"))
      (node (ref "R42") (pin "P$2") (pinfunction "2_P$2") (pintype "passive"))
      (node (ref "R43") (pin "P$2") (pinfunction "2_P$2") (pintype "passive"))
      (node (ref "R47") (pin "P$2") (pinfunction "2_P$2") (pintype "passive"))
    )
    (net (code "2") (name "+5V") (class "Default")
      (node (ref "C2") (pin "+") (pinfunction "+_+") (pintype "passive"))
      (node (ref "F3") (pin "2") (pinfunction "2_2") (pintype "passive"))
      (node (ref "IC1") (pin "2") (pinfunction "2_2") (pintype "input"))
      (node (ref "IC1") (pin "VOUT") (pinfunction "VOUT_VOUT") (pintype "input"))
      (node (ref "IC2") (pin "4") (pinfunction "VIN_4") (pintype "input"))
      (node (ref "IC4") (pin "5") (pinfunction "V+_5") (pintype "input"))
      (node (ref "J10") (pin "5V") (pinfunction "5V_5V") (pintype "bidirectional"))
      (node (ref "JP1") (pin "1") (pinfunction "1_1") (pintype "passive"))
      (node (ref "PMOS1") (pin "4") (pinfunction "S_4") (pintype "passive"))
      (node (ref "R1") (pin "P$1") (pinfunction "1_P$1") (pintype "passive"))
    )
    (net (code "3") (name "3V3_FLT") (class "Default")
      (node (ref "C25") (pin "P$1") (pinfunction "1_P$1") (pintype "passive"))
      (node (ref "F6") (pin "2") (pinfunction "2_2") (pintype "passive"))
      (node (ref "IC3") (pin "13") (pinfunction "VA_13") (pintype "input"))
      (node (ref "IC6") (pin "107") (pinfunction "VCCA3_107") (pintype "input"))
      (node (ref "IC6") (pin "34") (pinfunction "VCCA2_34") (pintype "input"))
      (node (ref "IC6") (pin "35") (pinfunction "VCCA1_35") (pintype "input"))
      (node (ref "IC6") (pin "71") (pinfunction "VCCA5_71") (pintype "input"))
      (node (ref "MIC1") (pin "1") (pinfunction "1_1") (pintype "input"))
    )
    (net (code "4") (name "3V3_PIN0_RX") (class "Default")
      (node (ref "IC12") (pin "1") (pinfunction "1_1") (pintype "bidirectional"))
      (node (ref "IC6") (pin "50") (pinfunction "DIFFIO_TX_RX_B9N/DIFFOUT_B9N_50") (pintype "bidirectional"))
    )
    (net (code "5") (name "3V3_PIN1_TX") (class "Default")
      (node (ref "IC12") (pin "3") (pinfunction "3_3") (pintype "bidirectional"))
      (node (ref "IC6") (pin "52") (pinfunction "DIFFIO_TX_RX_B9P/DIFFOUT_B9P_52") (pintype "bidirectional"))
    )
    (net (code "6") (name "3V3_PIN2") (class "Default")
      (node (ref "IC12") (pin "4") (pinfunction "4_4") (pintype "bidirectional"))
      (node (ref "IC6") (pin "54") (pinfunction "IO54_54") (pintype "bidirectional"))
    )
    (net (code "7") (name "3V3_PIN3~{}") (class "Default")
      (node (ref "IC12") (pin "5") (pinfunction "5_5") (pintype "bidirectional"))
      (node (ref "IC6") (pin "55") (pinfunction "DIFFIO_TX_RX_B12N/DIFFOUT_B12N_55") (pintype "bidirectional"))
    )
    (net (code "8") (name "3V3_PIN4") (class "Default")
      (node (ref "IC12") (pin "6") (pinfunction "6_6") (pintype "bidirectional"))
      (node (ref "IC6") (pin "56") (pinfunction "DIFFIO_TX_RX_B12P/DIFFOUT_B12P_56") (pintype "bidirectional"))
    )
    (net (code "9") (name "3V3_PIN5~{}") (class "Default")
      (node (ref "IC12") (pin "7") (pinfunction "7_7") (pintype "bidirectional"))
      (node (ref "IC6") (pin "57") (pinfunction "DIFFIO_TX_RX_B14N/DIFFOUT_B14N_57") (pintype "bidirectional"))
    )
    (net (code "10") (name "3V3_PIN6~{}") (class "Default")
      (node (ref "IC12") (pin "8") (pinfunction "8_8") (pintype "bidirectional"))
      (node (ref "IC6") (pin "58") (pinfunction "DIFFIO_TX_RX_B14P/DIFFOUT_B14P_58") (pintype "bidirectional"))
    )
    (net (code "11") (name "3V3_PIN7") (class "Default")
      (node (ref "IC12") (pin "9") (pinfunction "9_9") (pintype "bidirectional"))
      (node (ref "IC6") (pin "59") (pinfunction "DIFFIO_TX_RX_B16N/DIFFOUT_B16N_59") (pintype "bidirectional"))
    )
    (net (code "12") (name "3V3_PIN8") (class "Default")
      (node (ref "IC13") (pin "1") (pinfunction "1_1") (pintype "bidirectional"))
      (node (ref "IC6") (pin "92") (pinfunction "DIFFIO_RX_R18P/DIFFOUT_R18P_92") (pintype "bidirectional"))
    )
    (net (code "13") (name "3V3_PIN9~{}") (class "Default")
      (node (ref "IC13") (pin "3") (pinfunction "3_3") (pintype "bidirectional"))
      (node (ref "IC6") (pin "93") (pinfunction "DIFFIO_RX_R18N/DIFFOUT_R18N_93") (pintype "bidirectional"))
    )
    (net (code "14") (name "3V3_PIN10~{}") (class "Default")
      (node (ref "IC13") (pin "4") (pinfunction "4_4") (pintype "bidirectional"))
      (node (ref "IC6") (pin "96") (pinfunction "DPCLK3/DIFFIO_RX_R26P/DIFFOUT_R26P_96") (pintype "bidirectional"))
    )
    (net (code "15") (name "3V3_PIN11~{}") (class "Default")
      (node (ref "IC13") (pin "5") (pinfunction "5_5") (pintype "bidirectional"))
      (node (ref "IC6") (pin "98") (pinfunction "DPCLK2/DIFFIO_RX_R26N/DIFFOUT_R26N_98") (pintype "bidirectional"))
    )
    (net (code "16") (name "3V3_PIN12") (class "Default")
      (node (ref "IC13") (pin "6") (pinfunction "6_6") (pintype "bidirectional"))
      (node (ref "IC6") (pin "99") (pinfunction "DIFFIO_RX_R27P/DIFFOUT_R27P_99") (pintype "bidirectional"))
    )
    (net (code "17") (name "3V3_PIN13") (class "Default")
      (node (ref "IC13") (pin "7") (pinfunction "7_7") (pintype "bidirectional"))
      (node (ref "IC6") (pin "100") (pinfunction "DIFFIO_RX_R28P/DIFFOUT_R28P_100") (pintype "bidirectional"))
    )
    (net (code "18") (name "3V3_SCL") (class "Default")
      (node (ref "IC13") (pin "9") (pinfunction "9_9") (pintype "bidirectional"))
      (node (ref "IC6") (pin "102") (pinfunction "DIFFIO_RX_R28N/DIFFOUT_R28N_102") (pintype "bidirectional"))
    )
    (net (code "19") (name "3V3_SDA") (class "Default")
      (node (ref "IC13") (pin "8") (pinfunction "8_8") (pintype "bidirectional"))
      (node (ref "IC6") (pin "101") (pinfunction "DIFFIO_RX_R27N/DIFFOUT_R27N_101") (pintype "bidirectional"))
    )
    (net (code "20") (name "5V_FLT") (class "Default")
      (node (ref "F3") (pin "1") (pinfunction "1_1") (pintype "passive"))
      (node (ref "IC7") (pin "8") (pinfunction "VDD_8") (pintype "input"))
      (node (ref "IC8") (pin "4") (pinfunction "4_4") (pintype "input"))
    )
    (net (code "21") (name "A0") (class "Default")
      (node (ref "J11") (pin "A0") (pinfunction "A0_A0") (pintype "bidirectional"))
      (node (ref "R11") (pin "P$1") (pinfunction "1_P$1") (pintype "passive"))
    )
    (net (code "22") (name "A1") (class "Default")
      (node (ref "J11") (pin "A1") (pinfunction "A1_A1") (pintype "bidirectional"))
      (node (ref "R12") (pin "P$1") (pinfunction "1_P$1") (pintype "passive"))
    )
    (net (code "23") (name "A2") (class "Default")
      (node (ref "J11") (pin "A2") (pinfunction "A2_A2") (pintype "bidirectional"))
      (node (ref "R14") (pin "P$1") (pinfunction "1_P$1") (pintype "passive"))
    )
    (net (code "24") (name "A3") (class "Default")
      (node (ref "J11") (pin "A3") (pinfunction "A3_A3") (pintype "bidirectional"))
      (node (ref "R16") (pin "P$1") (pinfunction "1_P$1") (pintype "passive"))
    )
    (net (code "25") (name "A4") (class "Default")
      (node (ref "J11") (pin "A4") (pinfunction "A4_A4") (pintype "bidirectional"))
      (node (ref "R20") (pin "P$1") (pinfunction "1_P$1") (pintype "passive"))
    )
    (net (code "26") (name "A5") (class "Default")
      (node (ref "J11") (pin "A5") (pinfunction "A5_A5") (pintype "bidirectional"))
      (node (ref "R18") (pin "P$1") (pinfunction "1_P$1") (pintype "passive"))
    )
    (net (code "27") (name "ADC_IN0") (class "Default")
      (node (ref "IC7") (pin "1") (pinfunction "1_1") (pintype "output"))
      (node (ref "IC7") (pin "2") (pinfunction "2_2") (pintype "input"))
      (node (ref "R23") (pin "P$1") (pinfunction "1_P$1") (pintype "passive"))
    )
    (net (code "28") (name "ADC_IN1") (class "Default")
      (node (ref "IC7") (pin "6") (pinfunction "6_6") (pintype "input"))
      (node (ref "IC7") (pin "7") (pinfunction "7_7") (pintype "output"))
      (node (ref "R24") (pin "P$1") (pinfunction "1_P$1") (pintype "passive"))
    )
    (net (code "29") (name "ADC_IN2") (class "Default")
      (node (ref "IC8") (pin "1") (pinfunction "1_1") (pintype "output"))
      (node (ref "IC8") (pin "2") (pinfunction "2_2") (pintype "input"))
      (node (ref "R25") (pin "P$1") (pinfunction "1_P$1") (pintype "passive"))
    )
    (net (code "30") (name "ADC_IN3") (class "Default")
      (node (ref "IC8") (pin "6") (pinfunction "6_6") (pintype "input"))
      (node (ref "IC8") (pin "7") (pinfunction "7_7") (pintype "output"))
      (node (ref "R26") (pin "P$1") (pinfunction "1_P$1") (pintype "passive"))
    )
    (net (code "31") (name "ADC_IN4") (class "Default")
      (node (ref "IC8") (pin "13") (pinfunction "13_13") (pintype "input"))
      (node (ref "IC8") (pin "14") (pinfunction "14_14") (pintype "output"))
      (node (ref "R27") (pin "P$2") (pinfunction "2_P$2") (pintype "passive"))
    )
    (net (code "32") (name "ADC_IN5") (class "Default")
      (node (ref "IC8") (pin "8") (pinfunction "8_8") (pintype "output"))
      (node (ref "IC8") (pin "9") (pinfunction "9_9") (pintype "input"))
      (node (ref "R28") (pin "P$2") (pinfunction "2_P$2") (pintype "passive"))
    )
    (net (code "33") (name "AGND") (class "Default")
      (node (ref "C12") (pin "2") (pinfunction "2_2") (pintype "passive"))
      (node (ref "C13") (pin "2") (pinfunction "2_2") (pintype "passive"))
      (node (ref "C14") (pin "2") (pinfunction "2_2") (pintype "passive"))
      (node (ref "C15") (pin "2") (pinfunction "2_2") (pintype "passive"))
      (node (ref "C16") (pin "2") (pinfunction "2_2") (pintype "passive"))
      (node (ref "C17") (pin "2") (pinfunction "2_2") (pintype "passive"))
      (node (ref "C19") (pin "P$2") (pinfunction "2_P$2") (pintype "passive"))
      (node (ref "C20") (pin "P$2") (pinfunction "2_P$2") (pintype "passive"))
      (node (ref "C21") (pin "P$2") (pinfunction "2_P$2") (pintype "passive"))
      (node (ref "C22") (pin "P$2") (pinfunction "2_P$2") (pintype "passive"))
      (node (ref "C23") (pin "P$2") (pinfunction "2_P$2") (pintype "passive"))
      (node (ref "C24") (pin "P$2") (pinfunction "2_P$2") (pintype "passive"))
      (node (ref "C25") (pin "P$2") (pinfunction "2_P$2") (pintype "passive"))
      (node (ref "C33") (pin "2") (pinfunction "2_2") (pintype "passive"))
      (node (ref "F7") (pin "1") (pinfunction "1_1") (pintype "passive"))
      (node (ref "IC6") (pin "13") (pinfunction "DIFFIO_RX_L7N/DIFFOUT_L7N/ADC1IN7_13") (pintype "bidirectional"))
      (node (ref "IC6") (pin "14") (pinfunction "DIFFIO_RX_L7P/DIFFOUT_L7P/ADC1IN8_14") (pintype "bidirectional"))
      (node (ref "IC6") (pin "3") (pinfunction "ANAIN1_3") (pintype "input"))
      (node (ref "IC7") (pin "4") (pinfunction "VSS_4") (pintype "input"))
      (node (ref "IC8") (pin "11") (pinfunction "11_11") (pintype "input"))
      (node (ref "J3") (pin "5") (pinfunction "5_5") (pintype "passive"))
      (node (ref "J4") (pin "5") (pinfunction "5_5") (pintype "passive"))
      (node (ref "MIC1") (pin "2") (pinfunction "2_2") (pintype "input"))
      (node (ref "MIC1") (pin "3") (pinfunction "3_3") (pintype "input"))
      (node (ref "PT1") (pin "1E") (pinfunction "1E_1E") (pintype "passive"))
      (node (ref "PT1") (pin "1S") (pinfunction "1S_1S") (pintype "passive"))
      (node (ref "R13") (pin "P$2") (pinfunction "2_P$2") (pintype "passive"))
      (node (ref "R15") (pin "P$1") (pinfunction "1_P$1") (pintype "passive"))
      (node (ref "R17") (pin "P$1") (pinfunction "1_P$1") (pintype "passive"))
      (node (ref "R19") (pin "P$2") (pinfunction "2_P$2") (pintype "passive"))
      (node (ref "R21") (pin "P$1") (pinfunction "1_P$1") (pintype "passive"))
      (node (ref "R30") (pin "P$2") (pinfunction "2_P$2") (pintype "passive"))
      (node (ref "R4") (pin "P$2") (pinfunction "2_P$2") (pintype "passive"))
    )
    (net (code "34") (name "AREF") (class "Default")
      (node (ref "C33") (pin "1") (pinfunction "1_1") (pintype "passive"))
      (node (ref "IC6") (pin "5") (pinfunction "ADC_REF_5") (pintype "input"))
      (node (ref "J8") (pin "AREF") (pinfunction "AREF_AREF") (pintype "bidirectional"))
    )
    (net (code "35") (name "CODEC_FSYNC_N") (class "Default")
      (node (ref "IC3") (pin "6") (pinfunction "FSYNC_N_6") (pintype "bidirectional"))
      (node (ref "IC6") (pin "45") (pinfunction "DIFFIO_TX_RX_B5P/DIFFOUT_B5P_45") (pintype "bidirectional"))
    )
    (net (code "36") (name "CODEC_MCLK") (class "Default")
      (node (ref "IC3") (pin "7") (pinfunction "MCLK_7") (pintype "input"))
      (node (ref "IC6") (pin "44") (pinfunction "DIFFIO_TX_RX_B5N/DIFFOUT_B5N_44") (pintype "bidirectional"))
    )
    (net (code "37") (name "CODEC_RESET_N") (class "Default")
      (node (ref "IC3") (pin "9") (pinfunction "RESET_N_9") (pintype "input"))
      (node (ref "IC6") (pin "38") (pinfunction "DIFFIO_TX_RX_B1N/DIFFOUT_B1N_38") (pintype "bidirectional"))
    )
    (net (code "38") (name "CODEC_SCLK") (class "Default")
      (node (ref "IC3") (pin "8") (pinfunction "SCLK_8") (pintype "bidirectional"))
      (node (ref "IC6") (pin "43") (pinfunction "DIFFIO_TX_RX_B3P/DIFFOUT_B3P_43") (pintype "bidirectional"))
    )
    (net (code "39") (name "CODEC_SDI") (class "Default")
      (node (ref "IC3") (pin "4") (pinfunction "SDI_4") (pintype "input"))
      (node (ref "IC6") (pin "47") (pinfunction "DIFFIO_TX_RX_B7P/DIFFOUT_B7P_47") (pintype "bidirectional"))
    )
    (net (code "40") (name "CODEC_SDO") (class "Default")
      (node (ref "IC3") (pin "5") (pinfunction "SDO_5") (pintype "output"))
      (node (ref "IC6") (pin "46") (pinfunction "DIFFIO_TX_RX_B7N/DIFFOUT_B7N_46") (pintype "bidirectional"))
    )
    (net (code "41") (name "FT232R_CTS_N") (class "Default")
      (node (ref "IC5") (pin "11") (pinfunction "~{CTS}_11") (pintype "input"))
      (node (ref "IC6") (pin "81") (pinfunction "DIFFIO_RX_R7N/DIFFOUT_R7N_81") (pintype "bidirectional"))
    )
    (net (code "42") (name "FT232R_RESET_N") (class "Default")
      (node (ref "IC5") (pin "19") (pinfunction "~{RESET}_19") (pintype "input"))
      (node (ref "IC6") (pin "84") (pinfunction "DIFFIO_RX_R11P/DIFFOUT_R11P_84") (pintype "bidirectional"))
    )
    (net (code "43") (name "FT232R_RTS_N") (class "Default")
      (node (ref "IC5") (pin "3") (pinfunction "~{RTS}_3") (pintype "output"))
      (node (ref "IC6") (pin "76") (pinfunction "DIFFIO_RX_R2N/DIFFOUT_R2N_76") (pintype "bidirectional"))
    )
    (net (code "44") (name "FT232R_RXD") (class "Default")
      (node (ref "IC5") (pin "5") (pinfunction "RXD_5") (pintype "input"))
      (node (ref "IC6") (pin "79") (pinfunction "DIFFIO_RX_R7P/DIFFOUT_R7P_79") (pintype "bidirectional"))
    )
    (net (code "45") (name "FT232R_RXLED_N") (class "Default")
      (node (ref "IC5") (pin "22") (pinfunction "CBUS1_22") (pintype "bidirectional"))
      (node (ref "LED_RX") (pin "C") (pinfunction "C_C") (pintype "passive"))
    )
    (net (code "46") (name "FT232R_TXD") (class "Default")
      (node (ref "IC5") (pin "1") (pinfunction "TXD_1") (pintype "output"))
      (node (ref "IC6") (pin "75") (pinfunction "DIFFIO_RX_R1P/DIFFOUT_R1P_75") (pintype "bidirectional"))
    )
    (net (code "47") (name "FT232R_TXLED_N") (class "Default")
      (node (ref "IC5") (pin "23") (pinfunction "CBUS0_23") (pintype "bidirectional"))
      (node (ref "LED_TX") (pin "C") (pinfunction "C_C") (pintype "passive"))
    )
    (net (code "48") (name "GND") (class "Default")
      (node (ref "C1") (pin "-") (pinfunction "-_-") (pintype "passive"))
      (node (ref "C10") (pin "2") (pinfunction "2_2") (pintype "passive"))
      (node (ref "C11") (pin "2") (pinfunction "2_2") (pintype "passive"))
      (node (ref "C18") (pin "2") (pinfunction "2_2") (pintype "passive"))
      (node (ref "C2") (pin "-") (pinfunction "-_-") (pintype "passive"))
      (node (ref "C5") (pin "-") (pinfunction "-_-") (pintype "passive"))
      (node (ref "C9") (pin "-") (pinfunction "-_-") (pintype "passive"))
      (node (ref "IC1") (pin "1") (pinfunction "1_1") (pintype "input"))
      (node (ref "IC10") (pin "4") (pinfunction "VSS_4") (pintype "input"))
      (node (ref "IC11") (pin "6") (pinfunction "VSS_6") (pintype "input"))
      (node (ref "IC11") (pin "GND1") (pinfunction "GND1_GND1") (pintype "input"))
      (node (ref "IC11") (pin "GND2") (pinfunction "GND2_GND2") (pintype "input"))
      (node (ref "IC12") (pin "11") (pinfunction "11_11") (pintype "input"))
      (node (ref "IC13") (pin "11") (pinfunction "11_11") (pintype "input"))
      (node (ref "IC14") (pin "2") (pinfunction "GND_2") (pintype "input"))
      (node (ref "IC2") (pin "2") (pinfunction "GND_2") (pintype "input"))
      (node (ref "IC3") (pin "14") (pinfunction "GND_14") (pintype "input"))
      (node (ref "IC4") (pin "2") (pinfunction "V-_2") (pintype "input"))
      (node (ref "IC5") (pin "18") (pinfunction "GND_18") (pintype "power_in"))
      (node (ref "IC5") (pin "21") (pinfunction "GND_21") (pintype "power_in"))
      (node (ref "IC5") (pin "25") (pinfunction "GND_25") (pintype "power_in"))
      (node (ref "IC5") (pin "26") (pinfunction "TEST_26") (pintype "input"))
      (node (ref "IC5") (pin "7") (pinfunction "GND_7") (pintype "power_in"))
      (node (ref "IC6") (pin "104") (pinfunction "GND12_104") (pintype "input"))
      (node (ref "IC6") (pin "116") (pinfunction "GND11_116") (pintype "input"))
      (node (ref "IC6") (pin "125") (pinfunction "GND10_125") (pintype "input"))
      (node (ref "IC6") (pin "133") (pinfunction "GND9_133") (pintype "input"))
      (node (ref "IC6") (pin "137") (pinfunction "GND8_137") (pintype "input"))
      (node (ref "IC6") (pin "142") (pinfunction "GND7_142") (pintype "input"))
      (node (ref "IC6") (pin "42") (pinfunction "GND6_42") (pintype "input"))
      (node (ref "IC6") (pin "53") (pinfunction "GND5_53") (pintype "input"))
      (node (ref "IC6") (pin "63") (pinfunction "GND4_63") (pintype "input"))
      (node (ref "IC6") (pin "68") (pinfunction "GND3_68") (pintype "input"))
      (node (ref "IC6") (pin "83") (pinfunction "GND13_83") (pintype "input"))
      (node (ref "IC6") (pin "95") (pinfunction "GND1_95") (pintype "input"))
      (node (ref "J1") (pin "1") (pinfunction "1_1") (pintype "passive"))
      (node (ref "J1") (pin "2") (pinfunction "2_2") (pintype "passive"))
      (node (ref "J10") (pin "GND.") (pinfunction "GND._GND.") (pintype "bidirectional"))
      (node (ref "J10") (pin "GND..") (pinfunction "GND.._GND..") (pintype "bidirectional"))
      (node (ref "J2") (pin "4") (pinfunction "4_4") (pintype "passive"))
      (node (ref "J2") (pin "5") (pinfunction "5_5") (pintype "passive"))
      (node (ref "J7") (pin "10") (pinfunction "10_10") (pintype "passive"))
      (node (ref "J7") (pin "2") (pinfunction "2_2") (pintype "passive"))
      (node (ref "J8") (pin "GND") (pinfunction "GND_GND") (pintype "bidirectional"))
      (node (ref "JP6") (pin "2") (pinfunction "2_2") (pintype "passive"))
      (node (ref "LED_IOREF") (pin "C") (pinfunction "C_C") (pintype "passive"))
      (node (ref "R3") (pin "P$1") (pinfunction "1_P$1") (pintype "passive"))
      (node (ref "R30") (pin "P$1") (pinfunction "1_P$1") (pintype "passive"))
      (node (ref "R39") (pin "P$1") (pinfunction "1_P$1") (pintype "passive"))
      (node (ref "R4") (pin "P$1") (pinfunction "1_P$1") (pintype "passive"))
      (node (ref "R8") (pin "P$1") (pinfunction "1_P$1") (pintype "passive"))
      (node (ref "SW1") (pin "3") (pinfunction "3_3") (pintype "bidirectional"))
      (node (ref "SW1") (pin "4") (pinfunction "4_4") (pintype "bidirectional"))
    )
    (net (code "49") (name "IOREF") (class "Default")
      (node (ref "C18") (pin "1") (pinfunction "1_1") (pintype "passive"))
      (node (ref "IC12") (pin "19") (pinfunction "19_19") (pintype "input"))
      (node (ref "IC13") (pin "19") (pinfunction "19_19") (pintype "input"))
      (node (ref "J10") (pin "I/OREF") (pinfunction "IOREF_I/OREF") (pintype "bidirectional"))
      (node (ref "JP1") (pin "2") (pinfunction "2_2") (pintype "passive"))
      (node (ref "R22") (pin "P$2") (pinfunction "2_P$2") (pintype "passive"))
    )
    (net (code "50") (name "JTAGEN") (class "Default")
      (node (ref "IC6") (pin "15") (pinfunction "JTAGEN_15") (pintype "bidirectional"))
      (node (ref "R33") (pin "P$2") (pinfunction "2_P$2") (pintype "passive"))
    )
    (net (code "51") (name "MICRO_SD_CD_DAT3") (class "Default")
      (node (ref "IC11") (pin "2") (pinfunction "CD/DAT3_2") (pintype "bidirectional"))
      (node (ref "IC6") (pin "69") (pinfunction "DIFFIO_TX_RX_B27N/DIFFOUT_B27N_69") (pintype "bidirectional"))
    )
    (net (code "52") (name "MICRO_SD_CLK") (class "Default")
      (node (ref "IC11") (pin "5") (pinfunction "CLK_5") (pintype "bidirectional"))
      (node (ref "IC6") (pin "65") (pinfunction "DIFFIO_TX_RX_B23P/DIFFOUT_B23P_65") (pintype "bidirectional"))
    )
    (net (code "53") (name "MICRO_SD_CMD") (class "Default")
      (node (ref "IC11") (pin "3") (pinfunction "CMD_3") (pintype "bidirectional"))
      (node (ref "IC6") (pin "66") (pinfunction "IO66_66") (pintype "bidirectional"))
    )
    (net (code "54") (name "MICRO_SD_DAT0") (class "Default")
      (node (ref "IC11") (pin "7") (pinfunction "DAT0_7") (pintype "bidirectional"))
      (node (ref "IC6") (pin "64") (pinfunction "DIFFIO_TX_RX_B23N/DIFFOUT_B23N_64") (pintype "bidirectional"))
    )
    (net (code "55") (name "MICRO_SD_DAT1") (class "Default")
      (node (ref "IC11") (pin "8") (pinfunction "DAT1_8") (pintype "bidirectional"))
      (node (ref "IC6") (pin "62") (pinfunction "IO62_62") (pintype "bidirectional"))
    )
    (net (code "56") (name "MICRO_SD_DAT2") (class "Default")
      (node (ref "IC11") (pin "1") (pinfunction "DAT2_1") (pintype "bidirectional"))
      (node (ref "IC6") (pin "70") (pinfunction "DIFFIO_TX_RX_B27P/DIFFOUT_B27P_70") (pintype "bidirectional"))
    )
    (net (code "57") (name "Net-(C3-Pad2)") (class "Default")
      (node (ref "C3") (pin "2") (pinfunction "2_2") (pintype "passive"))
      (node (ref "J3") (pin "1") (pinfunction "1_1") (pintype "passive"))
    )
    (net (code "58") (name "Net-(C6-1)") (class "Default")
      (node (ref "C6") (pin "P$1") (pinfunction "1_P$1") (pintype "passive"))
      (node (ref "IC3") (pin "16") (pinfunction "SPKRL_16") (pintype "output"))
    )
    (net (code "59") (name "Net-(C6-2)") (class "Default")
      (node (ref "C6") (pin "P$2") (pinfunction "2_P$2") (pintype "passive"))
      (node (ref "R6") (pin "P$2") (pinfunction "2_P$2") (pintype "passive"))
    )
    (net (code "60") (name "Net-(C7-1)") (class "Default")
      (node (ref "C7") (pin "P$1") (pinfunction "1_P$1") (pintype "passive"))
      (node (ref "IC3") (pin "1") (pinfunction "SPKRR_1") (pintype "output"))
    )
    (net (code "61") (name "Net-(C7-2)") (class "Default")
      (node (ref "C7") (pin "P$2") (pinfunction "2_P$2") (pintype "passive"))
      (node (ref "R29") (pin "P$2") (pinfunction "2_P$2") (pintype "passive"))
    )
    (net (code "62") (name "Net-(C8-Pad2)") (class "Default")
      (node (ref "C8") (pin "2") (pinfunction "2_2") (pintype "passive"))
      (node (ref "MIC1") (pin "4") (pinfunction "4_4") (pintype "output"))
    )
    (net (code "63") (name "Net-(C19-1)") (class "Default")
      (node (ref "C19") (pin "P$1") (pinfunction "1_P$1") (pintype "passive"))
      (node (ref "IC6") (pin "6") (pinfunction "DIFFIO_RX_L1N/DIFFOUT_L1N/ADC1IN1_6") (pintype "bidirectional"))
      (node (ref "R23") (pin "P$2") (pinfunction "2_P$2") (pintype "passive"))
    )
    (net (code "64") (name "Net-(C20-1)") (class "Default")
      (node (ref "C20") (pin "P$1") (pinfunction "1_P$1") (pintype "passive"))
      (node (ref "IC6") (pin "7") (pinfunction "DIFFIO_RX_L1P/DIFFOUT_L1P/ADC1IN2_7") (pintype "bidirectional"))
      (node (ref "R24") (pin "P$2") (pinfunction "2_P$2") (pintype "passive"))
    )
    (net (code "65") (name "Net-(C21-1)") (class "Default")
      (node (ref "C21") (pin "P$1") (pinfunction "1_P$1") (pintype "passive"))
      (node (ref "IC6") (pin "8") (pinfunction "DIFFIO_RX_L3N/DIFFOUT_L3N/ADC1IN3_8") (pintype "bidirectional"))
      (node (ref "R25") (pin "P$2") (pinfunction "2_P$2") (pintype "passive"))
    )
    (net (code "66") (name "Net-(C22-1)") (class "Default")
      (node (ref "C22") (pin "P$1") (pinfunction "1_P$1") (pintype "passive"))
      (node (ref "IC6") (pin "10") (pinfunction "DIFFIO_RX_L3P/DIFFOUT_L3P/ADC1IN4_10") (pintype "bidirectional"))
      (node (ref "R26") (pin "P$2") (pinfunction "2_P$2") (pintype "passive"))
    )
    (net (code "67") (name "Net-(C23-1)") (class "Default")
      (node (ref "C23") (pin "P$1") (pinfunction "1_P$1") (pintype "passive"))
      (node (ref "IC6") (pin "11") (pinfunction "DIFFIO_RX_L5N/DIFFOUT_L5N/ADC1IN5_11") (pintype "bidirectional"))
      (node (ref "R27") (pin "P$1") (pinfunction "1_P$1") (pintype "passive"))
    )
    (net (code "68") (name "Net-(C24-1)") (class "Default")
      (node (ref "C24") (pin "P$1") (pinfunction "1_P$1") (pintype "passive"))
      (node (ref "IC6") (pin "12") (pinfunction "DIFFIO_RX_L5P/DIFFOUT_L5P/ADC1IN6_12") (pintype "bidirectional"))
      (node (ref "R28") (pin "P$1") (pinfunction "1_P$1") (pintype "passive"))
    )
    (net (code "69") (name "Net-(D1-Pad2)") (class "Default")
      (node (ref "D1") (pin "2") (pinfunction "2_2") (pintype "passive"))
      (node (ref "J1") (pin "3") (pinfunction "3_3") (pintype "passive"))
    )
    (net (code "70") (name "Net-(F1-Pad1)") (class "Default")
      (node (ref "F1") (pin "1") (pinfunction "1_1") (pintype "passive"))
      (node (ref "J2") (pin "1") (pinfunction "1_1") (pintype "passive"))
    )
    (net (code "71") (name "Net-(IC2-EN)") (class "Default")
      (node (ref "IC2") (pin "1") (pinfunction "EN_1") (pintype "input"))
      (node (ref "R1") (pin "P$2") (pinfunction "2_P$2") (pintype "passive"))
    )
    (net (code "72") (name "Net-(IC2-FB)") (class "Default")
      (node (ref "C4") (pin "2") (pinfunction "2_2") (pintype "passive"))
      (node (ref "IC2") (pin "5") (pinfunction "FB_5") (pintype "passive"))
      (node (ref "R2") (pin "P$1") (pinfunction "1_P$1") (pintype "passive"))
      (node (ref "R3") (pin "P$2") (pinfunction "2_P$2") (pintype "passive"))
    )
    (net (code "73") (name "Net-(IC2-LX)") (class "Default")
      (node (ref "IC2") (pin "3") (pinfunction "LX_3") (pintype "input"))
      (node (ref "L1") (pin "1") (pinfunction "1_1") (pintype "passive"))
    )
    (net (code "74") (name "Net-(IC3-LINEI)") (class "Default")
      (node (ref "C8") (pin "1") (pinfunction "1_1") (pintype "passive"))
      (node (ref "IC3") (pin "11") (pinfunction "LINEI_11") (pintype "input"))
    )
    (net (code "75") (name "Net-(IC3-MBIAS)") (class "Default")
      (node (ref "IC3") (pin "2") (pinfunction "MBIAS_2") (pintype "output"))
      (node (ref "R5") (pin "P$1") (pinfunction "1_P$1") (pintype "passive"))
    )
    (net (code "76") (name "Net-(IC3-MIC)") (class "Default")
      (node (ref "C3") (pin "1") (pinfunction "1_1") (pintype "passive"))
      (node (ref "IC3") (pin "10") (pinfunction "MIC_10") (pintype "input"))
    )
    (net (code "77") (name "Net-(IC4-+IN)") (class "Default")
      (node (ref "IC4") (pin "1") (pinfunction "+IN_1") (pintype "input"))
      (node (ref "R7") (pin "P$1") (pinfunction "1_P$1") (pintype "passive"))
      (node (ref "R8") (pin "P$2") (pinfunction "2_P$2") (pintype "passive"))
    )
    (net (code "78") (name "Net-(IC4-OUT)") (class "Default")
      (node (ref "IC4") (pin "4") (pinfunction "OUT_4") (pintype "output"))
      (node (ref "PMOS1") (pin "3") (pinfunction "G_3") (pintype "passive"))
    )
    (net (code "79") (name "Net-(IC5-3V3OUT)") (class "Default")
      (node (ref "C11") (pin "1") (pinfunction "1_1") (pintype "passive"))
      (node (ref "IC5") (pin "17") (pinfunction "3V3OUT_17") (pintype "output"))
      (node (ref "IC5") (pin "4") (pinfunction "VCCIO_4") (pintype "power_in"))
      (node (ref "R10") (pin "P$2") (pinfunction "2_P$2") (pintype "passive"))
      (node (ref "R9") (pin "P$2") (pinfunction "2_P$2") (pintype "passive"))
    )
    (net (code "80") (name "Net-(IC5-USBDM)") (class "Default")
      (node (ref "IC5") (pin "16") (pinfunction "USBDM_16") (pintype "bidirectional"))
      (node (ref "J2") (pin "2") (pinfunction "2_2") (pintype "passive"))
    )
    (net (code "81") (name "Net-(IC5-USBDP)") (class "Default")
      (node (ref "IC5") (pin "15") (pinfunction "USBDP_15") (pintype "bidirectional"))
      (node (ref "J2") (pin "3") (pinfunction "3_3") (pintype "passive"))
    )
    (net (code "82") (name "Net-(IC6A-REFGND{slash}GND2)") (class "Default")
      (node (ref "F7") (pin "2") (pinfunction "2_2") (pintype "passive"))
      (node (ref "IC6") (pin "4") (pinfunction "REFGND/GND2_4") (pintype "input"))
    )
    (net (code "83") (name "Net-(IC6A-VCCA4)") (class "Default")
      (node (ref "F5") (pin "2") (pinfunction "2_2") (pintype "passive"))
      (node (ref "IC6") (pin "143") (pinfunction "VCCA4_143") (pintype "input"))
      (node (ref "IC6") (pin "2") (pinfunction "VCCA6_2") (pintype "input"))
    )
    (net (code "84") (name "Net-(IC6B-VCCIO1A)") (class "Default")
      (node (ref "F4") (pin "2") (pinfunction "2_2") (pintype "passive"))
      (node (ref "IC6") (pin "9") (pinfunction "VCCIO1A_9") (pintype "input"))
    )
    (net (code "85") (name "Net-(IC6J-CONFIG_SEL)") (class "Default")
      (node (ref "IC6") (pin "126") (pinfunction "CONFIG_SEL_126") (pintype "bidirectional"))
      (node (ref "JP6") (pin "1") (pinfunction "1_1") (pintype "passive"))
      (node (ref "R40") (pin "P$2") (pinfunction "2_P$2") (pintype "passive"))
    )
    (net (code "86") (name "Net-(IC6J-CONF_DONE{slash}DIFFIO_RX_T24N{slash}DIFFOUT_T24N)") (class "Default")
      (node (ref "IC6") (pin "138") (pinfunction "CONF_DONE/DIFFIO_RX_T24N/DIFFOUT_T24N_138") (pintype "bidirectional"))
      (node (ref "R38") (pin "P$1") (pinfunction "1_P$1") (pintype "passive"))
    )
    (net (code "87") (name "Net-(IC6J-DEV_CLRN{slash}DIFFIO_RX_T16N{slash}DIFFOUT_T16N)") (class "Default")
      (node (ref "IC6") (pin "121") (pinfunction "DEV_CLRN/DIFFIO_RX_T16N/DIFFOUT_T16N_121") (pintype "bidirectional"))
      (node (ref "R41") (pin "P$2") (pinfunction "2_P$2") (pintype "passive"))
    )
    (net (code "88") (name "Net-(IC6J-DIFFIO_RX_T20N{slash}DIFFOUT_T20N)") (class "Default")
      (node (ref "IC6") (pin "131") (pinfunction "DIFFIO_RX_T20N/DIFFOUT_T20N_131") (pintype "bidirectional"))
      (node (ref "LED2") (pin "C") (pinfunction "C_C") (pintype "passive"))
    )
    (net (code "89") (name "Net-(IC6J-DIFFIO_RX_T20P{slash}DIFFOUT_T20P)") (class "Default")
      (node (ref "IC6") (pin "130") (pinfunction "DIFFIO_RX_T20P/DIFFOUT_T20P_130") (pintype "bidirectional"))
      (node (ref "LED1") (pin "C") (pinfunction "C_C") (pintype "passive"))
    )
    (net (code "90") (name "Net-(IC6J-DIFFIO_RX_T22P{slash}DIFFOUT_T22P)") (class "Default")
      (node (ref "IC6") (pin "132") (pinfunction "DIFFIO_RX_T22P/DIFFOUT_T22P_132") (pintype "bidirectional"))
      (node (ref "LED3") (pin "C") (pinfunction "C_C") (pintype "passive"))
    )
    (net (code "91") (name "Net-(IC6J-NCONFIG)") (class "Default")
      (node (ref "IC6") (pin "129") (pinfunction "NCONFIG_129") (pintype "input"))
      (node (ref "R36") (pin "P$2") (pinfunction "2_P$2") (pintype "passive"))
    )
    (net (code "92") (name "Net-(IC6J-NSTATUS{slash}DIFFIO_RX_T24P{slash}DIFFOUT_T24P)") (class "Default")
      (node (ref "IC6") (pin "136") (pinfunction "NSTATUS/DIFFIO_RX_T24P/DIFFOUT_T24P_136") (pintype "bidirectional"))
      (node (ref "R37") (pin "P$1") (pinfunction "1_P$1") (pintype "passive"))
    )
    (net (code "93") (name "Net-(IC14-OUT)") (class "Default")
      (node (ref "IC14") (pin "3") (pinfunction "OUT_3") (pintype "output"))
      (node (ref "IC6") (pin "88") (pinfunction "CLK2P/DIFFIO_RX_R14P/DIFFOUT_R14P_88") (pintype "bidirectional"))
    )
    (net (code "94") (name "Net-(R5-2)") (class "Default")
      (node (ref "J3") (pin "4") (pinfunction "4_4") (pintype "passive"))
      (node (ref "R5") (pin "P$2") (pinfunction "2_P$2") (pintype "passive"))
    )
    (net (code "95") (name "Net-(R6-1)") (class "Default")
      (node (ref "J4") (pin "1") (pinfunction "1_1") (pintype "passive"))
      (node (ref "R6") (pin "P$1") (pinfunction "1_P$1") (pintype "passive"))
    )
    (net (code "96") (name "Net-(R9-1)") (class "Default")
      (node (ref "LED_TX") (pin "A") (pinfunction "A_A") (pintype "passive"))
      (node (ref "R9") (pin "P$1") (pinfunction "1_P$1") (pintype "passive"))
    )
    (net (code "97") (name "Net-(R10-1)") (class "Default")
      (node (ref "LED_RX") (pin "A") (pinfunction "A_A") (pintype "passive"))
      (node (ref "R10") (pin "P$1") (pinfunction "1_P$1") (pintype "passive"))
    )
    (net (code "98") (name "Net-(R11-2)") (class "Default")
      (node (ref "C12") (pin "1") (pinfunction "1_1") (pintype "passive"))
      (node (ref "IC7") (pin "3") (pinfunction "3_3") (pintype "input"))
      (node (ref "PT1") (pin "1A") (pinfunction "1A_1A") (pintype "passive"))
      (node (ref "R11") (pin "P$2") (pinfunction "2_P$2") (pintype "passive"))
    )
    (net (code "99") (name "Net-(R12-2)") (class "Default")
      (node (ref "C13") (pin "1") (pinfunction "1_1") (pintype "passive"))
      (node (ref "IC7") (pin "5") (pinfunction "5_5") (pintype "input"))
      (node (ref "R12") (pin "P$2") (pinfunction "2_P$2") (pintype "passive"))
      (node (ref "R13") (pin "P$1") (pinfunction "1_P$1") (pintype "passive"))
    )
    (net (code "100") (name "Net-(R14-2)") (class "Default")
      (node (ref "C14") (pin "1") (pinfunction "1_1") (pintype "passive"))
      (node (ref "IC8") (pin "3") (pinfunction "3_3") (pintype "input"))
      (node (ref "R14") (pin "P$2") (pinfunction "2_P$2") (pintype "passive"))
      (node (ref "R15") (pin "P$2") (pinfunction "2_P$2") (pintype "passive"))
    )
    (net (code "101") (name "Net-(R16-2)") (class "Default")
      (node (ref "C15") (pin "1") (pinfunction "1_1") (pintype "passive"))
      (node (ref "IC8") (pin "5") (pinfunction "5_5") (pintype "input"))
      (node (ref "R16") (pin "P$2") (pinfunction "2_P$2") (pintype "passive"))
      (node (ref "R17") (pin "P$2") (pinfunction "2_P$2") (pintype "passive"))
    )
    (net (code "102") (name "Net-(R18-2)") (class "Default")
      (node (ref "C16") (pin "1") (pinfunction "1_1") (pintype "passive"))
      (node (ref "IC8") (pin "10") (pinfunction "10_10") (pintype "input"))
      (node (ref "R18") (pin "P$2") (pinfunction "2_P$2") (pintype "passive"))
      (node (ref "R19") (pin "P$1") (pinfunction "1_P$1") (pintype "passive"))
    )
    (net (code "103") (name "Net-(R20-2)") (class "Default")
      (node (ref "C17") (pin "1") (pinfunction "1_1") (pintype "passive"))
      (node (ref "IC8") (pin "12") (pinfunction "12_12") (pintype "input"))
      (node (ref "R20") (pin "P$2") (pinfunction "2_P$2") (pintype "passive"))
      (node (ref "R21") (pin "P$2") (pinfunction "2_P$2") (pintype "passive"))
    )
    (net (code "104") (name "Net-(R22-1)") (class "Default")
      (node (ref "LED_IOREF") (pin "A") (pinfunction "A_A") (pintype "passive"))
      (node (ref "R22") (pin "P$1") (pinfunction "1_P$1") (pintype "passive"))
    )
    (net (code "105") (name "Net-(R29-1)") (class "Default")
      (node (ref "J4") (pin "4") (pinfunction "4_4") (pintype "passive"))
      (node (ref "R29") (pin "P$1") (pinfunction "1_P$1") (pintype "passive"))
    )
    (net (code "106") (name "Net-(R42-1)") (class "Default")
      (node (ref "LED1") (pin "A") (pinfunction "A_A") (pintype "passive"))
      (node (ref "R42") (pin "P$1") (pinfunction "1_P$1") (pintype "passive"))
    )
    (net (code "107") (name "Net-(R43-1)") (class "Default")
      (node (ref "LED2") (pin "A") (pinfunction "A_A") (pintype "passive"))
      (node (ref "R43") (pin "P$1") (pinfunction "1_P$1") (pintype "passive"))
    )
    (net (code "108") (name "Net-(R47-1)") (class "Default")
      (node (ref "LED3") (pin "A") (pinfunction "A_A") (pintype "passive"))
      (node (ref "R47") (pin "P$1") (pinfunction "1_P$1") (pintype "passive"))
    )
    (net (code "109") (name "PIN0_RX") (class "Default")
      (node (ref "IC12") (pin "20") (pinfunction "20_20") (pintype "bidirectional"))
      (node (ref "J9") (pin "0") (pinfunction "0(RX)_0") (pintype "bidirectional"))
    )
    (net (code "110") (name "PIN1_TX") (class "Default")
      (node (ref "IC12") (pin "18") (pinfunction "18_18") (pintype "bidirectional"))
      (node (ref "J9") (pin "1") (pinfunction "1(TX)_1") (pintype "bidirectional"))
    )
    (net (code "111") (name "PIN2") (class "Default")
      (node (ref "IC12") (pin "17") (pinfunction "17_17") (pintype "bidirectional"))
      (node (ref "J9") (pin "2") (pinfunction "2_2") (pintype "bidirectional"))
    )
    (net (code "112") (name "PIN3~{}") (class "Default")
      (node (ref "IC12") (pin "16") (pinfunction "16_16") (pintype "bidirectional"))
      (node (ref "J9") (pin "3") (pinfunction "3~{}_3") (pintype "bidirectional"))
    )
    (net (code "113") (name "PIN4") (class "Default")
      (node (ref "IC12") (pin "15") (pinfunction "15_15") (pintype "bidirectional"))
      (node (ref "J9") (pin "4") (pinfunction "4_4") (pintype "bidirectional"))
    )
    (net (code "114") (name "PIN5~{}") (class "Default")
      (node (ref "IC12") (pin "14") (pinfunction "14_14") (pintype "bidirectional"))
      (node (ref "J9") (pin "5") (pinfunction "5~{}_5") (pintype "bidirectional"))
    )
    (net (code "115") (name "PIN6~{}") (class "Default")
      (node (ref "IC12") (pin "13") (pinfunction "13_13") (pintype "bidirectional"))
      (node (ref "J9") (pin "6") (pinfunction "6~{}_6") (pintype "bidirectional"))
    )
    (net (code "116") (name "PIN7") (class "Default")
      (node (ref "IC12") (pin "12") (pinfunction "12_12") (pintype "bidirectional"))
      (node (ref "J9") (pin "7") (pinfunction "7_7") (pintype "bidirectional"))
    )
    (net (code "117") (name "PIN8") (class "Default")
      (node (ref "IC13") (pin "20") (pinfunction "20_20") (pintype "bidirectional"))
      (node (ref "J8") (pin "8") (pinfunction "8_8") (pintype "bidirectional"))
    )
    (net (code "118") (name "PIN9~{}") (class "Default")
      (node (ref "IC13") (pin "18") (pinfunction "18_18") (pintype "bidirectional"))
      (node (ref "J8") (pin "9") (pinfunction "9~{}_9") (pintype "bidirectional"))
    )
    (net (code "119") (name "PIN10~{}") (class "Default")
      (node (ref "IC13") (pin "17") (pinfunction "17_17") (pintype "bidirectional"))
      (node (ref "J8") (pin "10") (pinfunction "10~{}_10") (pintype "bidirectional"))
    )
    (net (code "120") (name "PIN11~{}") (class "Default")
      (node (ref "IC13") (pin "16") (pinfunction "16_16") (pintype "bidirectional"))
      (node (ref "J8") (pin "11") (pinfunction "11~{}_11") (pintype "bidirectional"))
    )
    (net (code "121") (name "PIN12") (class "Default")
      (node (ref "IC13") (pin "15") (pinfunction "15_15") (pintype "bidirectional"))
      (node (ref "J8") (pin "12") (pinfunction "12_12") (pintype "bidirectional"))
    )
    (net (code "122") (name "PIN13") (class "Default")
      (node (ref "IC13") (pin "14") (pinfunction "14_14") (pintype "bidirectional"))
      (node (ref "J8") (pin "13") (pinfunction "13_13") (pintype "bidirectional"))
    )
    (net (code "123") (name "RESET_N") (class "Default")
      (node (ref "IC6") (pin "60") (pinfunction "DIFFIO_TX_RX_B16P/DIFFOUT_B16P_60") (pintype "bidirectional"))
      (node (ref "J10") (pin "RESET") (pinfunction "RESET_RESET") (pintype "bidirectional"))
      (node (ref "R32") (pin "P$2") (pinfunction "2_P$2") (pintype "passive"))
      (node (ref "SW1") (pin "1") (pinfunction "1_1") (pintype "bidirectional"))
      (node (ref "SW1") (pin "2") (pinfunction "2_2") (pintype "bidirectional"))
    )
    (net (code "124") (name "SCL") (class "Default")
      (node (ref "IC13") (pin "12") (pinfunction "12_12") (pintype "bidirectional"))
      (node (ref "J8") (pin "SCL") (pinfunction "SCL_SCL") (pintype "bidirectional"))
    )
    (net (code "125") (name "SDA") (class "Default")
      (node (ref "IC13") (pin "13") (pinfunction "13_13") (pintype "bidirectional"))
      (node (ref "J8") (pin "SDA") (pinfunction "SDA_SDA") (pintype "bidirectional"))
    )
    (net (code "126") (name "SRAM_CS_N") (class "Default")
      (node (ref "IC10") (pin "1") (pinfunction "CS_N_1") (pintype "input"))
      (node (ref "IC6") (pin "29") (pinfunction "CLK1P/DIFFIO_RX_L20P/DIFFOUT_L20P_29") (pintype "bidirectional"))
    )
    (net (code "127") (name "SRAM_SCK") (class "Default")
      (node (ref "IC10") (pin "6") (pinfunction "SCK_6") (pintype "input"))
      (node (ref "IC6") (pin "27") (pinfunction "CLK0P/DIFFIO_RX_L18P/DIFFOUT_L18P_27") (pintype "bidirectional"))
    )
    (net (code "128") (name "SRAM_SIO0") (class "Default")
      (node (ref "IC10") (pin "5") (pinfunction "SI/SIO0_5") (pintype "bidirectional"))
      (node (ref "IC6") (pin "28") (pinfunction "CLK1N/DIFFIO_RX_L20N/DIFFOUT_L20N_28") (pintype "bidirectional"))
    )
    (net (code "129") (name "SRAM_SIO1") (class "Default")
      (node (ref "IC10") (pin "2") (pinfunction "SO/SIO1_2") (pintype "bidirectional"))
      (node (ref "IC6") (pin "32") (pinfunction "PLL_L_CLKOUTN/DIFFIO_RX_L27N/DIFFOUT_L27N_32") (pintype "bidirectional"))
    )
    (net (code "130") (name "SRAM_SIO2") (class "Default")
      (node (ref "IC10") (pin "3") (pinfunction "NC/SIO2_3") (pintype "bidirectional"))
      (node (ref "IC6") (pin "33") (pinfunction "PLL_L_CLKOUTP/DIFFIO_RX_L27P/DIFFOUT_L27P_33") (pintype "bidirectional"))
    )
    (net (code "131") (name "SRAM_SIO3") (class "Default")
      (node (ref "IC10") (pin "7") (pinfunction "HOLD_N/SIO3_7") (pintype "bidirectional"))
      (node (ref "IC6") (pin "26") (pinfunction "CLK0N/DIFFIO_RX_L18N/DIFFOUT_L18N_26") (pintype "bidirectional"))
    )
    (net (code "132") (name "TCK") (class "Default")
      (node (ref "IC6") (pin "18") (pinfunction "TCK/DIFFIO_RX_L11P/DIFFOUT_L11P_18") (pintype "bidirectional"))
      (node (ref "J7") (pin "1") (pinfunction "1_1") (pintype "passive"))
      (node (ref "R39") (pin "P$2") (pinfunction "2_P$2") (pintype "passive"))
    )
    (net (code "133") (name "TDI") (class "Default")
      (node (ref "IC6") (pin "19") (pinfunction "TDI/DIFFIO_RX_L12N/DIFFOUT_L12N_19") (pintype "bidirectional"))
      (node (ref "J7") (pin "9") (pinfunction "9_9") (pintype "passive"))
      (node (ref "R34") (pin "P$1") (pinfunction "1_P$1") (pintype "passive"))
    )
    (net (code "134") (name "TDO") (class "Default")
      (node (ref "IC6") (pin "20") (pinfunction "TDO/DIFFIO_RX_L12P/DIFFOUT_L12P_20") (pintype "bidirectional"))
      (node (ref "J7") (pin "3") (pinfunction "3_3") (pintype "passive"))
    )
    (net (code "135") (name "TMS") (class "Default")
      (node (ref "IC6") (pin "16") (pinfunction "TMS/DIFFIO_RX_L11N/DIFFOUT_L11N_16") (pintype "bidirectional"))
      (node (ref "J7") (pin "5") (pinfunction "5_5") (pintype "passive"))
      (node (ref "R35") (pin "P$1") (pinfunction "1_P$1") (pintype "passive"))
    )
    (net (code "136") (name "USBVCC") (class "Default")
      (node (ref "C10") (pin "1") (pinfunction "1_1") (pintype "passive"))
      (node (ref "C9") (pin "+") (pinfunction "+_+") (pintype "passive"))
      (node (ref "F1") (pin "2") (pinfunction "2_2") (pintype "passive"))
      (node (ref "IC5") (pin "20") (pinfunction "VCC_20") (pintype "power_in"))
      (node (ref "PMOS1") (pin "1") (pinfunction "D1_1") (pintype "passive"))
      (node (ref "PMOS1") (pin "2") (pinfunction "D2_2") (pintype "passive"))
      (node (ref "PMOS1") (pin "5") (pinfunction "D3_5") (pintype "passive"))
      (node (ref "PMOS1") (pin "6") (pinfunction "D4_6") (pintype "passive"))
    )
    (net (code "137") (name "VIN") (class "Default")
      (node (ref "C1") (pin "+") (pinfunction "+_+") (pintype "passive"))
      (node (ref "D1") (pin "1") (pinfunction "1_1") (pintype "passive"))
      (node (ref "IC1") (pin "3") (pinfunction "3_3") (pintype "input"))
      (node (ref "J10") (pin "VIN") (pinfunction "VIN_VIN") (pintype "bidirectional"))
      (node (ref "R7") (pin "P$2") (pinfunction "2_P$2") (pintype "passive"))
    )
    (net (code "138") (name "unconnected-(IC3-HDST-Pad3)") (class "Default")
      (node (ref "IC3") (pin "3") (pinfunction "HDST_3") (pintype "output"))
    )
    (net (code "139") (name "unconnected-(IC3-LINEO-Pad15)") (class "Default")
      (node (ref "IC3") (pin "15") (pinfunction "LINEO_15") (pintype "output"))
    )
    (net (code "140") (name "unconnected-(IC5-CBUS2-Pad13)") (class "Default")
      (node (ref "IC5") (pin "13") (pinfunction "CBUS2_13") (pintype "bidirectional"))
    )
    (net (code "141") (name "unconnected-(IC5-CBUS3-Pad14)") (class "Default")
      (node (ref "IC5") (pin "14") (pinfunction "CBUS3_14") (pintype "bidirectional"))
    )
    (net (code "142") (name "unconnected-(IC5-CBUS4-Pad12)") (class "Default")
      (node (ref "IC5") (pin "12") (pinfunction "CBUS4_12") (pintype "bidirectional"))
    )
    (net (code "143") (name "unconnected-(IC5-OSCI-Pad27)") (class "Default")
      (node (ref "IC5") (pin "27") (pinfunction "OSCI_27") (pintype "input"))
    )
    (net (code "144") (name "unconnected-(IC5-OSCO-Pad28)") (class "Default")
      (node (ref "IC5") (pin "28") (pinfunction "OSCO_28") (pintype "output"))
    )
    (net (code "145") (name "unconnected-(IC5-~{DCD}-Pad10)") (class "Default")
      (node (ref "IC5") (pin "10") (pinfunction "~{DCD}_10") (pintype "input"))
    )
    (net (code "146") (name "unconnected-(IC5-~{DSR}-Pad9)") (class "Default")
      (node (ref "IC5") (pin "9") (pinfunction "~{DSR}_9") (pintype "input"))
    )
    (net (code "147") (name "unconnected-(IC5-~{DTR}-Pad2)") (class "Default")
      (node (ref "IC5") (pin "2") (pinfunction "~{DTR}_2") (pintype "output"))
    )
    (net (code "148") (name "unconnected-(IC5-~{RI}-Pad6)") (class "Default")
      (node (ref "IC5") (pin "6") (pinfunction "~{RI}_6") (pintype "input"))
    )
    (net (code "149") (name "unconnected-(IC6C-DIFFIO_RX_L14N{slash}DIFFOUT_L14N-Pad21)") (class "Default")
      (node (ref "IC6") (pin "21") (pinfunction "DIFFIO_RX_L14N/DIFFOUT_L14N_21") (pintype "bidirectional"))
    )
    (net (code "150") (name "unconnected-(IC6C-DIFFIO_RX_L14P{slash}DIFFOUT_L14P-Pad22)") (class "Default")
      (node (ref "IC6") (pin "22") (pinfunction "DIFFIO_RX_L14P/DIFFOUT_L14P_22") (pintype "bidirectional"))
    )
    (net (code "151") (name "unconnected-(IC6C-DIFFIO_RX_L16N{slash}DIFFOUT_L16N-Pad24)") (class "Default")
      (node (ref "IC6") (pin "24") (pinfunction "DIFFIO_RX_L16N/DIFFOUT_L16N_24") (pintype "bidirectional"))
    )
    (net (code "152") (name "unconnected-(IC6C-DIFFIO_RX_L16P{slash}DIFFOUT_L16P-Pad25)") (class "Default")
      (node (ref "IC6") (pin "25") (pinfunction "DIFFIO_RX_L16P/DIFFOUT_L16P_25") (pintype "bidirectional"))
    )
    (net (code "153") (name "unconnected-(IC6C-VREFB1N0-Pad17)") (class "Default")
      (node (ref "IC6") (pin "17") (pinfunction "VREFB1N0_17") (pintype "input"))
    )
    (net (code "154") (name "unconnected-(IC6D-VREFB2N0-Pad30)") (class "Default")
      (node (ref "IC6") (pin "30") (pinfunction "VREFB2N0_30") (pintype "input"))
    )
    (net (code "155") (name "unconnected-(IC6E-DIFFIO_TX_RX_B1P{slash}DIFFOUT_B1P-Pad39)") (class "Default")
      (node (ref "IC6") (pin "39") (pinfunction "DIFFIO_TX_RX_B1P/DIFFOUT_B1P_39") (pintype "bidirectional"))
    )
    (net (code "156") (name "unconnected-(IC6E-DIFFIO_TX_RX_B3N{slash}DIFFOUT_B3N-Pad41)") (class "Default")
      (node (ref "IC6") (pin "41") (pinfunction "DIFFIO_TX_RX_B3N/DIFFOUT_B3N_41") (pintype "bidirectional"))
    )
    (net (code "157") (name "unconnected-(IC6E-VREFB3N0-Pad48)") (class "Default")
      (node (ref "IC6") (pin "48") (pinfunction "VREFB3N0_48") (pintype "input"))
    )
    (net (code "158") (name "unconnected-(IC6F-VREFB4N0-Pad61)") (class "Default")
      (node (ref "IC6") (pin "61") (pinfunction "VREFB4N0_61") (pintype "input"))
    )
    (net (code "159") (name "unconnected-(IC6G-DIFFIO_RX_R1N{slash}DIFFOUT_R1N-Pad77)") (class "Default")
      (node (ref "IC6") (pin "77") (pinfunction "DIFFIO_RX_R1N/DIFFOUT_R1N_77") (pintype "bidirectional"))
    )
    (net (code "160") (name "unconnected-(IC6G-DIFFIO_RX_R2P{slash}DIFFOUT_R2P-Pad74)") (class "Default")
      (node (ref "IC6") (pin "74") (pinfunction "DIFFIO_RX_R2P/DIFFOUT_R2P_74") (pintype "bidirectional"))
    )
    (net (code "161") (name "unconnected-(IC6G-DIFFIO_RX_R10N{slash}DIFFOUT_R10N-Pad87)") (class "Default")
      (node (ref "IC6") (pin "87") (pinfunction "DIFFIO_RX_R10N/DIFFOUT_R10N_87") (pintype "bidirectional"))
    )
    (net (code "162") (name "unconnected-(IC6G-DIFFIO_RX_R10P{slash}DIFFOUT_R10P-Pad85)") (class "Default")
      (node (ref "IC6") (pin "85") (pinfunction "DIFFIO_RX_R10P/DIFFOUT_R10P_85") (pintype "bidirectional"))
    )
    (net (code "163") (name "unconnected-(IC6G-DIFFIO_RX_R11N{slash}DIFFOUT_R11N-Pad86)") (class "Default")
      (node (ref "IC6") (pin "86") (pinfunction "DIFFIO_RX_R11N/DIFFOUT_R11N_86") (pintype "bidirectional"))
    )
    (net (code "164") (name "unconnected-(IC6G-IO78-Pad78)") (class "Default")
      (node (ref "IC6") (pin "78") (pinfunction "IO78_78") (pintype "bidirectional"))
    )
    (net (code "165") (name "unconnected-(IC6G-VREFB5N0-Pad80)") (class "Default")
      (node (ref "IC6") (pin "80") (pinfunction "VREFB5N0_80") (pintype "input"))
    )
    (net (code "166") (name "unconnected-(IC6H-CLK2N{slash}DIFFIO_RX_R14N{slash}DIFFOUT_R14N-Pad89)") (class "Default")
      (node (ref "IC6") (pin "89") (pinfunction "CLK2N/DIFFIO_RX_R14N/DIFFOUT_R14N_89") (pintype "bidirectional"))
    )
    (net (code "167") (name "unconnected-(IC6H-CLK3N{slash}DIFFIO_RX_R16N{slash}DIFFOUT_R16N-Pad91)") (class "Default")
      (node (ref "IC6") (pin "91") (pinfunction "CLK3N/DIFFIO_RX_R16N/DIFFOUT_R16N_91") (pintype "bidirectional"))
    )
    (net (code "168") (name "unconnected-(IC6H-CLK3P{slash}DIFFIO_RX_R16P{slash}DIFFOUT_R16P-Pad90)") (class "Default")
      (node (ref "IC6") (pin "90") (pinfunction "CLK3P/DIFFIO_RX_R16P/DIFFOUT_R16P_90") (pintype "bidirectional"))
    )
    (net (code "169") (name "unconnected-(IC6H-DIFFIO_RX_R33N{slash}DIFFOUT_R33N-Pad106)") (class "Default")
      (node (ref "IC6") (pin "106") (pinfunction "DIFFIO_RX_R33N/DIFFOUT_R33N_106") (pintype "bidirectional"))
    )
    (net (code "170") (name "unconnected-(IC6H-DIFFIO_RX_R33P{slash}DIFFOUT_R33P-Pad105)") (class "Default")
      (node (ref "IC6") (pin "105") (pinfunction "DIFFIO_RX_R33P/DIFFOUT_R33P_105") (pintype "bidirectional"))
    )
    (net (code "171") (name "unconnected-(IC6H-VREFB6N0-Pad97)") (class "Default")
      (node (ref "IC6") (pin "97") (pinfunction "VREFB6N0_97") (pintype "input"))
    )
    (net (code "172") (name "unconnected-(IC6I-DIFFIO_RX_T1N{slash}DIFFOUT_T1N-Pad111)") (class "Default")
      (node (ref "IC6") (pin "111") (pinfunction "DIFFIO_RX_T1N/DIFFOUT_T1N_111") (pintype "bidirectional"))
    )
    (net (code "173") (name "unconnected-(IC6I-DIFFIO_RX_T1P{slash}DIFFOUT_T1P-Pad110)") (class "Default")
      (node (ref "IC6") (pin "110") (pinfunction "DIFFIO_RX_T1P/DIFFOUT_T1P_110") (pintype "bidirectional"))
    )
    (net (code "174") (name "unconnected-(IC6I-DIFFIO_RX_T10N{slash}DIFFOUT_T10N-Pad119)") (class "Default")
      (node (ref "IC6") (pin "119") (pinfunction "DIFFIO_RX_T10N/DIFFOUT_T10N_119") (pintype "bidirectional"))
    )
    (net (code "175") (name "unconnected-(IC6I-DIFFIO_RX_T10P{slash}DIFFOUT_T10P-Pad118)") (class "Default")
      (node (ref "IC6") (pin "118") (pinfunction "DIFFIO_RX_T10P/DIFFOUT_T10P_118") (pintype "bidirectional"))
    )
    (net (code "176") (name "unconnected-(IC6I-IO113-Pad113)") (class "Default")
      (node (ref "IC6") (pin "113") (pinfunction "IO113_113") (pintype "bidirectional"))
    )
    (net (code "177") (name "unconnected-(IC6I-IO114-Pad114)") (class "Default")
      (node (ref "IC6") (pin "114") (pinfunction "IO114_114") (pintype "bidirectional"))
    )
    (net (code "178") (name "unconnected-(IC6I-VREFB7N0-Pad112)") (class "Default")
      (node (ref "IC6") (pin "112") (pinfunction "VREFB7N0_112") (pintype "input"))
    )
    (net (code "179") (name "unconnected-(IC6J-CRC_ERROR{slash}DIFFIO_RX_T22N{slash}DIFFOUT_T22N-Pad134)") (class "Default")
      (node (ref "IC6") (pin "134") (pinfunction "CRC_ERROR/DIFFIO_RX_T22N/DIFFOUT_T22N_134") (pintype "bidirectional"))
    )
    (net (code "180") (name "unconnected-(IC6J-DEV_OE-Pad122)") (class "Default")
      (node (ref "IC6") (pin "122") (pinfunction "DEV_OE_122") (pintype "bidirectional"))
    )
    (net (code "181") (name "unconnected-(IC6J-DIFFIO_RX_T16P{slash}DIFFOUT_T16P-Pad120)") (class "Default")
      (node (ref "IC6") (pin "120") (pinfunction "DIFFIO_RX_T16P/DIFFOUT_T16P_120") (pintype "bidirectional"))
    )
    (net (code "182") (name "unconnected-(IC6J-DIFFIO_RX_T19N{slash}DIFFOUT_T19N-Pad127)") (class "Default")
      (node (ref "IC6") (pin "127") (pinfunction "DIFFIO_RX_T19N/DIFFOUT_T19N_127") (pintype "bidirectional"))
    )
    (net (code "183") (name "unconnected-(IC6J-DIFFIO_RX_T19P{slash}DIFFOUT_T19P-Pad124)") (class "Default")
      (node (ref "IC6") (pin "124") (pinfunction "DIFFIO_RX_T19P/DIFFOUT_T19P_124") (pintype "bidirectional"))
    )
    (net (code "184") (name "unconnected-(IC6J-DIFFIO_RX_T26N{slash}DIFFOUT_T26N-Pad141)") (class "Default")
      (node (ref "IC6") (pin "141") (pinfunction "DIFFIO_RX_T26N/DIFFOUT_T26N_141") (pintype "bidirectional"))
    )
    (net (code "185") (name "unconnected-(IC6J-DIFFIO_RX_T26P{slash}DIFFOUT_T26P-Pad140)") (class "Default")
      (node (ref "IC6") (pin "140") (pinfunction "DIFFIO_RX_T26P/DIFFOUT_T26P_140") (pintype "bidirectional"))
    )
    (net (code "186") (name "unconnected-(IC6J-IO135-Pad135)") (class "Default")
      (node (ref "IC6") (pin "135") (pinfunction "IO135_135") (pintype "bidirectional"))
    )
    (net (code "187") (name "unconnected-(IC6J-VREFB8N0-Pad123)") (class "Default")
      (node (ref "IC6") (pin "123") (pinfunction "VREFB8N0_123") (pintype "input"))
    )
    (net (code "188") (name "unconnected-(J7-Pad6)") (class "Default")
      (node (ref "J7") (pin "6") (pinfunction "6_6") (pintype "passive"))
    )
    (net (code "189") (name "unconnected-(J7-Pad7)") (class "Default")
      (node (ref "J7") (pin "7") (pinfunction "7_7") (pintype "passive"))
    )
    (net (code "190") (name "unconnected-(J7-Pad8)") (class "Default")
      (node (ref "J7") (pin "8") (pinfunction "8_8") (pintype "passive"))
    )
    (net (code "191") (name "unconnected-(J10-NC-PadN{slash}C)") (class "Default")
      (node (ref "J10") (pin "N/C") (pinfunction "NC_N/C") (pintype "bidirectional"))
    )
  )
)
